# PX4FMUv2_4.net
KiCad netlist of a schematic drawn in EAGLE
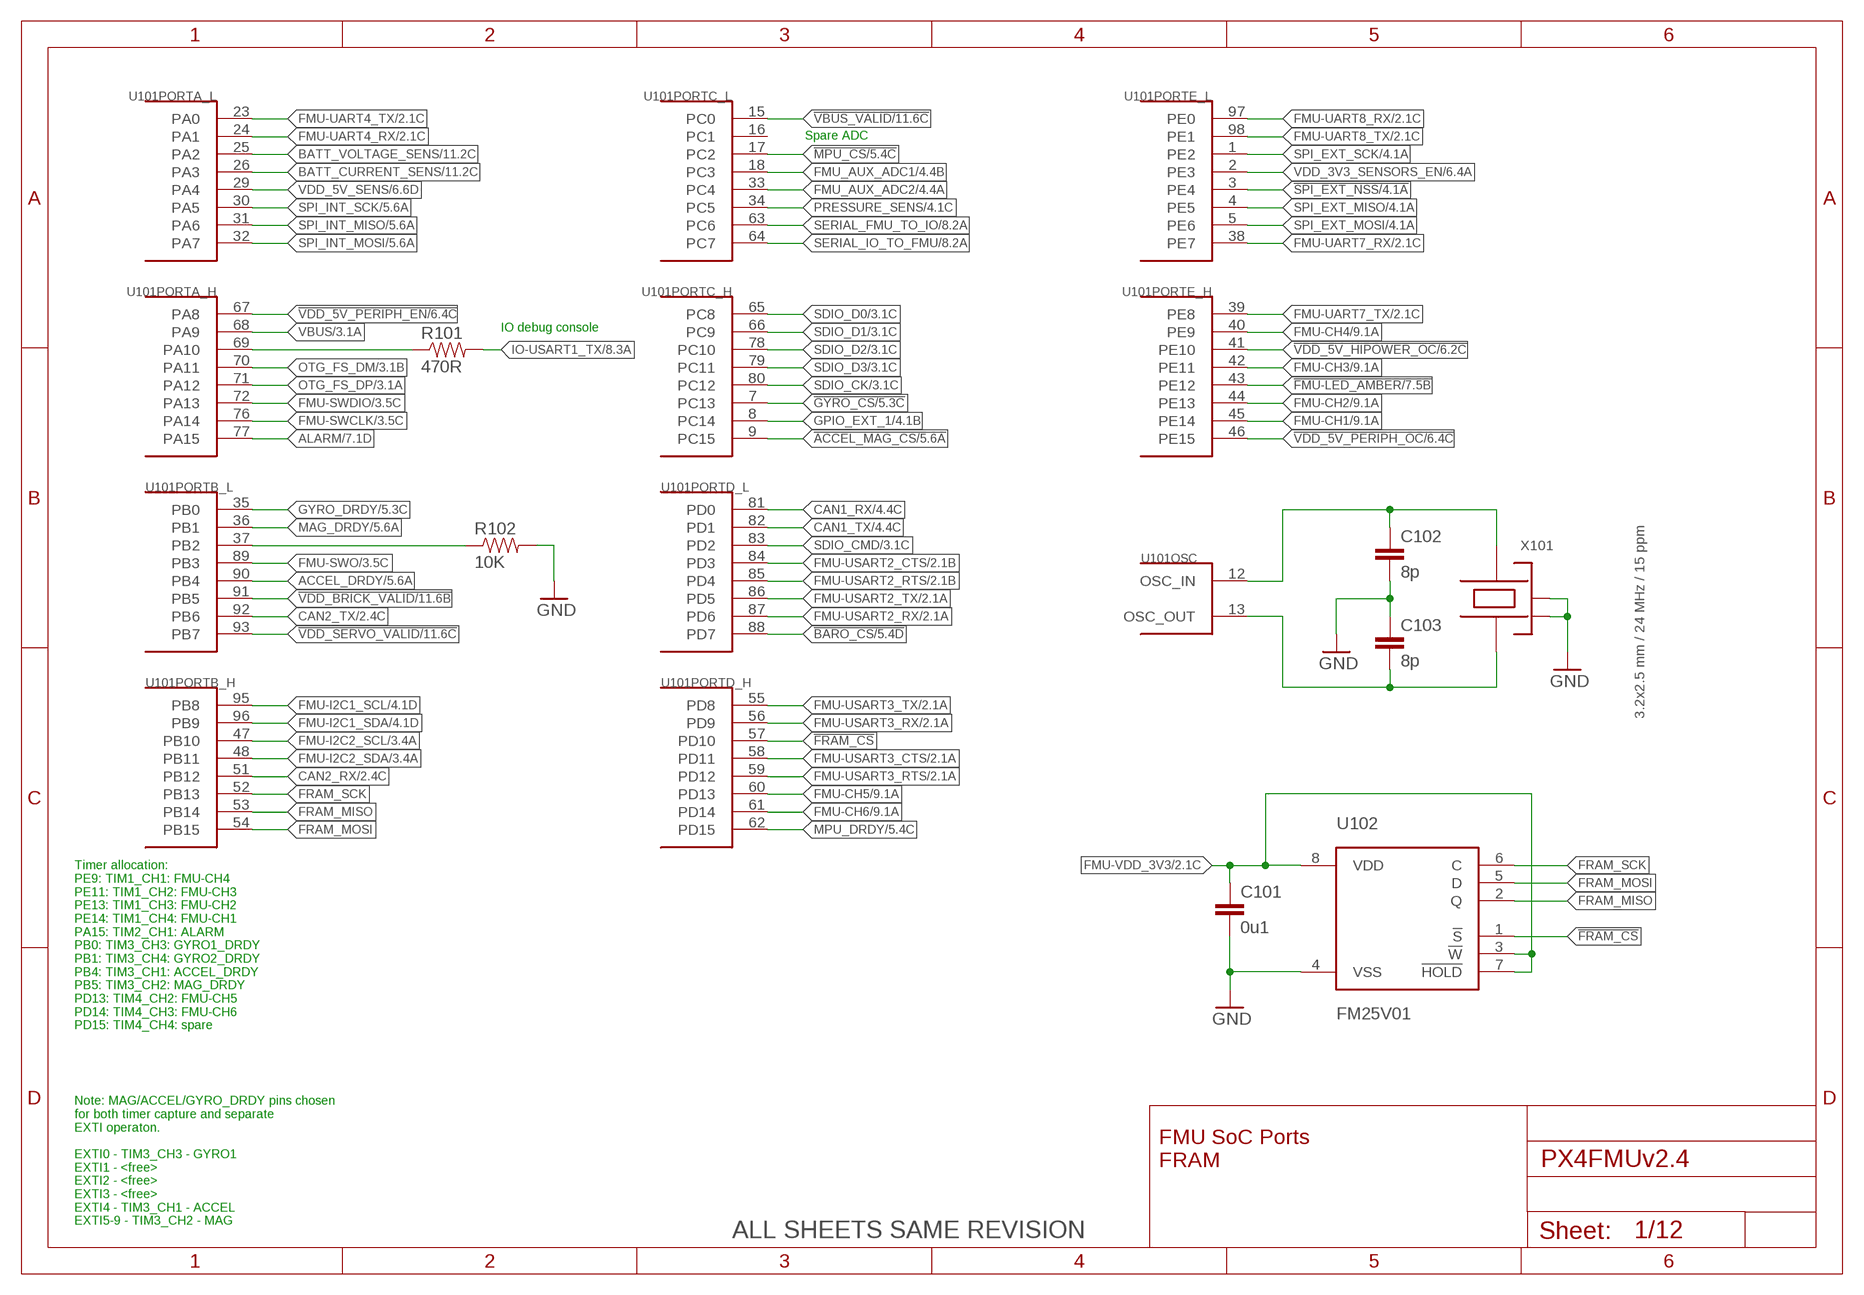
[diagram p0: schematic, sheet 1]
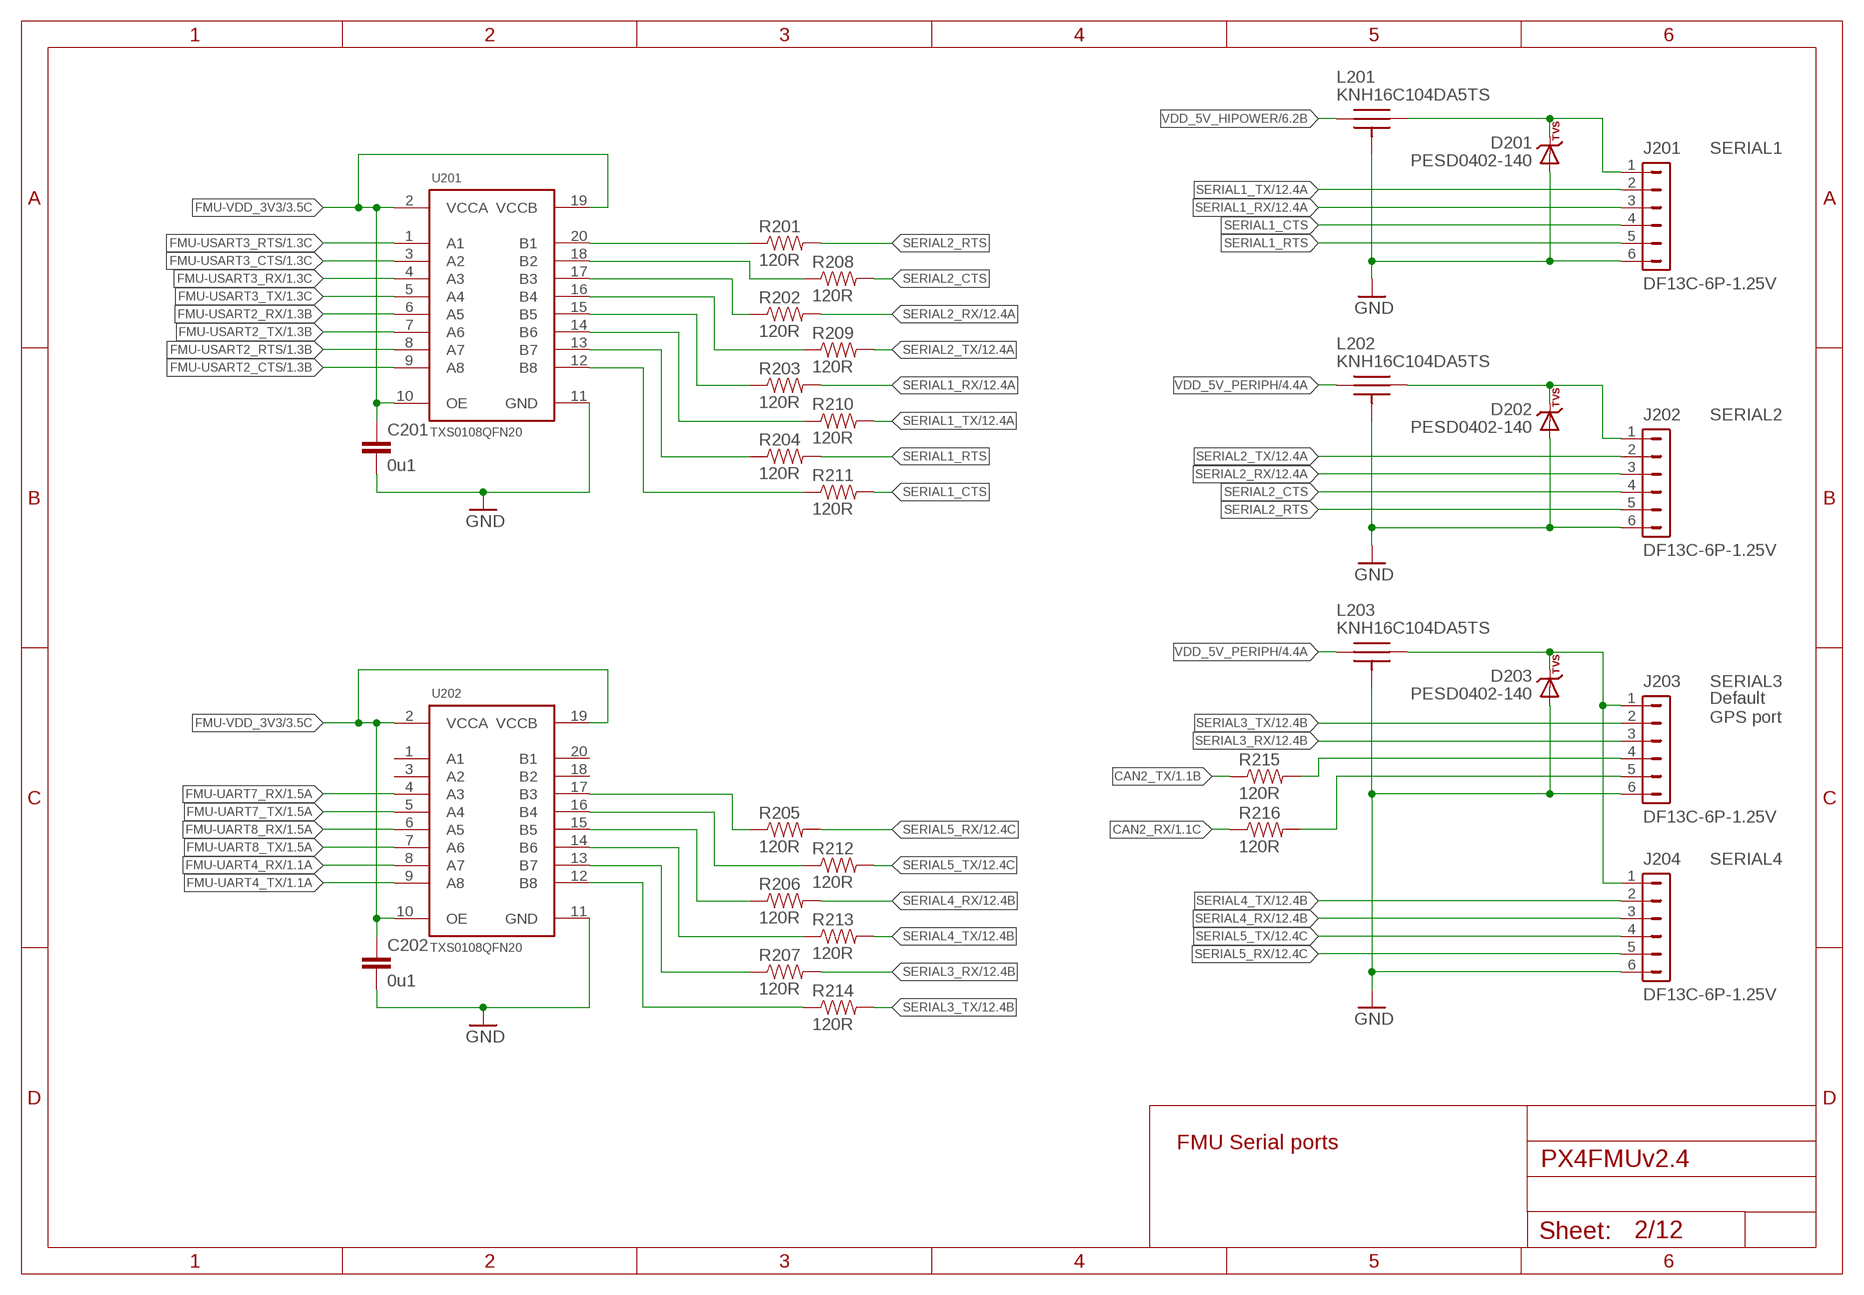
[diagram p1: schematic, sheet 2]
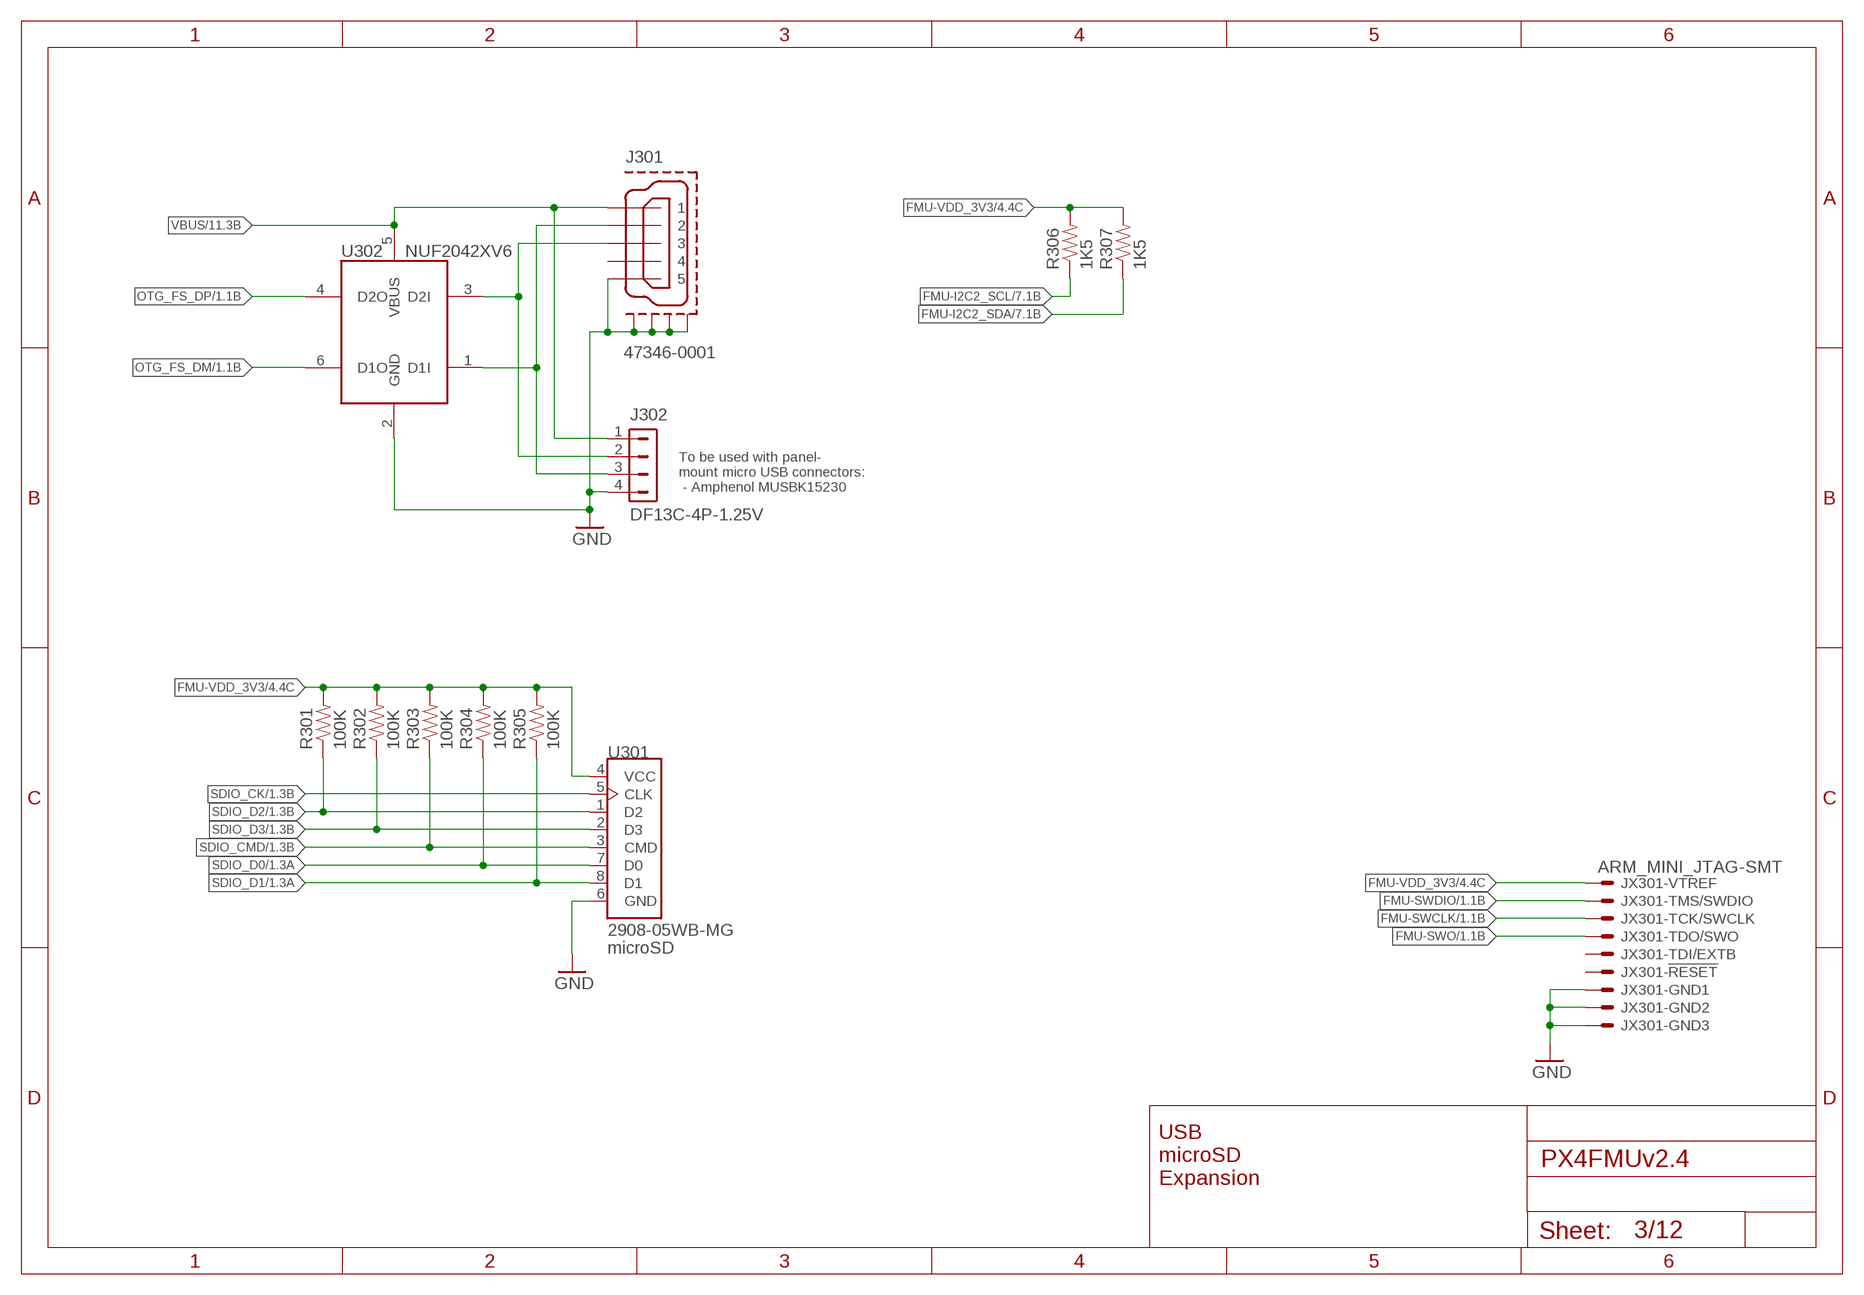
[diagram p2: schematic, sheet 3]
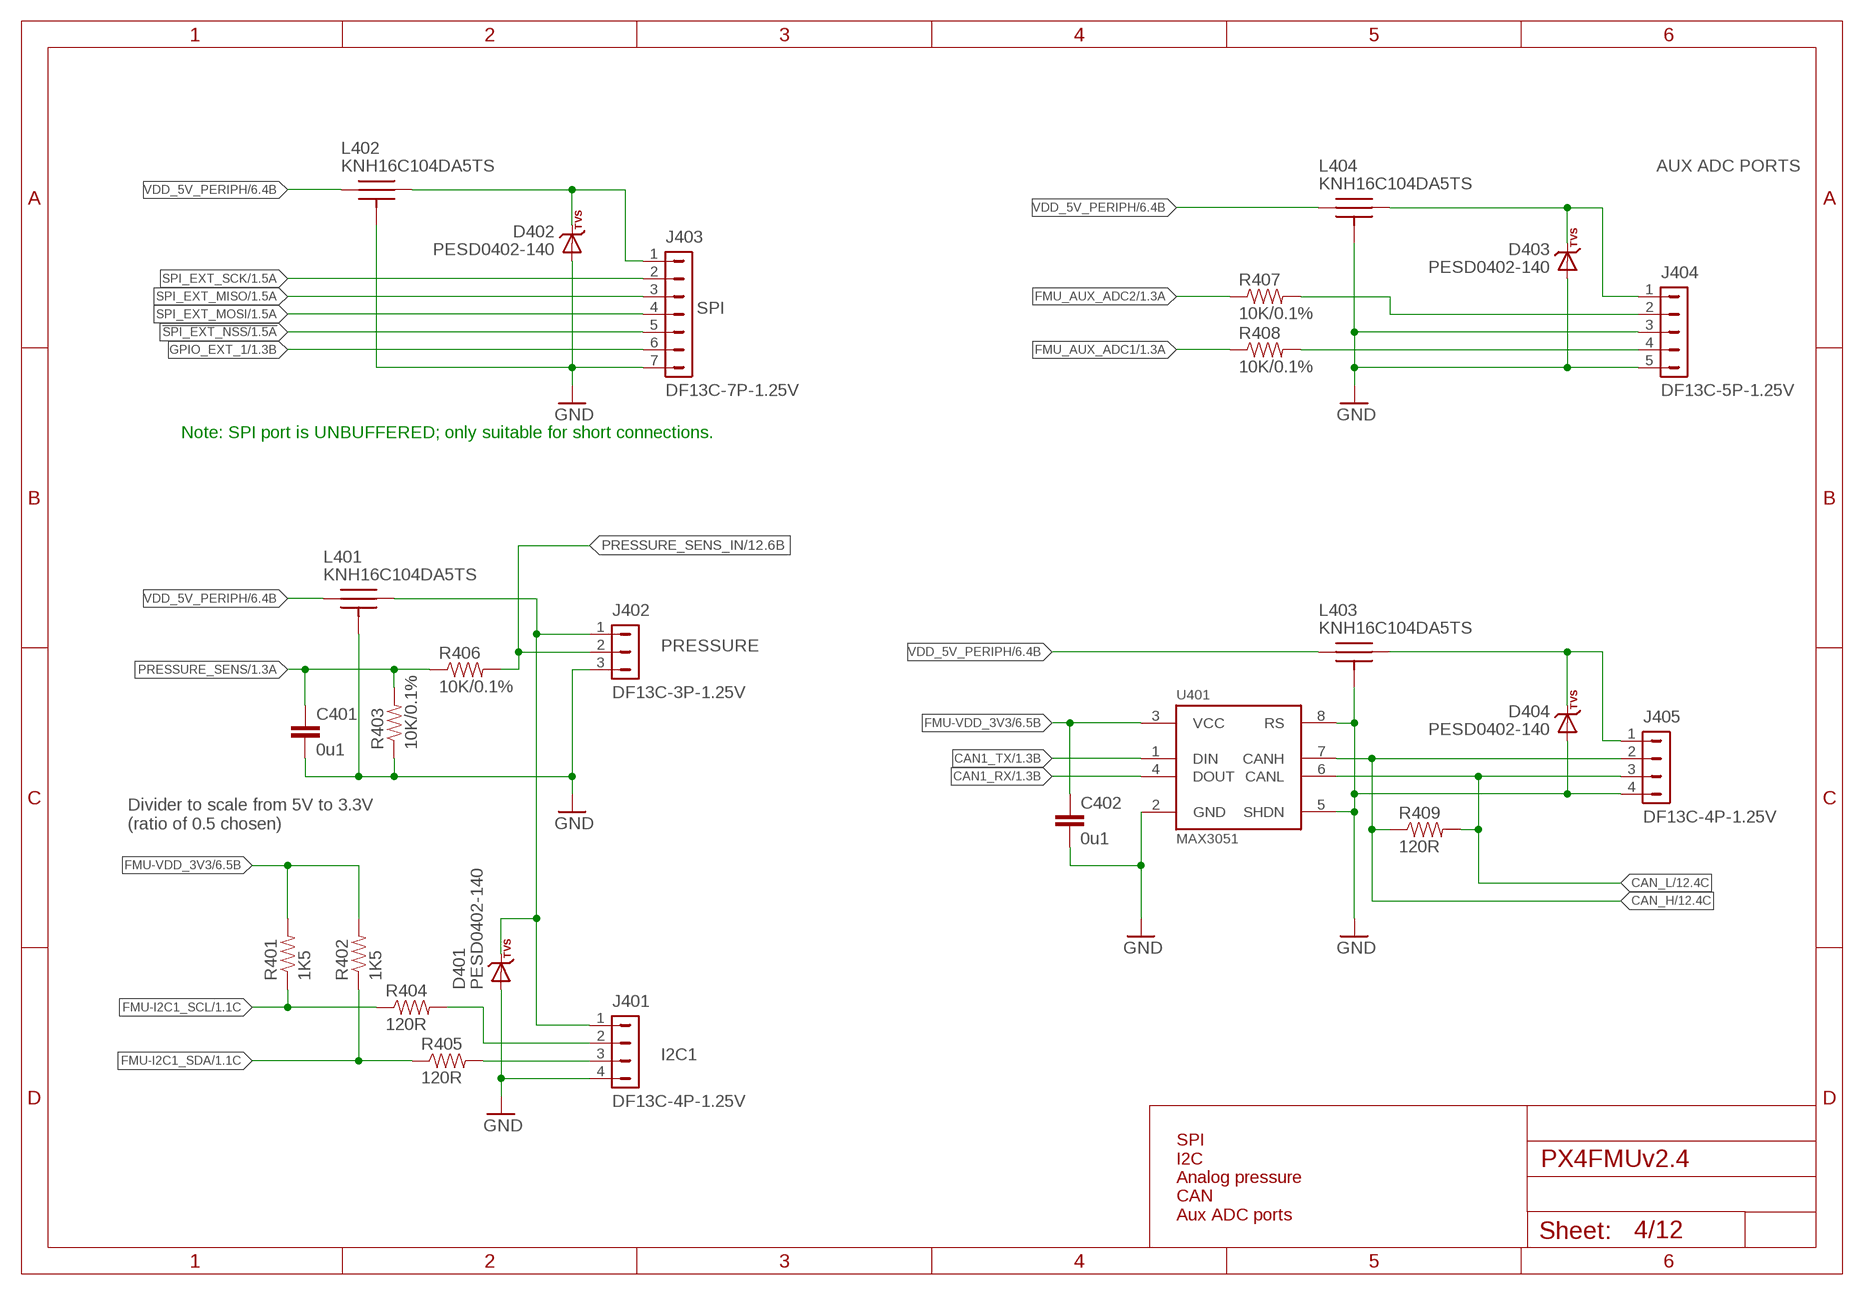
[diagram p3: schematic, sheet 4]
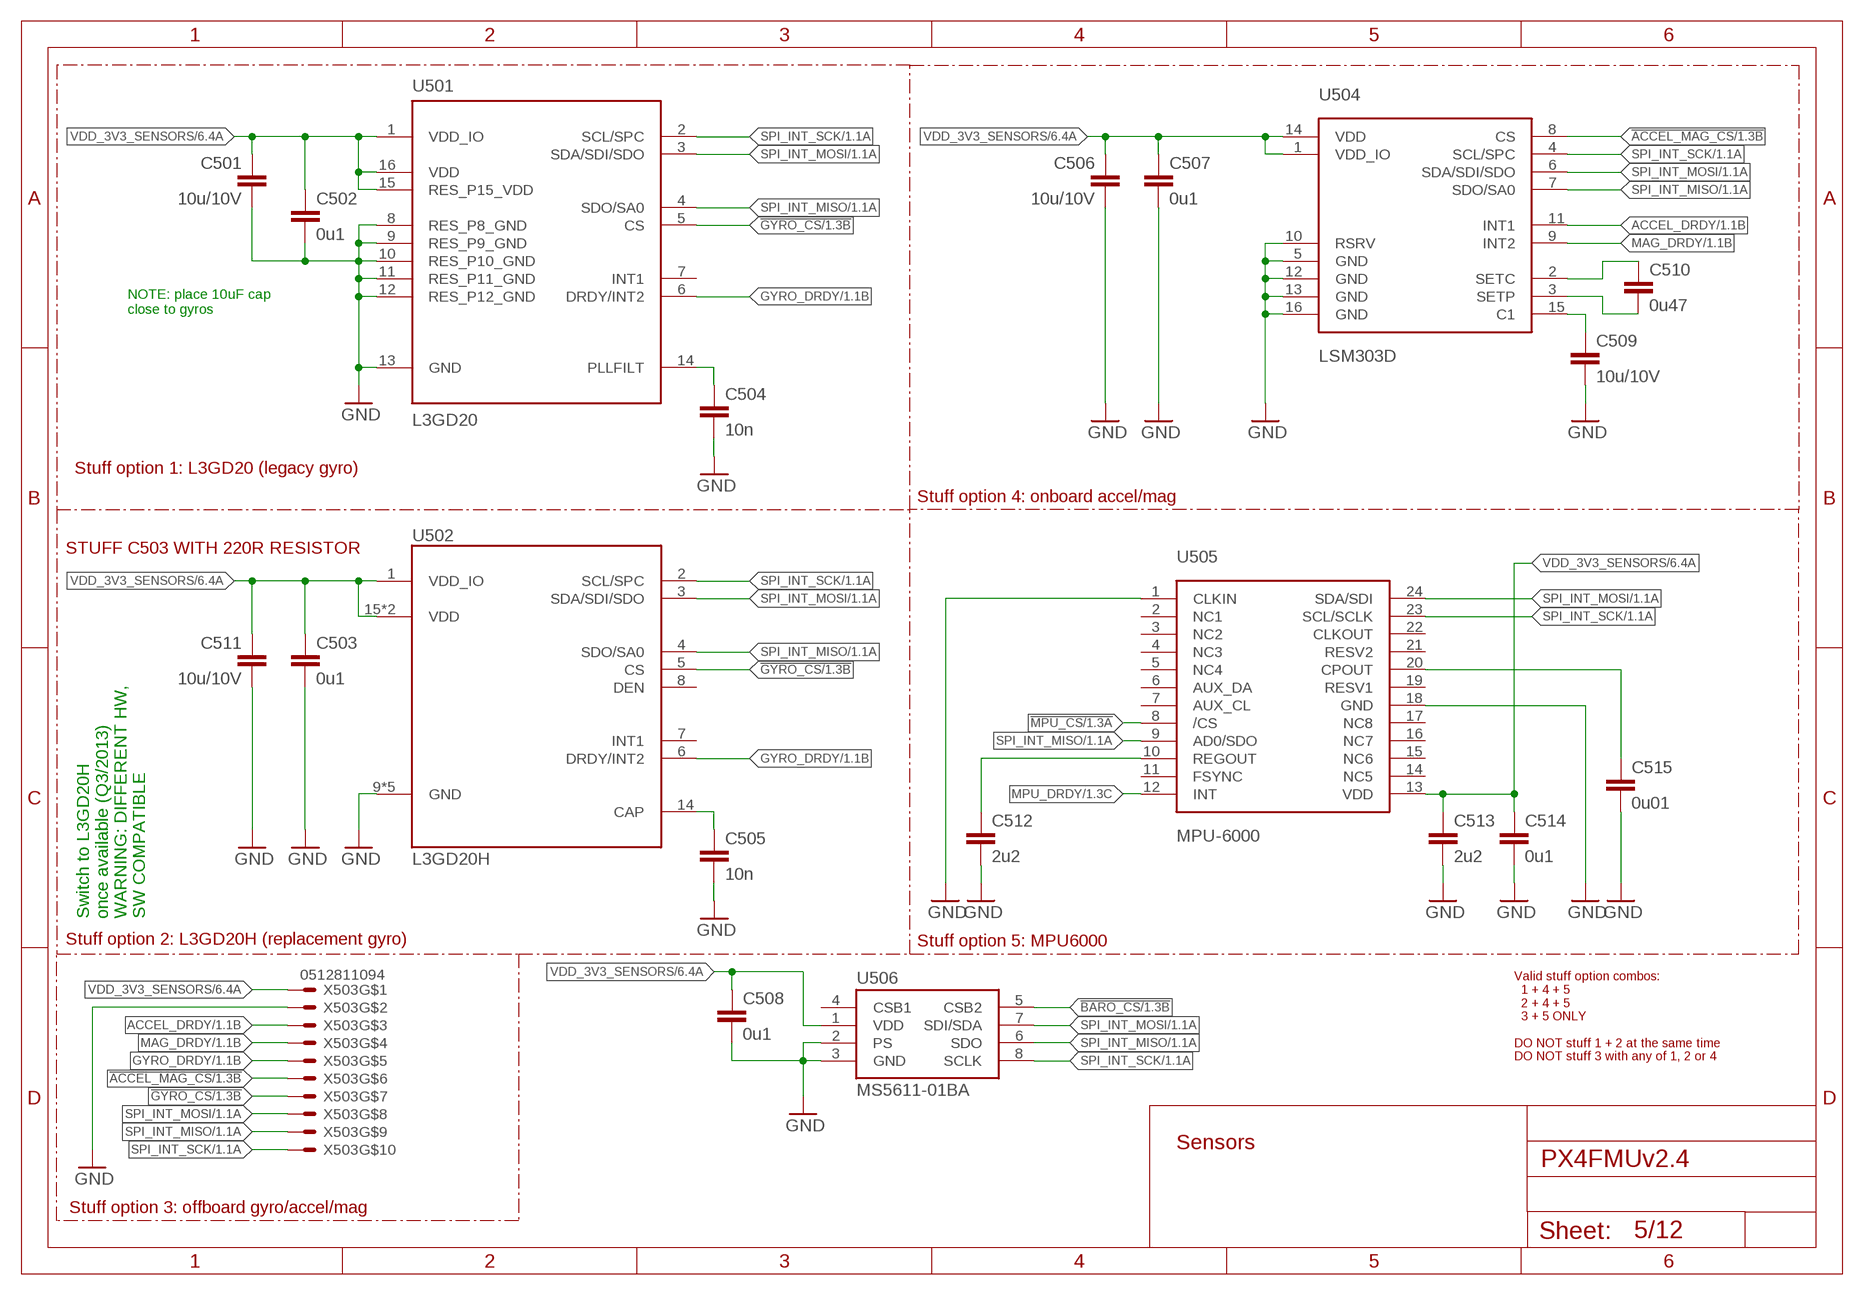
[diagram p4: schematic, sheet 5]
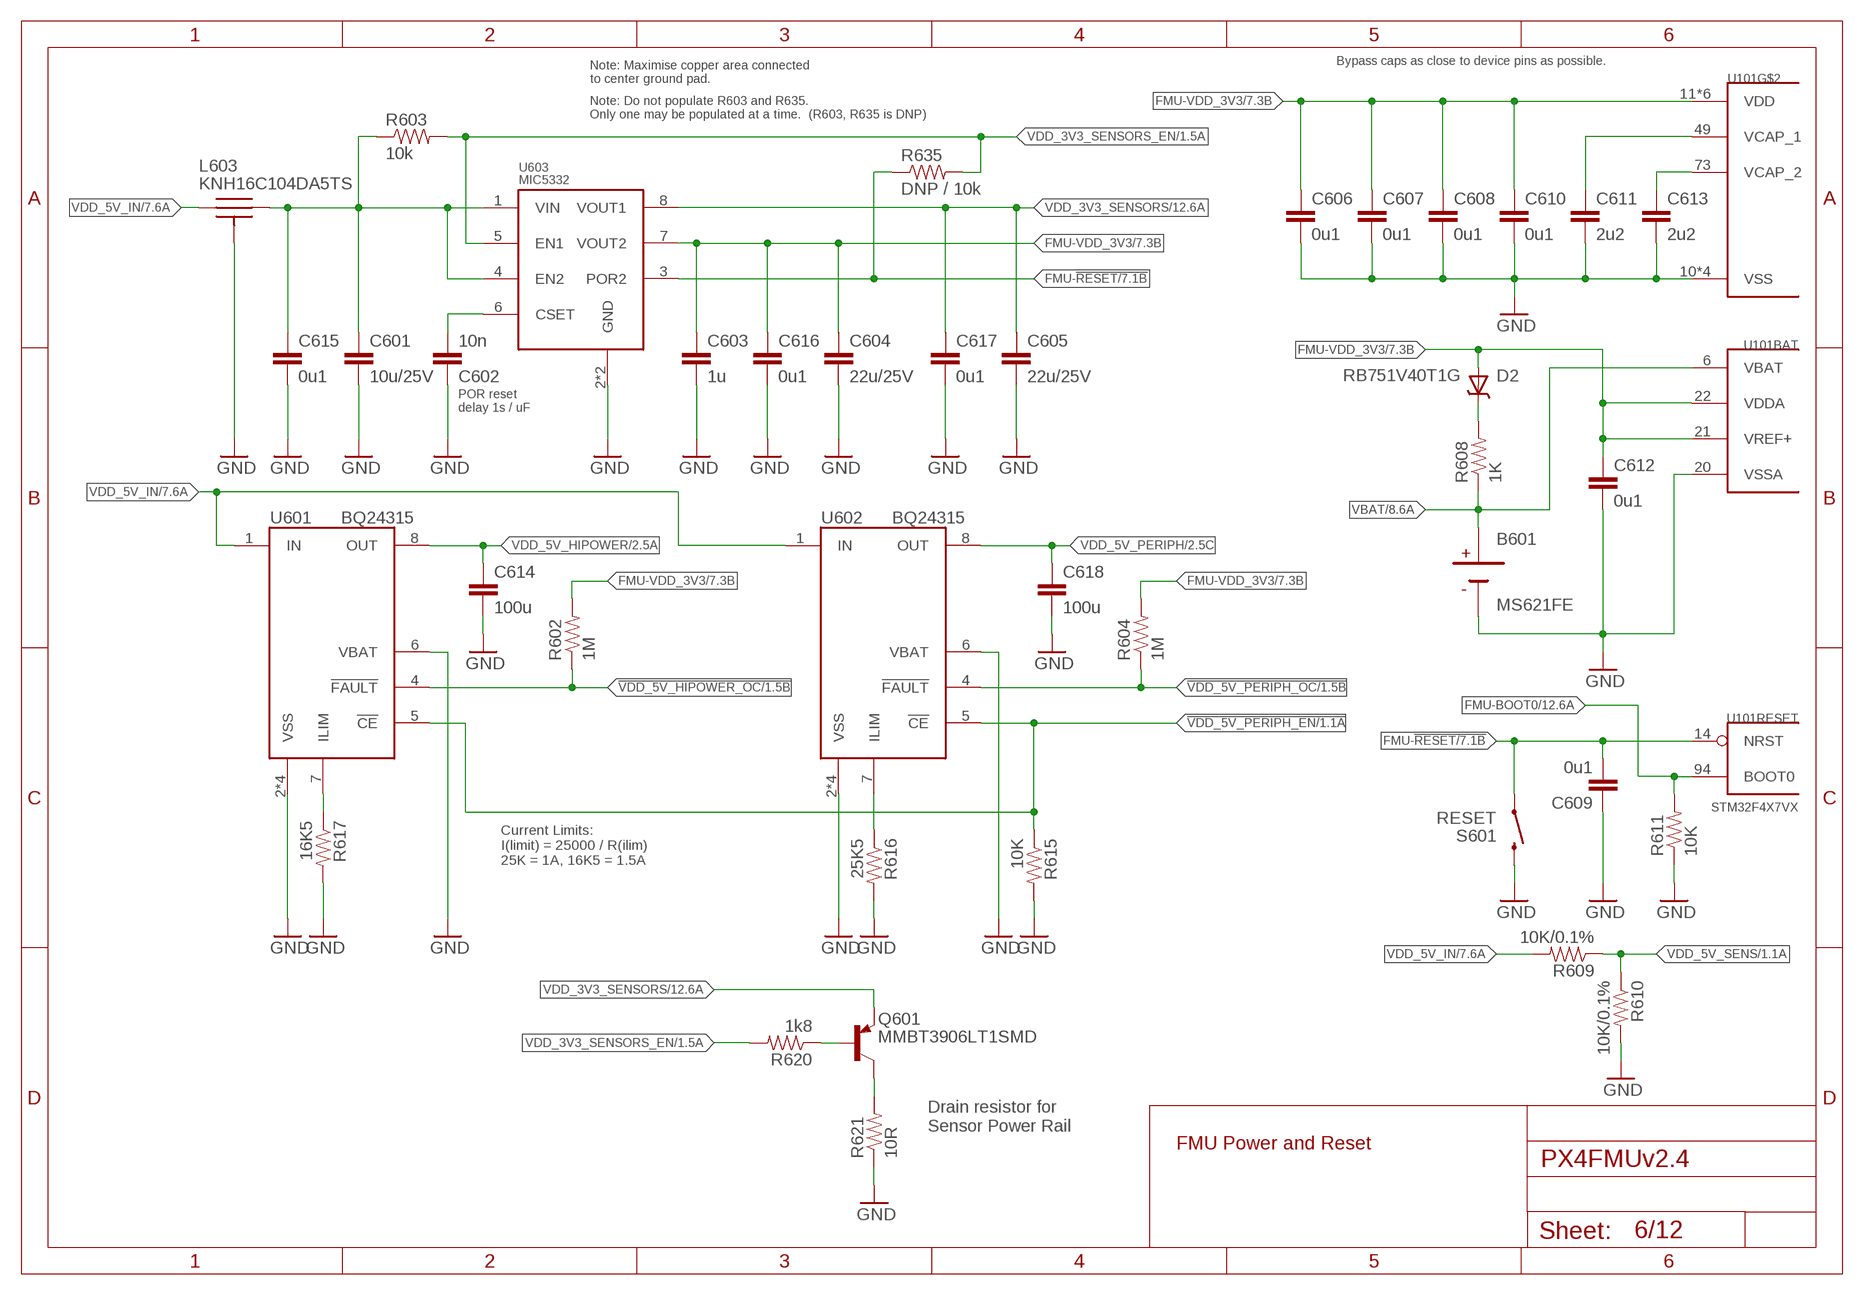
[diagram p5: schematic, sheet 6]
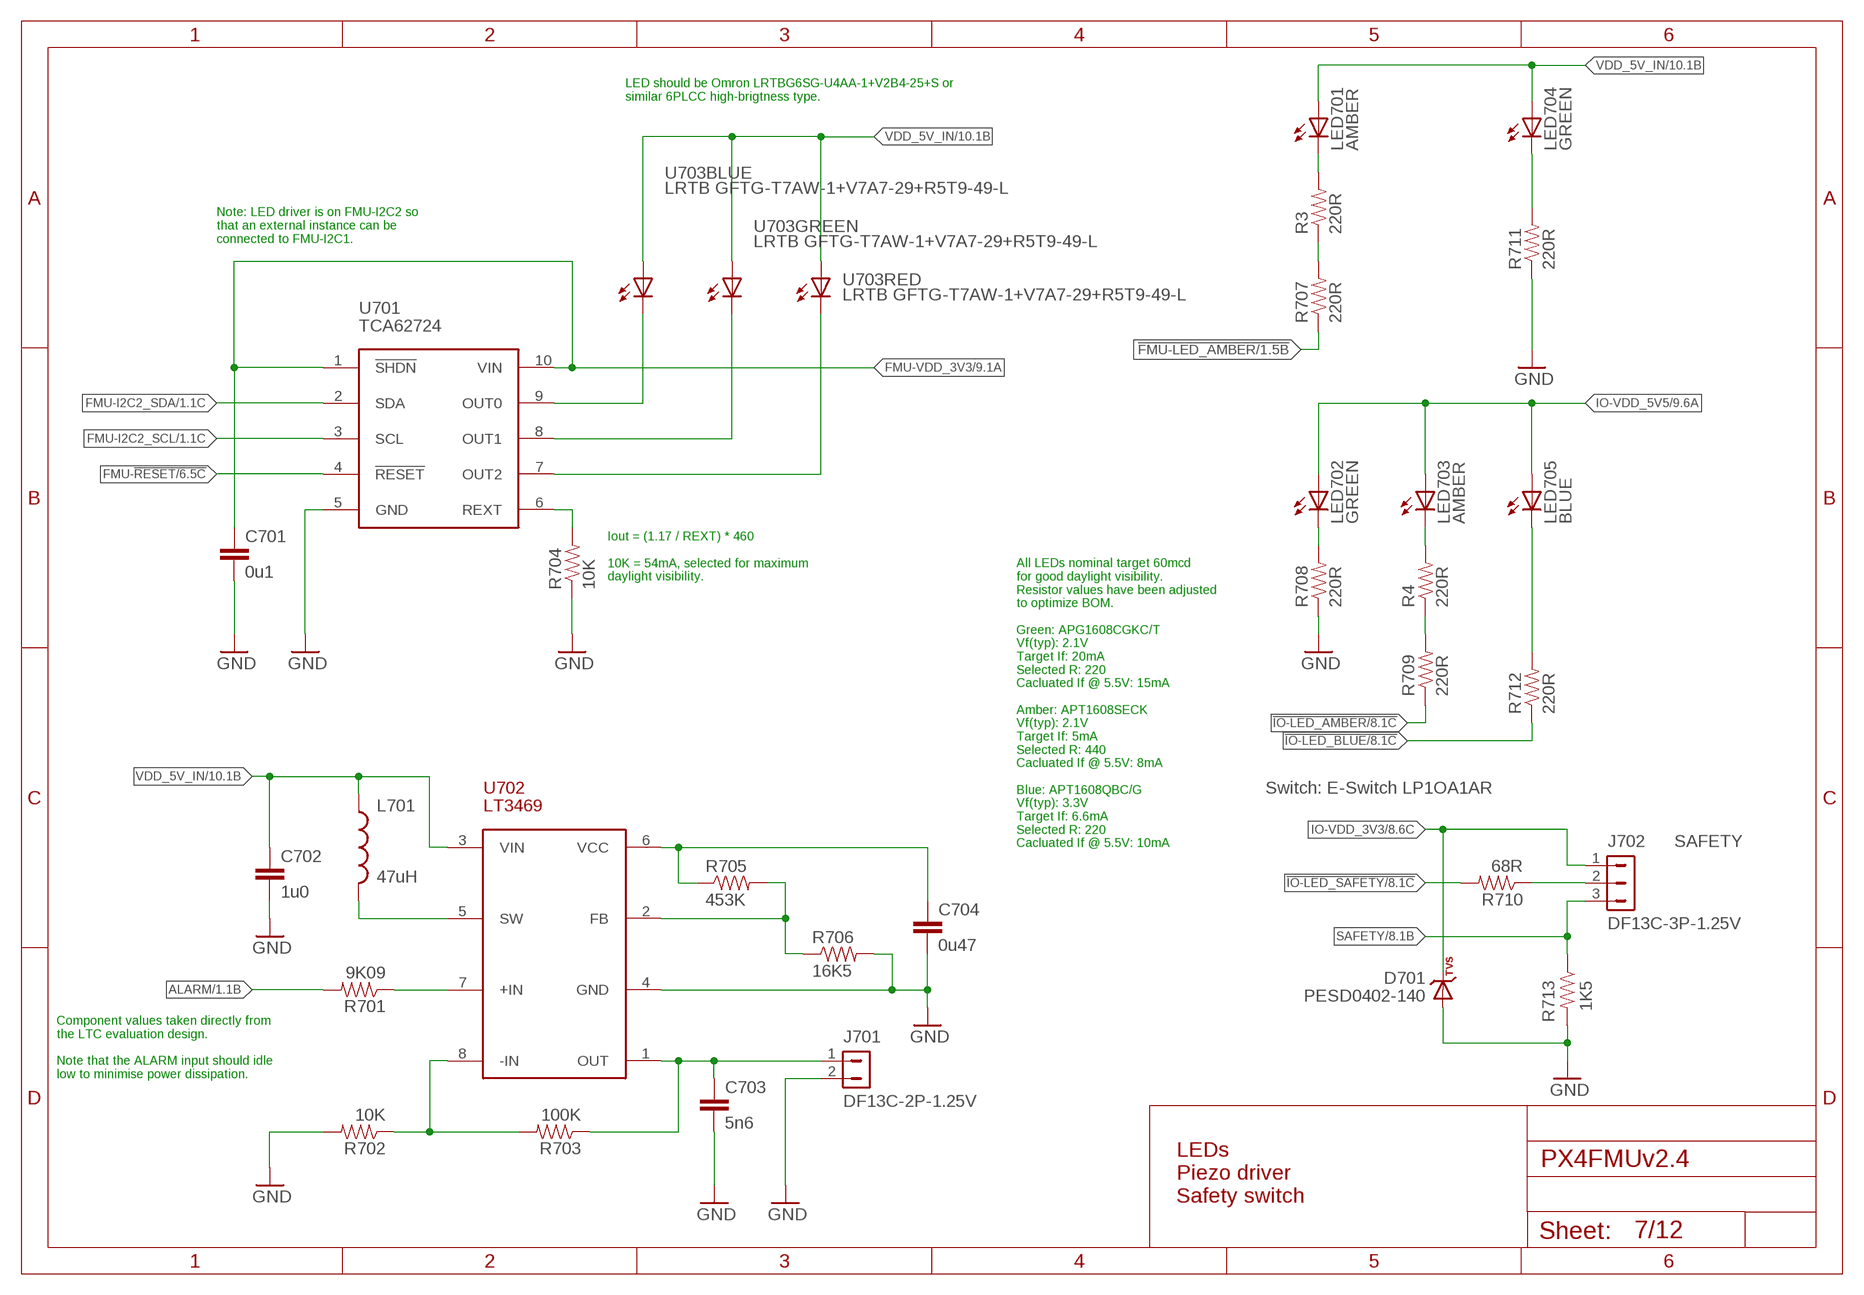
[diagram p6: schematic, sheet 7]
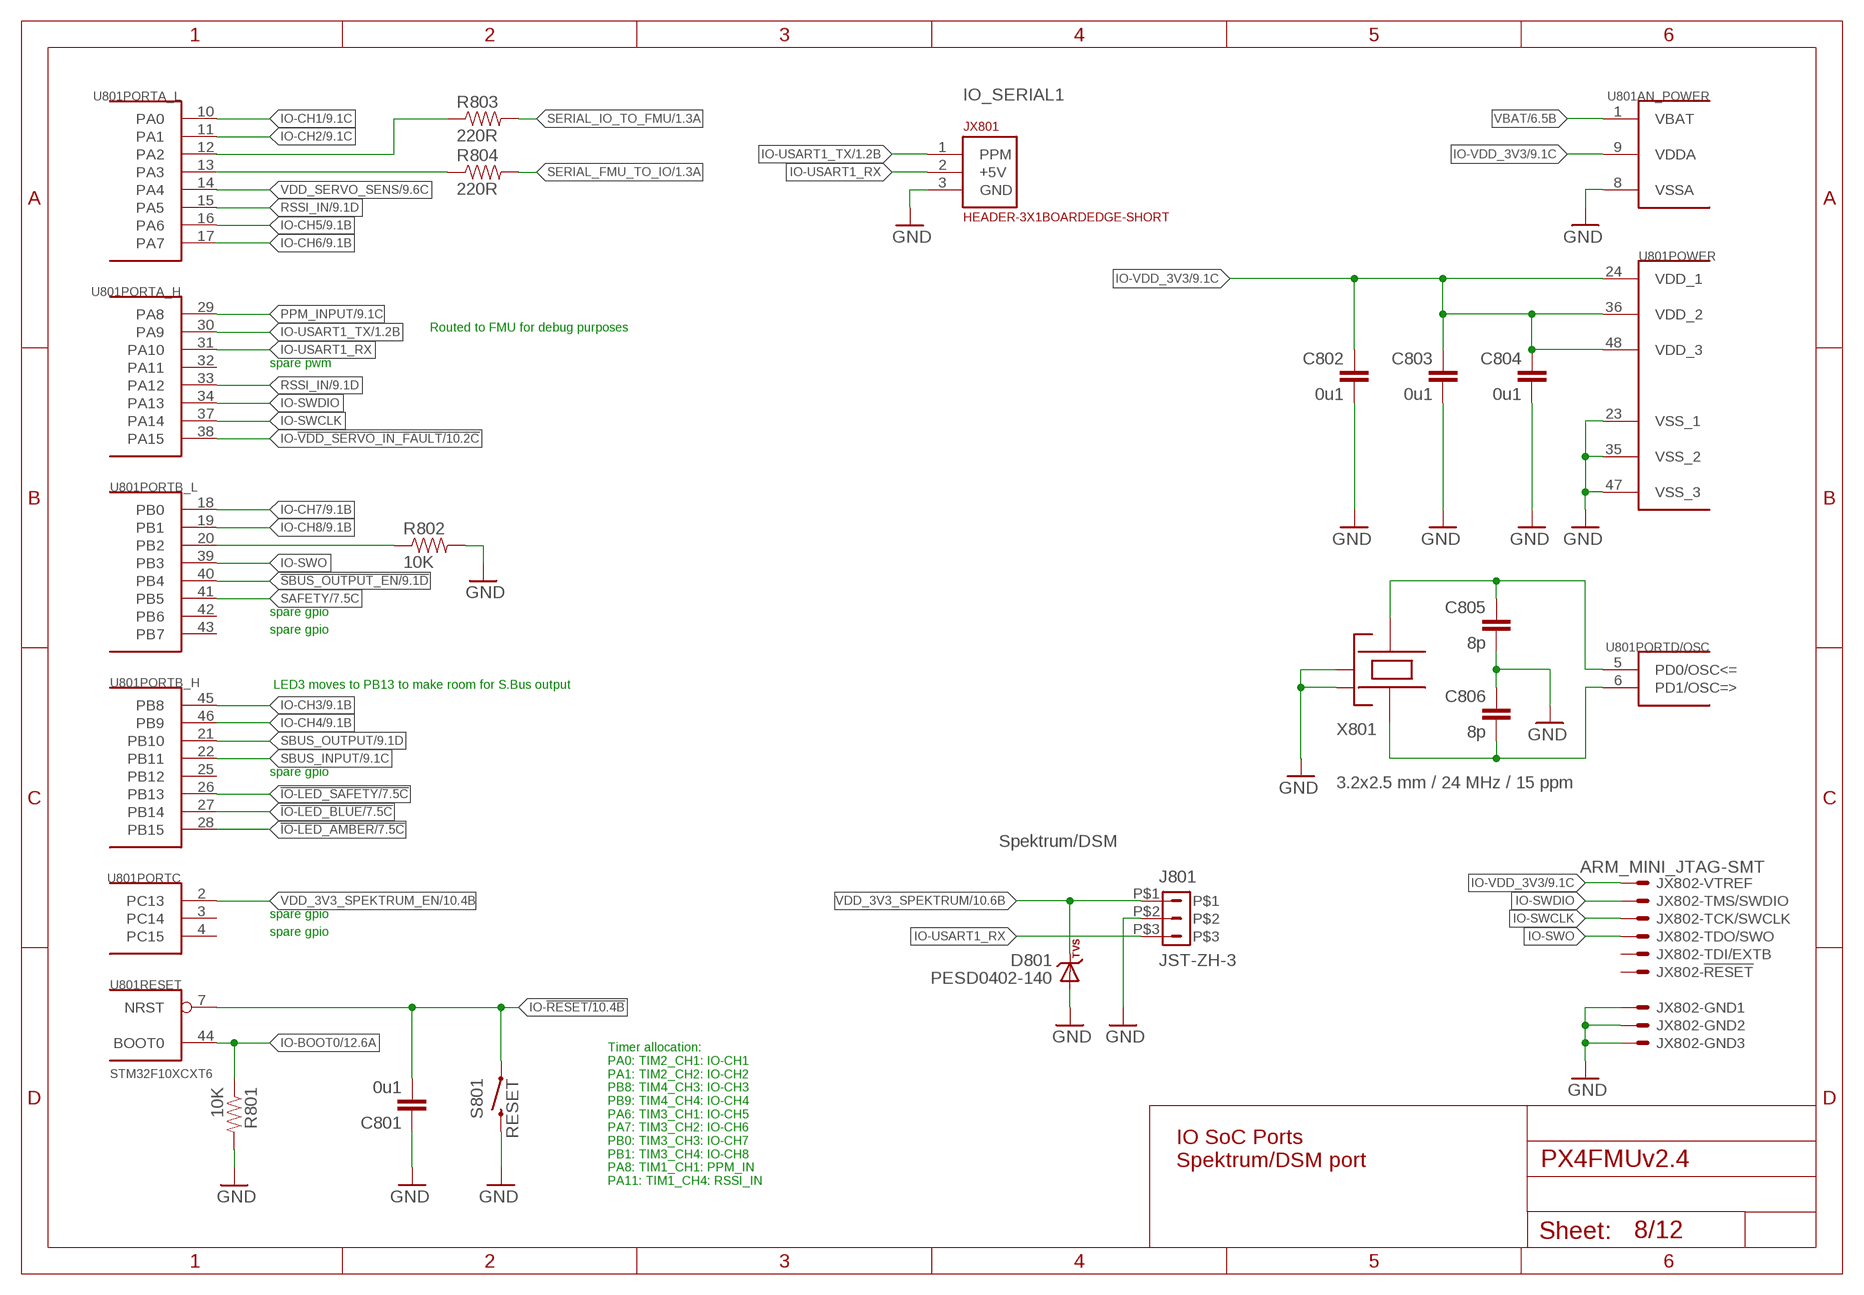
[diagram p7: schematic, sheet 8]
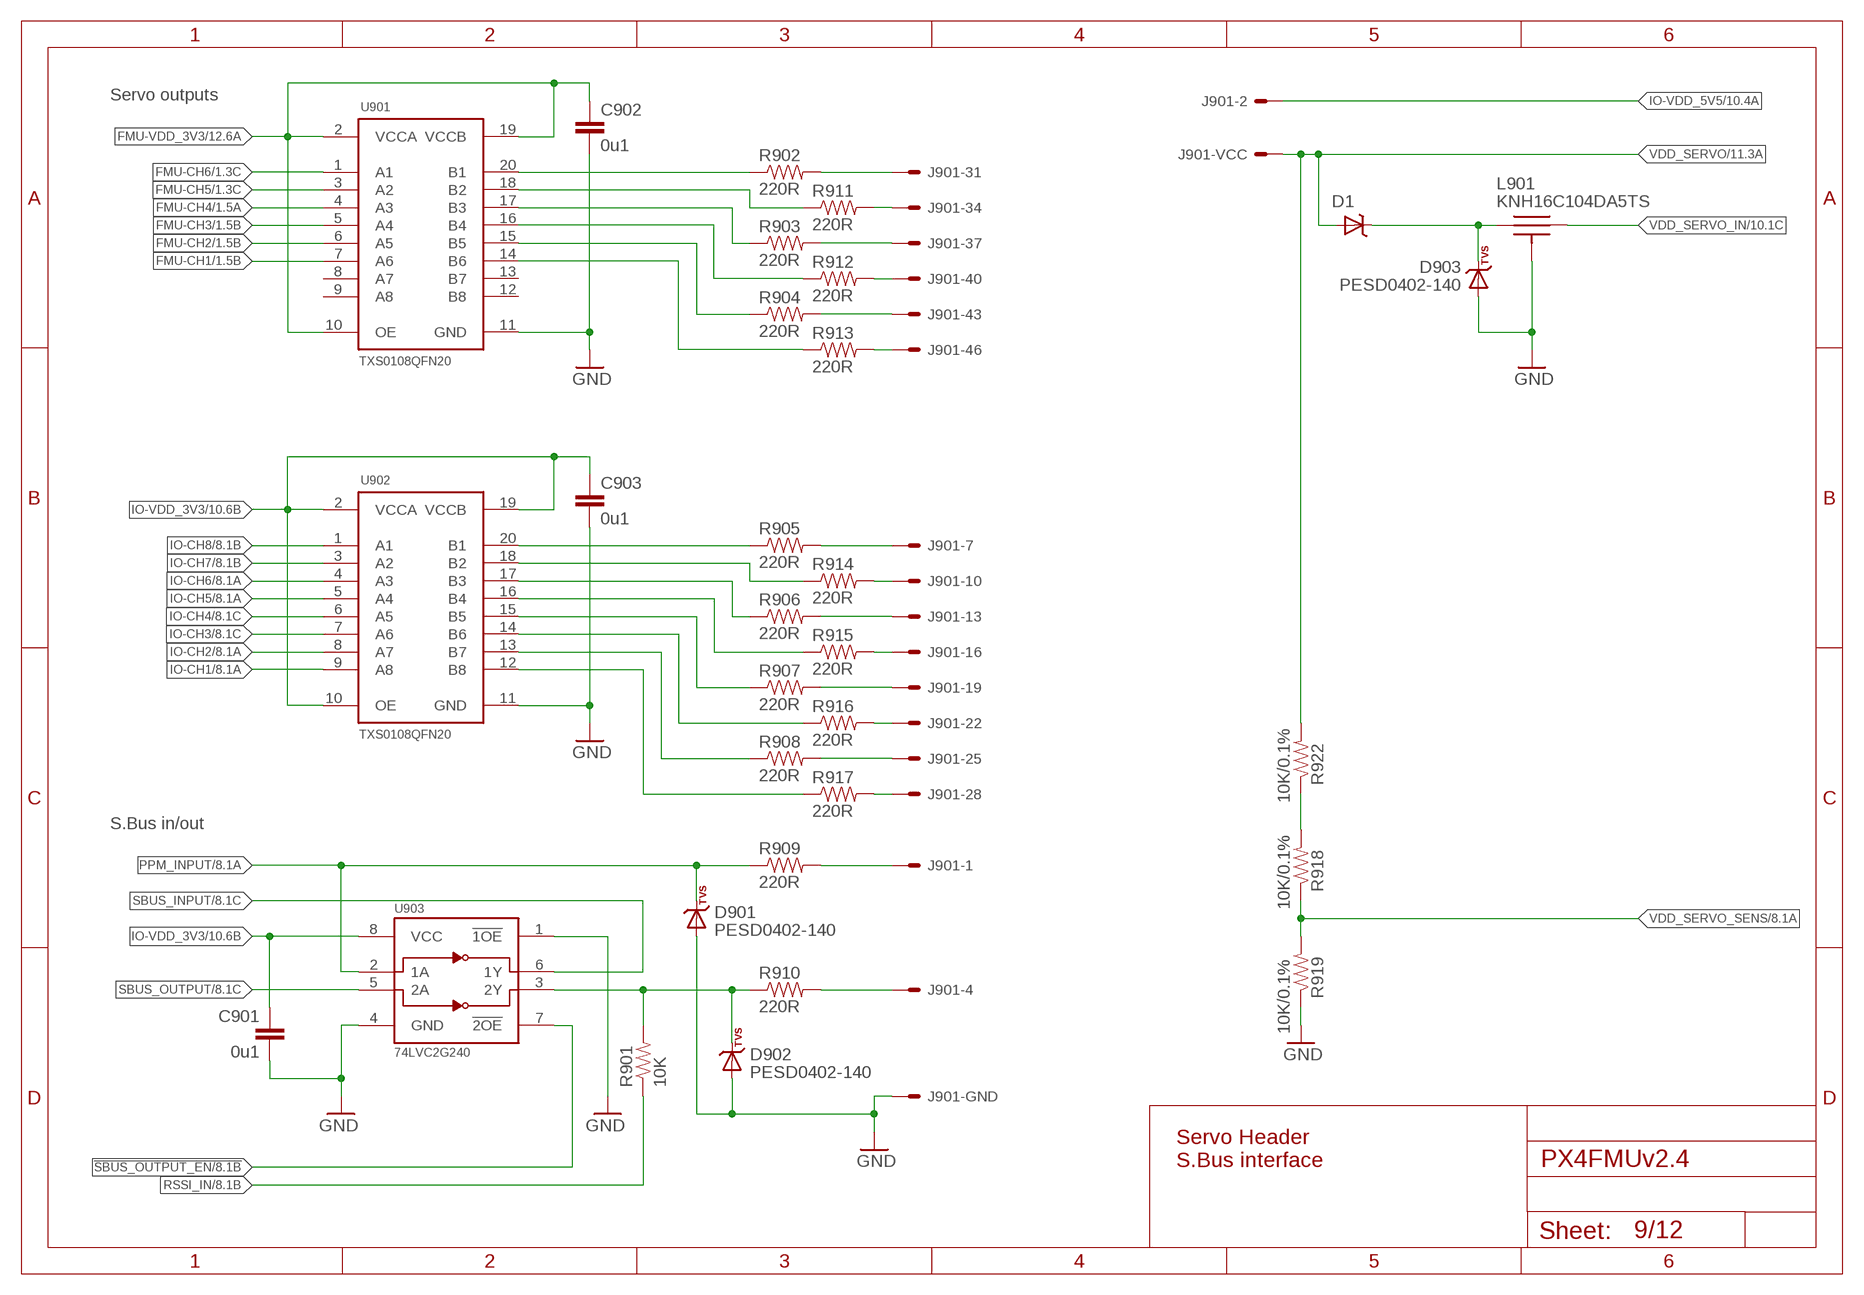
[diagram p8: schematic, sheet 9]
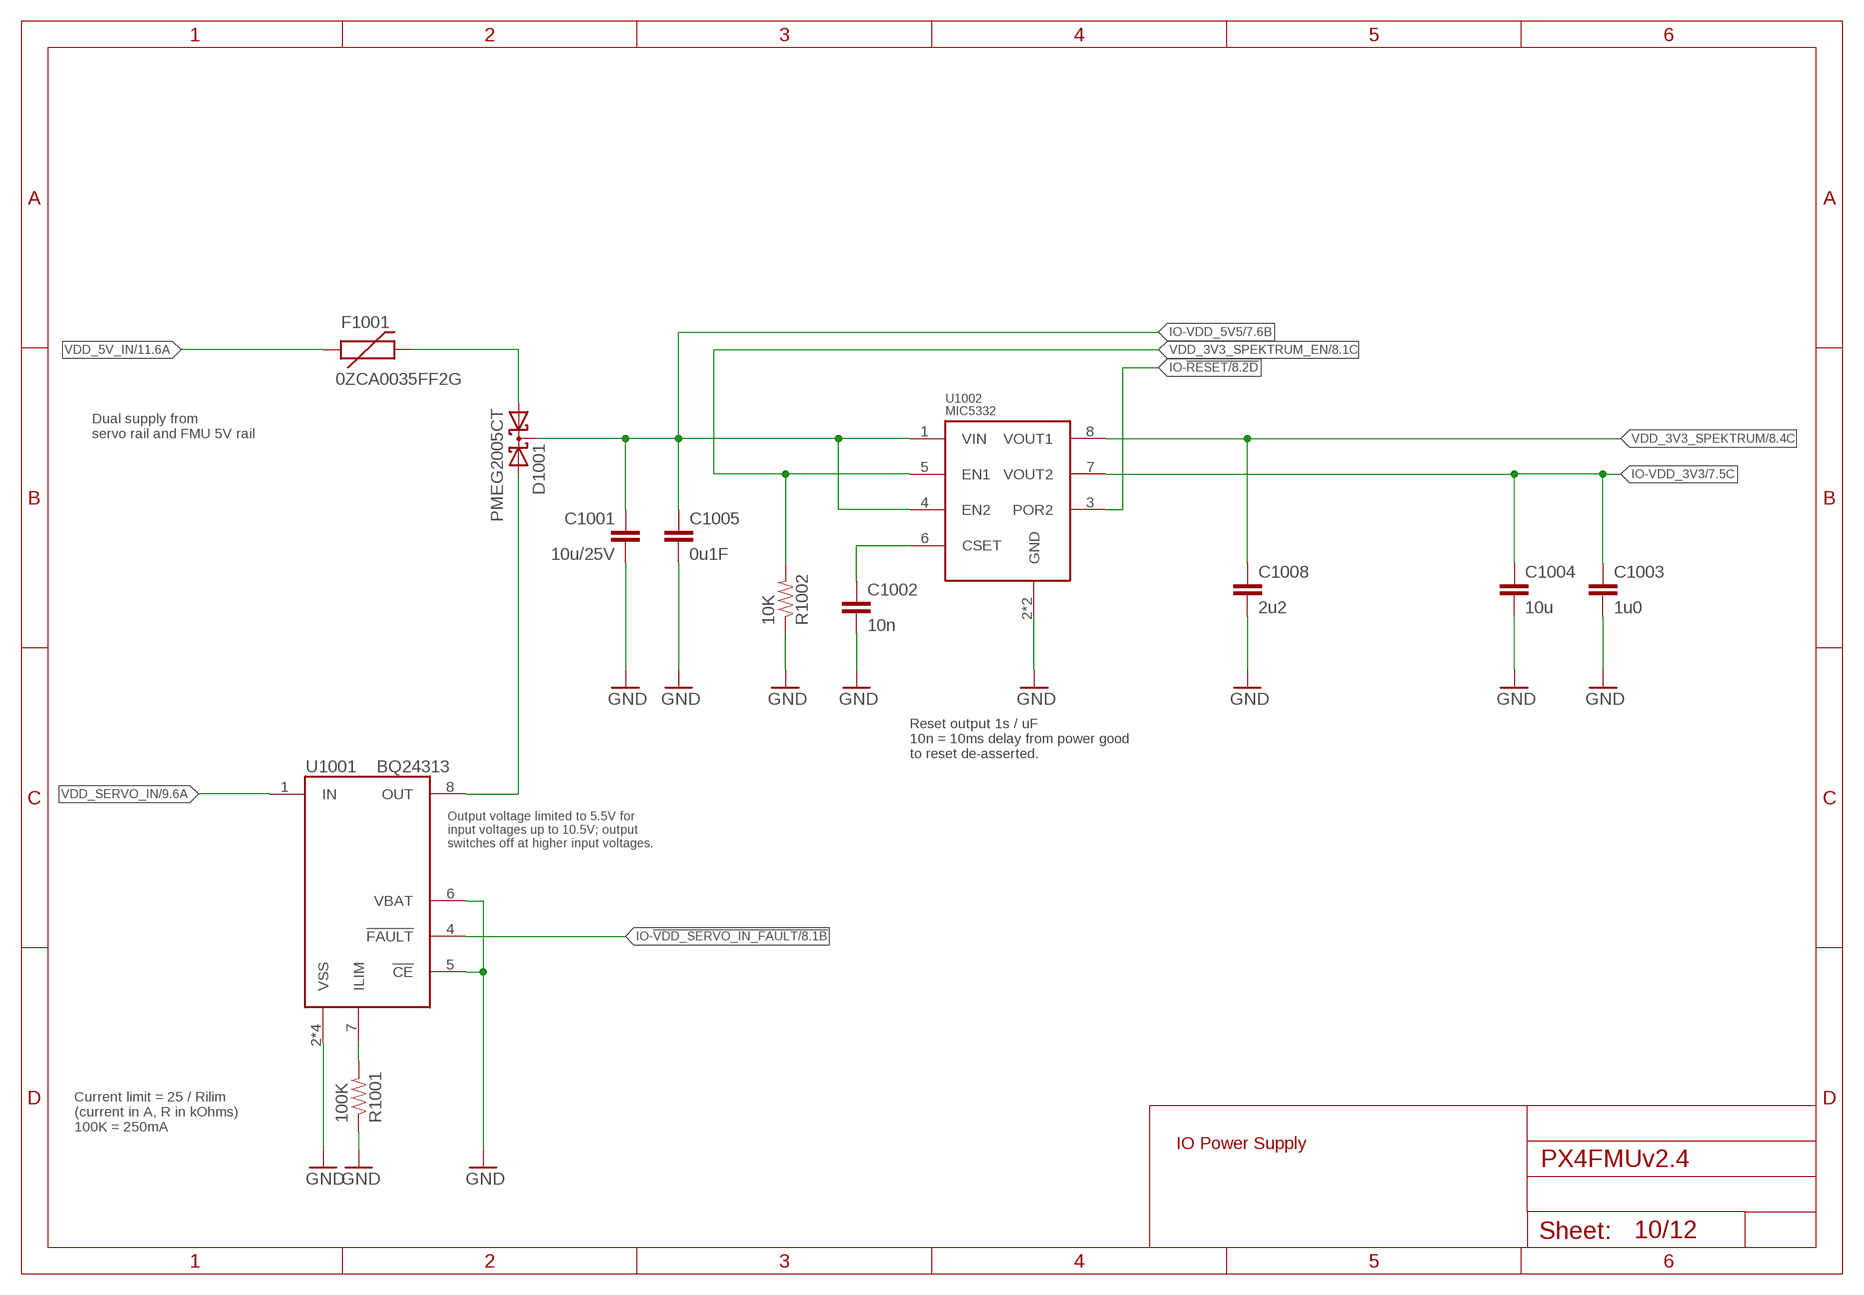
[diagram p9: schematic, sheet 10]
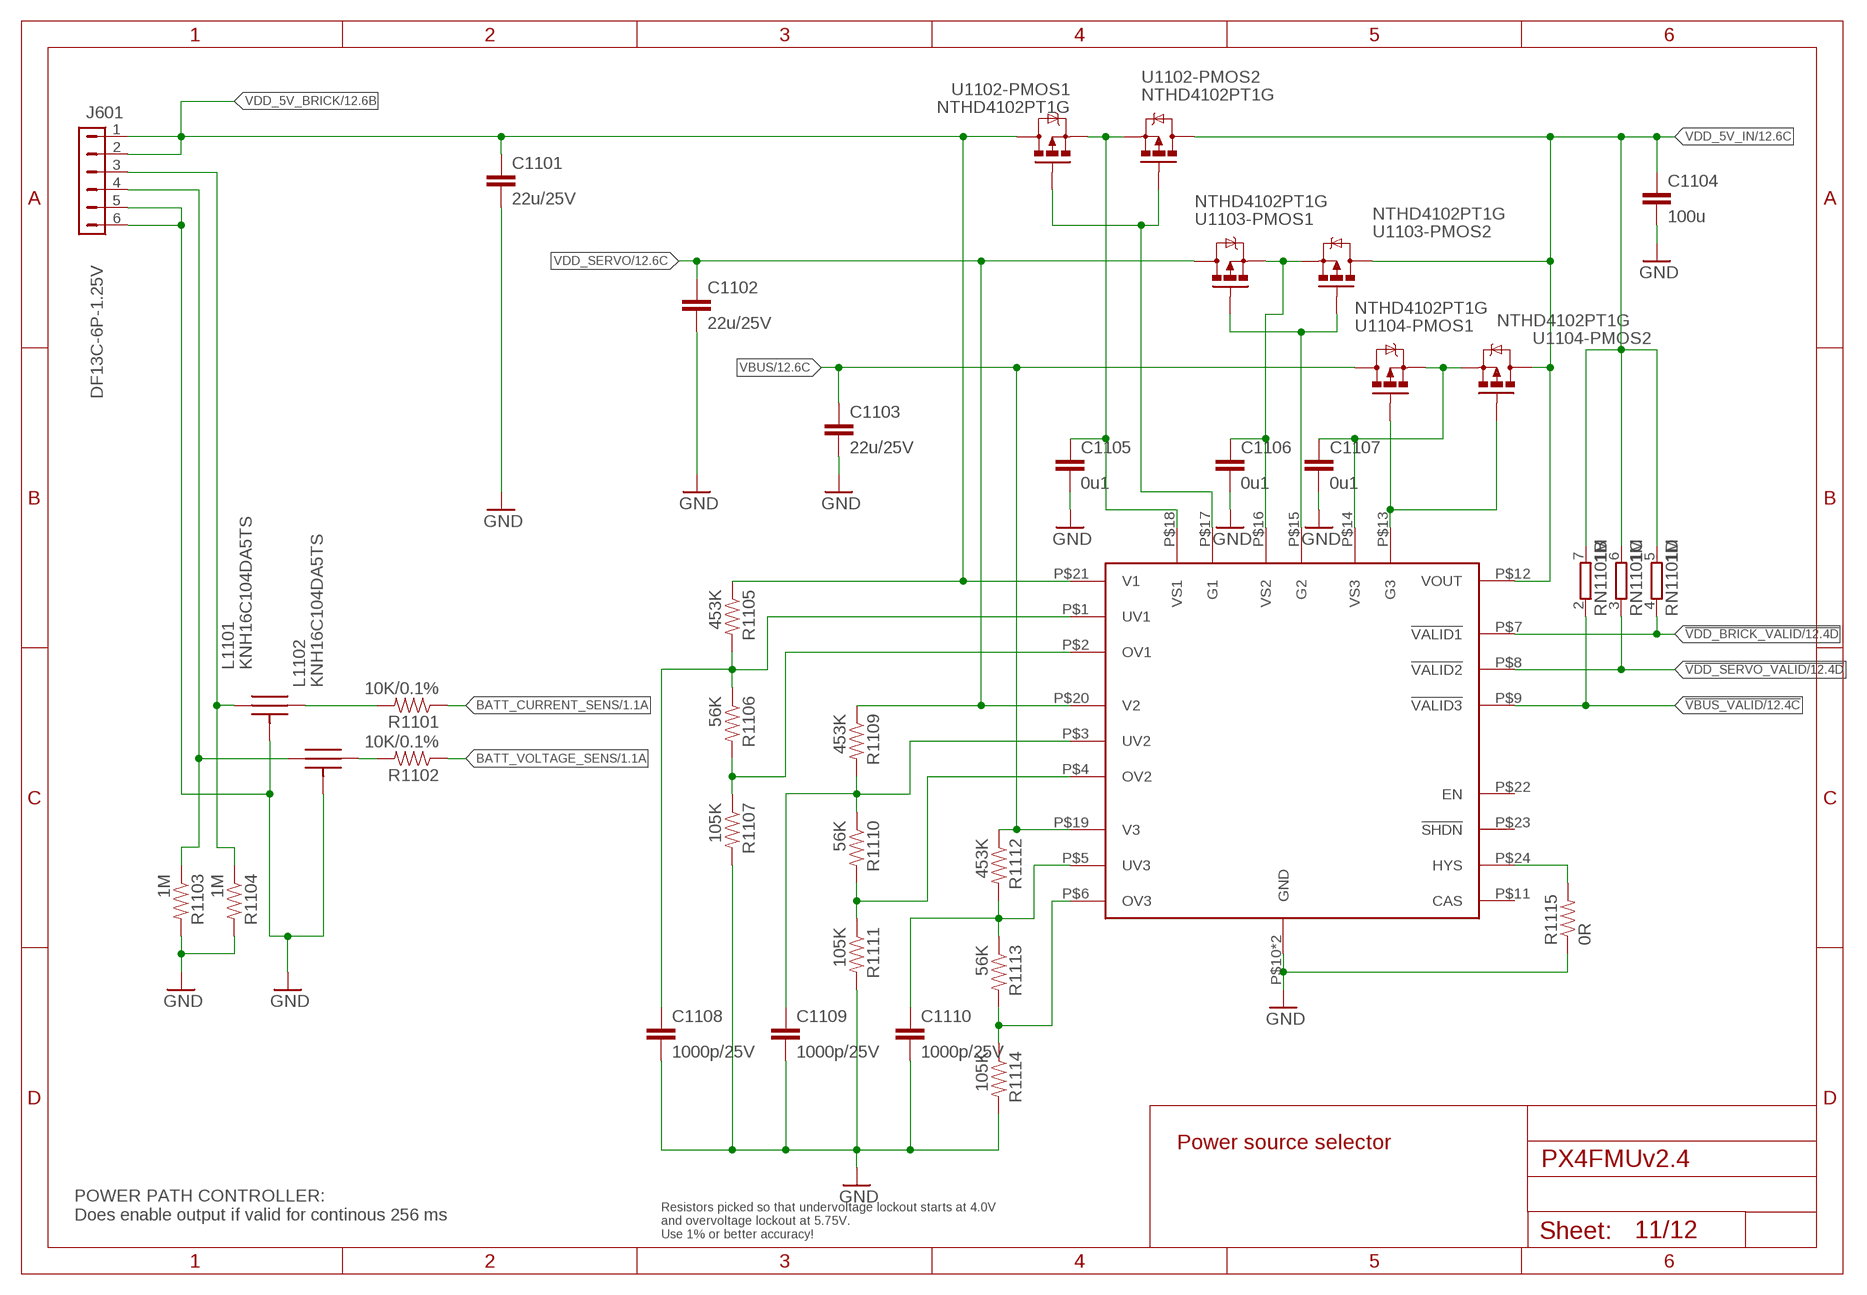
[diagram p10: schematic, sheet 11]
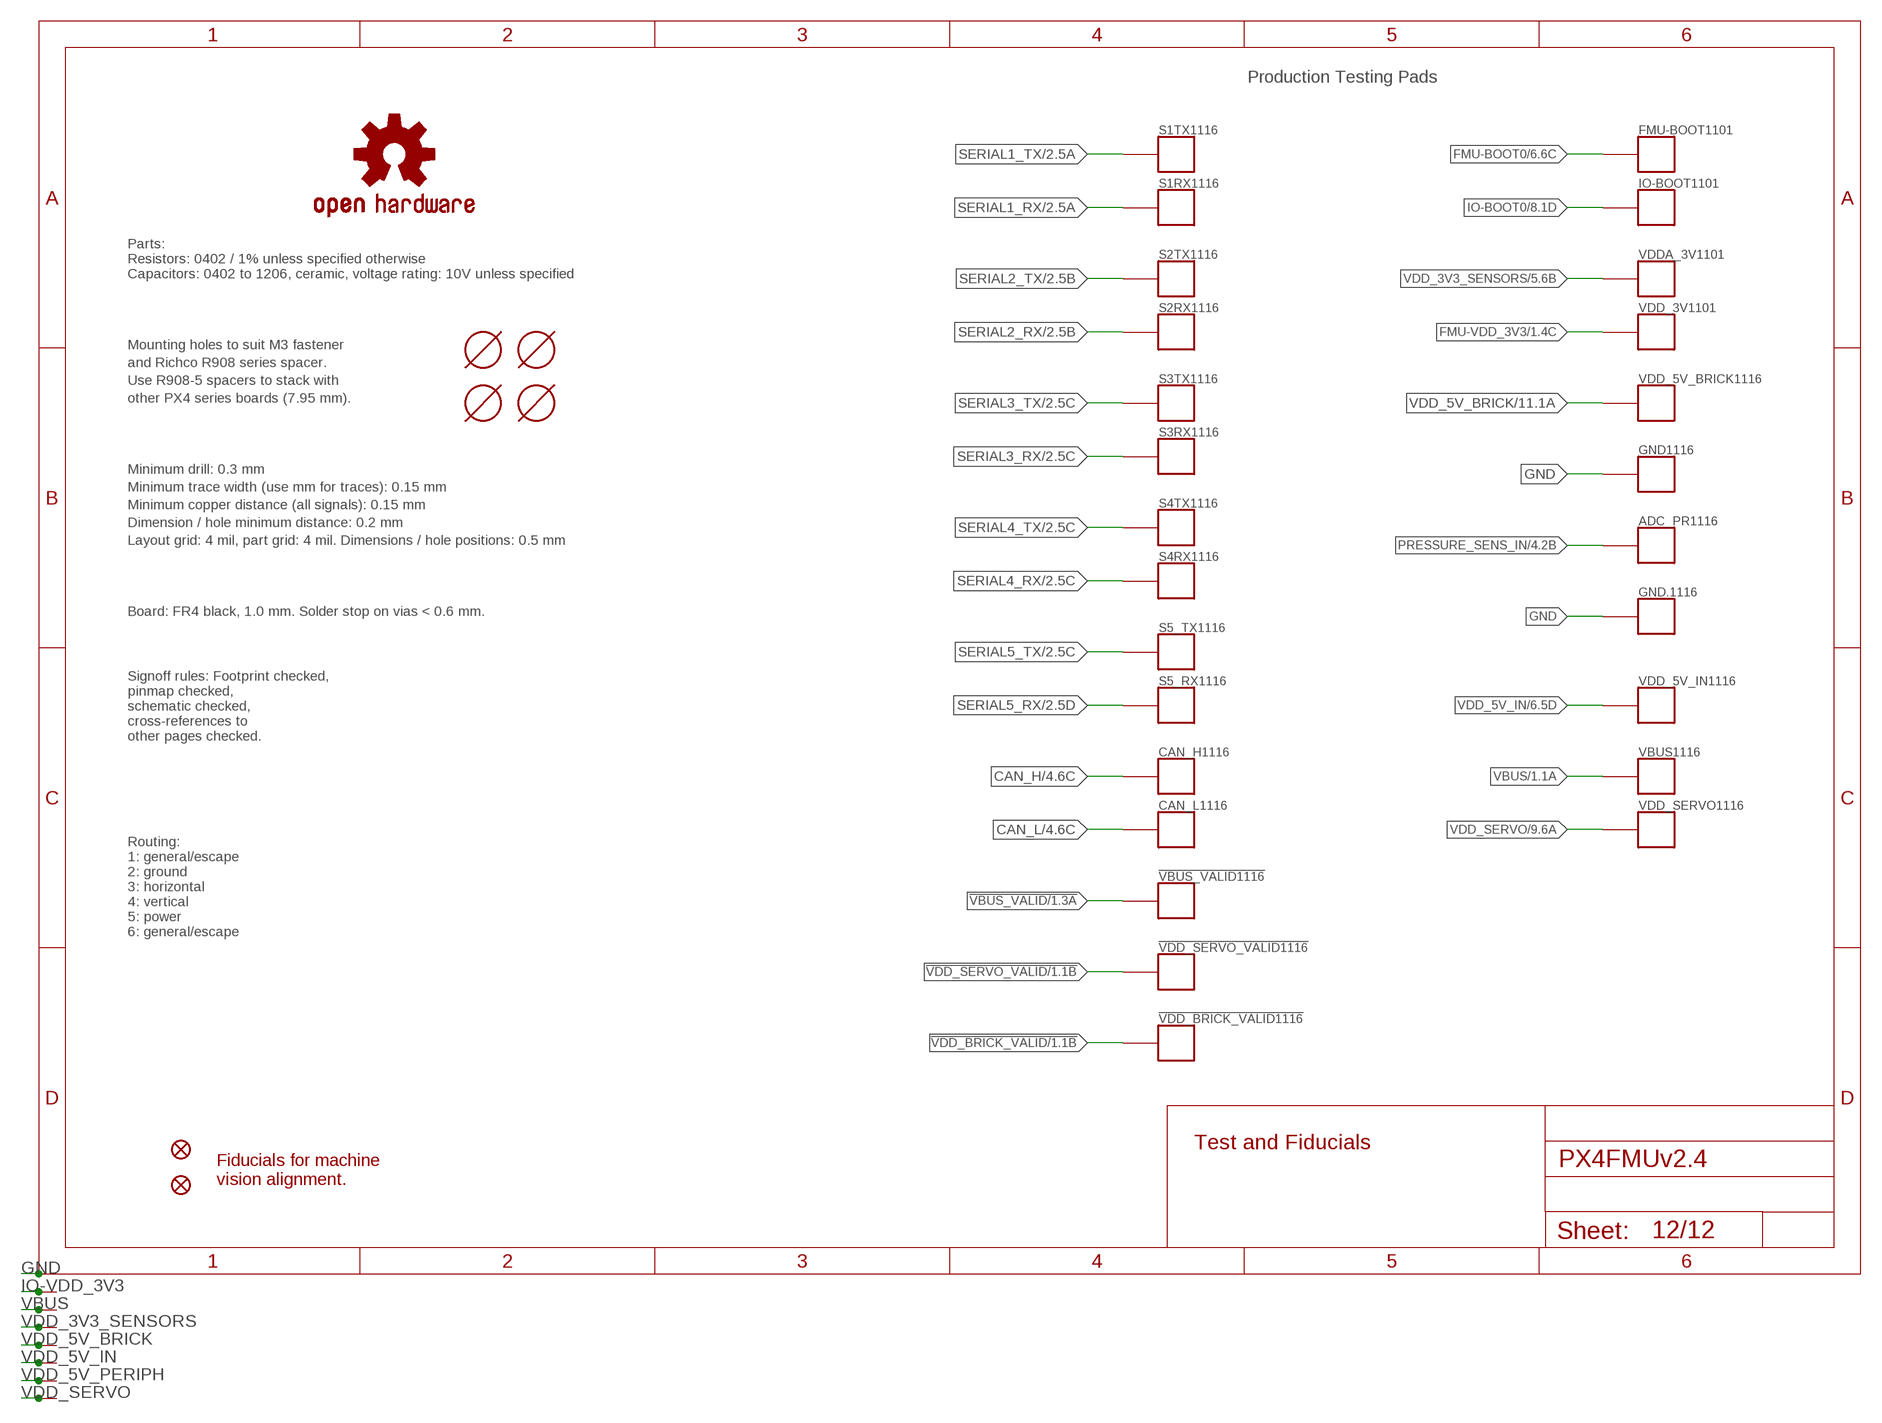
[diagram p11: schematic, sheet 12]

(export (version "E")
  (design (tool "Eeschema 10.0.6"))
  (components
    (comp (ref "C401")
      (value "0u1")
      (footprint "eagle-import:0402-CAP")
      (fields (field (name "PARTNO") "CC0402ZRY5V7BB104"))
      (libsource (lib "eagle-import") (part "CAP0402"))
    )
    (comp (ref "C402")
      (value "0u1")
      (footprint "eagle-import:0402-CAP")
      (fields (field (name "PARTNO") "CC0402ZRY5V7BB104"))
      (libsource (lib "eagle-import") (part "CAP0402"))
    )
    (comp (ref "D401")
      (value "PESD0402-140")
      (footprint "eagle-import:0402-TVS")
      (libsource (lib "eagle-import") (part "DIODE-TVS"))
    )
    (comp (ref "D402")
      (value "PESD0402-140")
      (footprint "eagle-import:0402-TVS")
      (libsource (lib "eagle-import") (part "DIODE-TVS"))
    )
    (comp (ref "D403")
      (value "PESD0402-140")
      (footprint "eagle-import:0402-TVS")
      (libsource (lib "eagle-import") (part "DIODE-TVS"))
    )
    (comp (ref "D404")
      (value "PESD0402-140")
      (footprint "eagle-import:0402-TVS")
      (libsource (lib "eagle-import") (part "DIODE-TVS"))
    )
    (comp (ref "J401")
      (value "DF13C-4P-1.25V")
      (footprint "eagle-import:DF13C-4P-1.25V")
      (fields (field (name "PARTNO") "DF13C-4P-1.25V(20)"))
      (libsource (lib "eagle-import") (part "DF13-4P-1.25V"))
    )
    (comp (ref "J402")
      (value "DF13C-3P-1.25V")
      (footprint "eagle-import:DF13C-3P-1.25V")
      (fields (field (name "PARTNO") "DF13C-3P-1.25V(20)"))
      (libsource (lib "eagle-import") (part "DF13-3P-1.25V"))
    )
    (comp (ref "J403")
      (value "DF13C-7P-1.25V")
      (footprint "eagle-import:DF13C-7P-1.25V")
      (fields (field (name "PARTNO") "DF13C-7P-1.25V(20)"))
      (libsource (lib "eagle-import") (part "DF13-7P-1.25V"))
    )
    (comp (ref "J404")
      (value "DF13C-5P-1.25V")
      (footprint "eagle-import:DF13C-5P-1.25V")
      (fields (field (name "PARTNO") "DF13C-5P-1.25V(20)"))
      (libsource (lib "eagle-import") (part "DF13-5P-1.25V"))
    )
    (comp (ref "J405")
      (value "DF13C-4P-1.25V")
      (footprint "eagle-import:DF13C-4P-1.25V")
      (fields (field (name "PARTNO") "DF13C-4P-1.25V(20)"))
      (libsource (lib "eagle-import") (part "DF13-4P-1.25V"))
    )
    (comp (ref "L401")
      (value "KNH16C104DA5TS")
      (footprint "eagle-import:KYOCERA-KNH16-DA")
      (libsource (lib "eagle-import") (part "KNH16C104DA5TS"))
    )
    (comp (ref "L402")
      (value "KNH16C104DA5TS")
      (footprint "eagle-import:KYOCERA-KNH16-DA")
      (libsource (lib "eagle-import") (part "KNH16C104DA5TS"))
    )
    (comp (ref "L403")
      (value "KNH16C104DA5TS")
      (footprint "eagle-import:KYOCERA-KNH16-DA")
      (libsource (lib "eagle-import") (part "KNH16C104DA5TS"))
    )
    (comp (ref "L404")
      (value "KNH16C104DA5TS")
      (footprint "eagle-import:KYOCERA-KNH16-DA")
      (libsource (lib "eagle-import") (part "KNH16C104DA5TS"))
    )
    (comp (ref "R401")
      (value "1K5")
      (footprint "eagle-import:0402-RES")
      (fields (field (name "PARTNO") "RC0402FR-071K5L"))
      (libsource (lib "eagle-import") (part "RESISTOR0402-RES"))
    )
    (comp (ref "R402")
      (value "1K5")
      (footprint "eagle-import:0402-RES")
      (fields (field (name "PARTNO") "RC0402FR-071K5L"))
      (libsource (lib "eagle-import") (part "RESISTOR0402-RES"))
    )
    (comp (ref "R403")
      (value "10K/0.1%")
      (footprint "eagle-import:0402-RES")
      (fields (field (name "PARTNO") "ERA-2AEB103X"))
      (libsource (lib "eagle-import") (part "RESISTOR0402-RES"))
    )
    (comp (ref "R404")
      (value "120R")
      (footprint "eagle-import:0402-RES")
      (fields (field (name "PARTNO") "RC0402FR-07120RL"))
      (libsource (lib "eagle-import") (part "RESISTOR0402-RES"))
    )
    (comp (ref "R405")
      (value "120R")
      (footprint "eagle-import:0402-RES")
      (fields (field (name "PARTNO") "RC0402FR-07120RL"))
      (libsource (lib "eagle-import") (part "RESISTOR0402-RES"))
    )
    (comp (ref "R406")
      (value "10K/0.1%")
      (footprint "eagle-import:0402-RES")
      (fields (field (name "PARTNO") "ERA-2AEB103X"))
      (libsource (lib "eagle-import") (part "RESISTOR0402-RES"))
    )
    (comp (ref "R407")
      (value "10K/0.1%")
      (footprint "eagle-import:0402-RES")
      (fields (field (name "PARTNO") "ERA-2AEB103X"))
      (libsource (lib "eagle-import") (part "RESISTOR0402-RES"))
    )
    (comp (ref "R408")
      (value "10K/0.1%")
      (footprint "eagle-import:0402-RES")
      (fields (field (name "PARTNO") "ERA-2AEB103X"))
      (libsource (lib "eagle-import") (part "RESISTOR0402-RES"))
    )
    (comp (ref "R409")
      (value "120R")
      (footprint "eagle-import:0402-RES")
      (fields (field (name "PARTNO") "RC0402FR-07120RL"))
      (libsource (lib "eagle-import") (part "RESISTOR0402-RES"))
    )
    (comp (ref "U401")
      (value "MAX3051")
      (footprint "eagle-import:SOT23-8")
      (fields (field (name "PARTNO") "MAX3051EKA"))
      (libsource (lib "eagle-import") (part "MAX3051MAX3051EKA"))
    )
    (comp (ref "C201")
      (value "0u1")
      (footprint "eagle-import:0402-CAP")
      (fields (field (name "PARTNO") "CC0402ZRY5V7BB104"))
      (libsource (lib "eagle-import") (part "CAP0402"))
    )
    (comp (ref "C202")
      (value "0u1")
      (footprint "eagle-import:0402-CAP")
      (fields (field (name "PARTNO") "CC0402ZRY5V7BB104"))
      (libsource (lib "eagle-import") (part "CAP0402"))
    )
    (comp (ref "D201")
      (value "PESD0402-140")
      (footprint "eagle-import:0402-TVS")
      (libsource (lib "eagle-import") (part "DIODE-TVS"))
    )
    (comp (ref "D202")
      (value "PESD0402-140")
      (footprint "eagle-import:0402-TVS")
      (libsource (lib "eagle-import") (part "DIODE-TVS"))
    )
    (comp (ref "D203")
      (value "PESD0402-140")
      (footprint "eagle-import:0402-TVS")
      (libsource (lib "eagle-import") (part "DIODE-TVS"))
    )
    (comp (ref "J201")
      (value "DF13C-6P-1.25V")
      (footprint "eagle-import:DF13C-6P-1.25V")
      (fields (field (name "PARTNO") "DF13C-6P-1.25V(20)"))
      (libsource (lib "eagle-import") (part "DF13-6P-1.25V"))
    )
    (comp (ref "J202")
      (value "DF13C-6P-1.25V")
      (footprint "eagle-import:DF13C-6P-1.25V")
      (fields (field (name "PARTNO") "DF13C-6P-1.25V(20)"))
      (libsource (lib "eagle-import") (part "DF13-6P-1.25V"))
    )
    (comp (ref "J203")
      (value "DF13C-6P-1.25V")
      (footprint "eagle-import:DF13C-6P-1.25V")
      (fields (field (name "PARTNO") "DF13C-6P-1.25V(20)"))
      (libsource (lib "eagle-import") (part "DF13-6P-1.25V"))
    )
    (comp (ref "J204")
      (value "DF13C-6P-1.25V")
      (footprint "eagle-import:DF13C-6P-1.25V")
      (fields (field (name "PARTNO") "DF13C-6P-1.25V(20)"))
      (libsource (lib "eagle-import") (part "DF13-6P-1.25V"))
    )
    (comp (ref "L201")
      (value "KNH16C104DA5TS")
      (footprint "eagle-import:KYOCERA-KNH16-DA")
      (libsource (lib "eagle-import") (part "KNH16C104DA5TS"))
    )
    (comp (ref "L202")
      (value "KNH16C104DA5TS")
      (footprint "eagle-import:KYOCERA-KNH16-DA")
      (libsource (lib "eagle-import") (part "KNH16C104DA5TS"))
    )
    (comp (ref "L203")
      (value "KNH16C104DA5TS")
      (footprint "eagle-import:KYOCERA-KNH16-DA")
      (libsource (lib "eagle-import") (part "KNH16C104DA5TS"))
    )
    (comp (ref "R201")
      (value "120R")
      (footprint "eagle-import:0402-RES")
      (fields (field (name "PARTNO") "RC0402FR-07120RL"))
      (libsource (lib "eagle-import") (part "RESISTOR0402-RES"))
    )
    (comp (ref "R202")
      (value "120R")
      (footprint "eagle-import:0402-RES")
      (fields (field (name "PARTNO") "RC0402FR-07120RL"))
      (libsource (lib "eagle-import") (part "RESISTOR0402-RES"))
    )
    (comp (ref "R203")
      (value "120R")
      (footprint "eagle-import:0402-RES")
      (fields (field (name "PARTNO") "RC0402FR-07120RL"))
      (libsource (lib "eagle-import") (part "RESISTOR0402-RES"))
    )
    (comp (ref "R204")
      (value "120R")
      (footprint "eagle-import:0402-RES")
      (fields (field (name "PARTNO") "RC0402FR-07120RL"))
      (libsource (lib "eagle-import") (part "RESISTOR0402-RES"))
    )
    (comp (ref "R205")
      (value "120R")
      (footprint "eagle-import:0402-RES")
      (fields (field (name "PARTNO") "RC0402FR-07120RL"))
      (libsource (lib "eagle-import") (part "RESISTOR0402-RES"))
    )
    (comp (ref "R206")
      (value "120R")
      (footprint "eagle-import:0402-RES")
      (fields (field (name "PARTNO") "RC0402FR-07120RL"))
      (libsource (lib "eagle-import") (part "RESISTOR0402-RES"))
    )
    (comp (ref "R207")
      (value "120R")
      (footprint "eagle-import:0402-RES")
      (fields (field (name "PARTNO") "RC0402FR-07120RL"))
      (libsource (lib "eagle-import") (part "RESISTOR0402-RES"))
    )
    (comp (ref "R208")
      (value "120R")
      (footprint "eagle-import:0402-RES")
      (fields (field (name "PARTNO") "RC0402FR-07120RL"))
      (libsource (lib "eagle-import") (part "RESISTOR0402-RES"))
    )
    (comp (ref "R209")
      (value "120R")
      (footprint "eagle-import:0402-RES")
      (fields (field (name "PARTNO") "RC0402FR-07120RL"))
      (libsource (lib "eagle-import") (part "RESISTOR0402-RES"))
    )
    (comp (ref "R210")
      (value "120R")
      (footprint "eagle-import:0402-RES")
      (fields (field (name "PARTNO") "RC0402FR-07120RL"))
      (libsource (lib "eagle-import") (part "RESISTOR0402-RES"))
    )
    (comp (ref "R211")
      (value "120R")
      (footprint "eagle-import:0402-RES")
      (fields (field (name "PARTNO") "RC0402FR-07120RL"))
      (libsource (lib "eagle-import") (part "RESISTOR0402-RES"))
    )
    (comp (ref "R212")
      (value "120R")
      (footprint "eagle-import:0402-RES")
      (fields (field (name "PARTNO") "RC0402FR-07120RL"))
      (libsource (lib "eagle-import") (part "RESISTOR0402-RES"))
    )
    (comp (ref "R213")
      (value "120R")
      (footprint "eagle-import:0402-RES")
      (fields (field (name "PARTNO") "RC0402FR-07120RL"))
      (libsource (lib "eagle-import") (part "RESISTOR0402-RES"))
    )
    (comp (ref "R214")
      (value "120R")
      (footprint "eagle-import:0402-RES")
      (fields (field (name "PARTNO") "RC0402FR-07120RL"))
      (libsource (lib "eagle-import") (part "RESISTOR0402-RES"))
    )
    (comp (ref "R215")
      (value "120R")
      (footprint "eagle-import:0402-RES")
      (fields (field (name "PARTNO") "RC0402FR-07120RL"))
      (libsource (lib "eagle-import") (part "RESISTOR0402-RES"))
    )
    (comp (ref "R216")
      (value "120R")
      (footprint "eagle-import:0402-RES")
      (fields (field (name "PARTNO") "RC0402FR-07120RL"))
      (libsource (lib "eagle-import") (part "RESISTOR0402-RES"))
    )
    (comp (ref "U201")
      (value "TXS0108QFN20")
      (footprint "eagle-import:QFN20-RGY")
      (fields (field (name "PARTNO") "TXS0108ERGYR"))
      (libsource (lib "eagle-import") (part "TXS0108QFN20"))
    )
    (comp (ref "U202")
      (value "TXS0108QFN20")
      (footprint "eagle-import:QFN20-RGY")
      (fields (field (name "PARTNO") "TXS0108ERGYR"))
      (libsource (lib "eagle-import") (part "TXS0108QFN20"))
    )
    (comp (ref "C501")
      (value "10u/10V")
      (footprint "eagle-import:0805-CAP")
      (fields (field (name "PARTNO") "CC0805ZKY5V6BB106"))
      (libsource (lib "eagle-import") (part "CAP0805"))
    )
    (comp (ref "C502")
      (value "0u1")
      (footprint "eagle-import:0402-CAP")
      (fields (field (name "PARTNO") "CC0402ZRY5V7BB104"))
      (libsource (lib "eagle-import") (part "CAP0402"))
    )
    (comp (ref "C503")
      (value "0u1")
      (footprint "eagle-import:0402-CAP")
      (fields (field (name "PARTNO") "CC0402ZRY5V7BB104"))
      (libsource (lib "eagle-import") (part "CAP0402"))
    )
    (comp (ref "C504")
      (value "10n")
      (footprint "eagle-import:0402-CAP")
      (fields (field (name "PARTNO") "CC0402KRX7R7BB103"))
      (libsource (lib "eagle-import") (part "CAP0402"))
    )
    (comp (ref "C505")
      (value "10n")
      (footprint "eagle-import:0402-CAP")
      (fields (field (name "PARTNO") "CC0402KRX7R7BB103"))
      (libsource (lib "eagle-import") (part "CAP0402"))
    )
    (comp (ref "C506")
      (value "10u/10V")
      (footprint "eagle-import:0805-CAP")
      (fields (field (name "PARTNO") "CC0805ZKY5V6BB106"))
      (libsource (lib "eagle-import") (part "CAP0805"))
    )
    (comp (ref "C507")
      (value "0u1")
      (footprint "eagle-import:0402-CAP")
      (fields (field (name "PARTNO") "CC0402ZRY5V7BB104"))
      (libsource (lib "eagle-import") (part "CAP0402"))
    )
    (comp (ref "C508")
      (value "0u1")
      (footprint "eagle-import:0402-CAP")
      (fields (field (name "PARTNO") "CC0402ZRY5V7BB104"))
      (libsource (lib "eagle-import") (part "CAP0402"))
    )
    (comp (ref "C509")
      (value "10u/10V")
      (footprint "eagle-import:0805-CAP")
      (fields (field (name "PARTNO") "CC0805ZKY5V6BB106"))
      (libsource (lib "eagle-import") (part "CAP0805"))
    )
    (comp (ref "C510")
      (value "0u47")
      (footprint "eagle-import:0402-CAP")
      (fields (field (name "PARTNO") "C1005X5R1C474K050BC"))
      (libsource (lib "eagle-import") (part "CAP0402"))
    )
    (comp (ref "C511")
      (value "10u/10V")
      (footprint "eagle-import:0805-CAP")
      (fields (field (name "PARTNO") "CC0805ZKY5V6BB106"))
      (libsource (lib "eagle-import") (part "CAP0805"))
    )
    (comp (ref "C512")
      (value "2u2")
      (footprint "eagle-import:0603-CAP")
      (fields (field (name "PARTNO") "CC0402ZRY5V7BB104"))
      (libsource (lib "eagle-import") (part "CAP0603"))
    )
    (comp (ref "C513")
      (value "2u2")
      (footprint "eagle-import:0603-CAP")
      (fields (field (name "PARTNO") "CC0402ZRY5V7BB104"))
      (libsource (lib "eagle-import") (part "CAP0603"))
    )
    (comp (ref "C514")
      (value "0u1")
      (footprint "eagle-import:0402-CAP")
      (fields (field (name "PARTNO") "CC0402ZRY5V7BB104"))
      (libsource (lib "eagle-import") (part "CAP0402"))
    )
    (comp (ref "C515")
      (value "0u01")
      (footprint "eagle-import:0603-CAP")
      (fields (field (name "PARTNO") "GRM155R71E103JA01J"))
      (libsource (lib "eagle-import") (part "CAP0603"))
    )
    (comp (ref "U501")
      (value "L3GD20")
      (footprint "eagle-import:L3G4200DH-MAN")
      (libsource (lib "eagle-import") (part "L3G4200DH-LL"))
    )
    (comp (ref "U502")
      (value "L3GD20H")
      (footprint "eagle-import:LGA-16L")
      (libsource (lib "eagle-import") (part "L3GD20H"))
    )
    (comp (ref "U504")
      (value "LSM303D")
      (footprint "eagle-import:LGA-16L")
      (libsource (lib "eagle-import") (part "LSM303D"))
    )
    (comp (ref "U505")
      (value "MPU-6000")
      (footprint "eagle-import:QFN-24")
      (libsource (lib "eagle-import") (part "MPU-6000"))
    )
    (comp (ref "U506")
      (value "MS5611-01BA")
      (footprint "eagle-import:MS5611-01BA")
      (libsource (lib "eagle-import") (part "MS5611-01BA"))
    )
    (comp (ref "X503")
      (value "0512811094")
      (footprint "eagle-import:51281-1094")
      (fields (field (name "PARTNO") "0781191109"))
      (libsource (lib "eagle-import") (part "CONN_FPC_10RA"))
    )
    (comp (ref "C1101")
      (value "22u/25V")
      (footprint "eagle-import:0805-CAP")
      (fields (field (name "PARTNO") "CL21A226MAQNNNE"))
      (libsource (lib "eagle-import") (part "CAP0805"))
    )
    (comp (ref "C1102")
      (value "22u/25V")
      (footprint "eagle-import:0805-CAP")
      (fields (field (name "PARTNO") "CL21A226MAQNNNE"))
      (libsource (lib "eagle-import") (part "CAP0805"))
    )
    (comp (ref "C1103")
      (value "22u/25V")
      (footprint "eagle-import:0805-CAP")
      (fields (field (name "PARTNO") "CL21A226MAQNNNE"))
      (libsource (lib "eagle-import") (part "CAP0805"))
    )
    (comp (ref "C1104")
      (value "100u")
      (footprint "eagle-import:1206-CAP")
      (fields (field (name "PARTNO") "C3216X5R1A107M160AC"))
      (libsource (lib "eagle-import") (part "CAP1206"))
    )
    (comp (ref "C1105")
      (value "0u1")
      (footprint "eagle-import:0402-CAP")
      (fields (field (name "PARTNO") "CC0402ZRY5V7BB104"))
      (libsource (lib "eagle-import") (part "CAP0402"))
    )
    (comp (ref "C1106")
      (value "0u1")
      (footprint "eagle-import:0402-CAP")
      (fields (field (name "PARTNO") "CC0402ZRY5V7BB104"))
      (libsource (lib "eagle-import") (part "CAP0402"))
    )
    (comp (ref "C1107")
      (value "0u1")
      (footprint "eagle-import:0402-CAP")
      (fields (field (name "PARTNO") "CC0402ZRY5V7BB104"))
      (libsource (lib "eagle-import") (part "CAP0402"))
    )
    (comp (ref "C1108")
      (value "1000p/25V")
      (footprint "eagle-import:0402-CAP")
      (fields (field (name "PARTNO") "GRM1555C1E102JA01D"))
      (libsource (lib "eagle-import") (part "CAP0402"))
    )
    (comp (ref "C1109")
      (value "1000p/25V")
      (footprint "eagle-import:0402-CAP")
      (fields (field (name "PARTNO") "GRM1555C1E102JA01D"))
      (libsource (lib "eagle-import") (part "CAP0402"))
    )
    (comp (ref "C1110")
      (value "1000p/25V")
      (footprint "eagle-import:0402-CAP")
      (fields (field (name "PARTNO") "GRM1555C1E102JA01D"))
      (libsource (lib "eagle-import") (part "CAP0402"))
    )
    (comp (ref "J601")
      (value "DF13C-6P-1.25V")
      (footprint "eagle-import:DF13C-6P-1.25V")
      (fields (field (name "PARTNO") "DF13C-6P-1.25V(20)"))
      (libsource (lib "eagle-import") (part "DF13-6P-1.25V"))
    )
    (comp (ref "L1101")
      (value "KNH16C104DA5TS")
      (footprint "eagle-import:KYOCERA-KNH16-DA")
      (libsource (lib "eagle-import") (part "KNH16C104DA5TS"))
    )
    (comp (ref "L1102")
      (value "KNH16C104DA5TS")
      (footprint "eagle-import:KYOCERA-KNH16-DA")
      (libsource (lib "eagle-import") (part "KNH16C104DA5TS"))
    )
    (comp (ref "R1101")
      (value "10K/0.1%")
      (footprint "eagle-import:0402-RES")
      (fields (field (name "PARTNO") "ERA-2AEB103X"))
      (libsource (lib "eagle-import") (part "RESISTOR0402-RES"))
    )
    (comp (ref "R1102")
      (value "10K/0.1%")
      (footprint "eagle-import:0402-RES")
      (fields (field (name "PARTNO") "ERA-2AEB103X"))
      (libsource (lib "eagle-import") (part "RESISTOR0402-RES"))
    )
    (comp (ref "R1103")
      (value "1M")
      (footprint "eagle-import:0402-RES")
      (fields (field (name "PARTNO") "RC0402FR-071ML"))
      (libsource (lib "eagle-import") (part "RESISTOR0402-RES"))
    )
    (comp (ref "R1104")
      (value "1M")
      (footprint "eagle-import:0402-RES")
      (fields (field (name "PARTNO") "RC0402FR-071ML"))
      (libsource (lib "eagle-import") (part "RESISTOR0402-RES"))
    )
    (comp (ref "R1105")
      (value "453K")
      (footprint "eagle-import:0402-RES")
      (fields (field (name "PARTNO") "RMCF0402FT453K"))
      (libsource (lib "eagle-import") (part "RESISTOR0402-RES"))
    )
    (comp (ref "R1106")
      (value "56K")
      (footprint "eagle-import:0402-RES")
      (fields (field (name "PARTNO") "ERA-2AEB563X"))
      (libsource (lib "eagle-import") (part "RESISTOR0402-RES"))
    )
    (comp (ref "R1107")
      (value "105K")
      (footprint "eagle-import:0402-RES")
      (fields (field (name "PARTNO") "ERJ-2RKF1053X"))
      (libsource (lib "eagle-import") (part "RESISTOR0402-RES"))
    )
    (comp (ref "R1109")
      (value "453K")
      (footprint "eagle-import:0402-RES")
      (fields (field (name "PARTNO") "RMCF0402FT453K"))
      (libsource (lib "eagle-import") (part "RESISTOR0402-RES"))
    )
    (comp (ref "R1110")
      (value "56K")
      (footprint "eagle-import:0402-RES")
      (fields (field (name "PARTNO") "ERA-2AEB563X"))
      (libsource (lib "eagle-import") (part "RESISTOR0402-RES"))
    )
    (comp (ref "R1111")
      (value "105K")
      (footprint "eagle-import:0402-RES")
      (fields (field (name "PARTNO") "ERJ-2RKF1053X"))
      (libsource (lib "eagle-import") (part "RESISTOR0402-RES"))
    )
    (comp (ref "R1112")
      (value "453K")
      (footprint "eagle-import:0402-RES")
      (fields (field (name "PARTNO") "RMCF0402FT453K"))
      (libsource (lib "eagle-import") (part "RESISTOR0402-RES"))
    )
    (comp (ref "R1113")
      (value "56K")
      (footprint "eagle-import:0402-RES")
      (fields (field (name "PARTNO") "ERA-2AEB563X"))
      (libsource (lib "eagle-import") (part "RESISTOR0402-RES"))
    )
    (comp (ref "R1114")
      (value "105K")
      (footprint "eagle-import:0402-RES")
      (fields (field (name "PARTNO") "ERJ-2RKF1053X"))
      (libsource (lib "eagle-import") (part "RESISTOR0402-RES"))
    )
    (comp (ref "R1115")
      (value "0R")
      (footprint "eagle-import:0402-RES")
      (fields (field (name "PARTNO") "ERJ-2GE0R00X"))
      (libsource (lib "eagle-import") (part "RESISTOR0402-RES"))
    )
    (comp (ref "RN1101")
      (value "1M")
      (footprint "eagle-import:EXB28V")
      (fields (field (name "PARTNO") "EXB-28V105JX"))
      (libsource (lib "eagle-import") (part "4R-NEXB28V"))
    )
    (comp (ref "U1101")
      (value "LTC4417")
      (footprint "eagle-import:MO-220")
      (fields (field (name "PARTNO") "LTC4417IUF#PBF"))
      (libsource (lib "eagle-import") (part "LTC4117"))
    )
    (comp (ref "U1102")
      (value "NTHD4102PT1G")
      (footprint "eagle-import:1206-8")
      (fields (field (name "PARTNO") "NTHD4102PT1G"))
      (libsource (lib "eagle-import") (part "MOSFET-DUAL-PCHANNEL-CHIPFET"))
    )
    (comp (ref "U1103")
      (value "NTHD4102PT1G")
      (footprint "eagle-import:1206-8")
      (fields (field (name "PARTNO") "NTHD4102PT1G"))
      (libsource (lib "eagle-import") (part "MOSFET-DUAL-PCHANNEL-CHIPFET"))
    )
    (comp (ref "U1104")
      (value "NTHD4102PT1G")
      (footprint "eagle-import:1206-8")
      (fields (field (name "PARTNO") "NTHD4102PT1G"))
      (libsource (lib "eagle-import") (part "MOSFET-DUAL-PCHANNEL-CHIPFET"))
    )
    (comp (ref "!VBUS_VALID1116")
      (value "PAD.04")
      (footprint "eagle-import:PAD.04X.04")
      (libsource (lib "eagle-import") (part "PAD.04"))
    )
    (comp (ref "!VDD_BRICK_VALID1116")
      (value "PAD.04")
      (footprint "eagle-import:PAD.04X.04")
      (libsource (lib "eagle-import") (part "PAD.04"))
    )
    (comp (ref "!VDD_SERVO_VALID1116")
      (value "PAD.04")
      (footprint "eagle-import:PAD.04X.04")
      (libsource (lib "eagle-import") (part "PAD.04"))
    )
    (comp (ref "ADC_PR1116")
      (value "PAD.04")
      (footprint "eagle-import:PAD.04X.04")
      (libsource (lib "eagle-import") (part "PAD.04"))
    )
    (comp (ref "CAN_H1116")
      (value "PAD.04")
      (footprint "eagle-import:PAD.04X.04")
      (libsource (lib "eagle-import") (part "PAD.04"))
    )
    (comp (ref "CAN_L1116")
      (value "PAD.04")
      (footprint "eagle-import:PAD.04X.04")
      (libsource (lib "eagle-import") (part "PAD.04"))
    )
    (comp (ref "FMU-BOOT1101")
      (value "PAD.04")
      (footprint "eagle-import:PAD.04X.04")
      (libsource (lib "eagle-import") (part "PAD.04"))
    )
    (comp (ref "GND.1116")
      (value "PAD.04")
      (footprint "eagle-import:PAD.04X.04")
      (libsource (lib "eagle-import") (part "PAD.04"))
    )
    (comp (ref "GND1116")
      (value "PAD.04")
      (footprint "eagle-import:PAD.04X.04")
      (libsource (lib "eagle-import") (part "PAD.04"))
    )
    (comp (ref "IO-BOOT1101")
      (value "PAD.04")
      (footprint "eagle-import:PAD.04X.04")
      (libsource (lib "eagle-import") (part "PAD.04"))
    )
    (comp (ref "JP1")
      (value "FIDUCIAL1.5X3")
      (footprint "eagle-import:FIDUCIAL-1.5X3")
      (libsource (lib "eagle-import") (part "FIDUCIAL1.5X3"))
    )
    (comp (ref "JP2")
      (value "FIDUCIAL1.5X3")
      (footprint "eagle-import:FIDUCIAL-1.5X3")
      (libsource (lib "eagle-import") (part "FIDUCIAL1.5X3"))
    )
    (comp (ref "M3_MOUNT1101")
      (value "MOUNT-HOLE3.1MM")
      (footprint "eagle-import:MOUNT-HOLE3.1")
      (libsource (lib "eagle-import") (part "MOUNT-HOLE3.1MM"))
    )
    (comp (ref "M3_MOUNT1102")
      (value "MOUNT-HOLE3.1MM")
      (footprint "eagle-import:MOUNT-HOLE3.1")
      (libsource (lib "eagle-import") (part "MOUNT-HOLE3.1MM"))
    )
    (comp (ref "M3_MOUNT1103")
      (value "MOUNT-HOLE3.1MM")
      (footprint "eagle-import:MOUNT-HOLE3.1")
      (libsource (lib "eagle-import") (part "MOUNT-HOLE3.1MM"))
    )
    (comp (ref "M3_MOUNT1104")
      (value "MOUNT-HOLE3.1MM")
      (footprint "eagle-import:MOUNT-HOLE3.1")
      (libsource (lib "eagle-import") (part "MOUNT-HOLE3.1MM"))
    )
    (comp (ref "OSHW_LOGO1116")
      (value "OSHW-LOGOS")
      (footprint "eagle-import:OSHW-LOGO-S")
      (libsource (lib "eagle-import") (part "OSHW-LOGOS"))
    )
    (comp (ref "S1RX1116")
      (value "PAD.04")
      (footprint "eagle-import:PAD.04X.04")
      (libsource (lib "eagle-import") (part "PAD.04"))
    )
    (comp (ref "S1TX1116")
      (value "PAD.04")
      (footprint "eagle-import:PAD.04X.04")
      (libsource (lib "eagle-import") (part "PAD.04"))
    )
    (comp (ref "S2RX1116")
      (value "PAD.04")
      (footprint "eagle-import:PAD.04X.04")
      (libsource (lib "eagle-import") (part "PAD.04"))
    )
    (comp (ref "S2TX1116")
      (value "PAD.04")
      (footprint "eagle-import:PAD.04X.04")
      (libsource (lib "eagle-import") (part "PAD.04"))
    )
    (comp (ref "S3RX1116")
      (value "PAD.04")
      (footprint "eagle-import:PAD.04X.04")
      (libsource (lib "eagle-import") (part "PAD.04"))
    )
    (comp (ref "S3TX1116")
      (value "PAD.04")
      (footprint "eagle-import:PAD.04X.04")
      (libsource (lib "eagle-import") (part "PAD.04"))
    )
    (comp (ref "S4RX1116")
      (value "PAD.04")
      (footprint "eagle-import:PAD.04X.04")
      (libsource (lib "eagle-import") (part "PAD.04"))
    )
    (comp (ref "S4TX1116")
      (value "PAD.04")
      (footprint "eagle-import:PAD.04X.04")
      (libsource (lib "eagle-import") (part "PAD.04"))
    )
    (comp (ref "S5_RX1116")
      (value "PAD.04")
      (footprint "eagle-import:PAD.04X.04")
      (libsource (lib "eagle-import") (part "PAD.04"))
    )
    (comp (ref "S5_TX1116")
      (value "PAD.04")
      (footprint "eagle-import:PAD.04X.04")
      (libsource (lib "eagle-import") (part "PAD.04"))
    )
    (comp (ref "VBUS1116")
      (value "PAD.04")
      (footprint "eagle-import:PAD.04X.04")
      (libsource (lib "eagle-import") (part "PAD.04"))
    )
    (comp (ref "VDDA_3V1101")
      (value "PAD.04")
      (footprint "eagle-import:PAD.04X.04")
      (libsource (lib "eagle-import") (part "PAD.04"))
    )
    (comp (ref "VDD_3V1101")
      (value "PAD.04")
      (footprint "eagle-import:PAD.04X.04")
      (libsource (lib "eagle-import") (part "PAD.04"))
    )
    (comp (ref "VDD_5V_BRICK1116")
      (value "PAD.04")
      (footprint "eagle-import:PAD.04X.04")
      (libsource (lib "eagle-import") (part "PAD.04"))
    )
    (comp (ref "VDD_5V_IN1116")
      (value "PAD.04")
      (footprint "eagle-import:PAD.04X.04")
      (libsource (lib "eagle-import") (part "PAD.04"))
    )
    (comp (ref "VDD_SERVO1116")
      (value "PAD.04")
      (footprint "eagle-import:PAD.04X.04")
      (libsource (lib "eagle-import") (part "PAD.04"))
    )
    (comp (ref "VP_0")
      (value "VPDEV0")
      (footprint "eagle-import:VPAC0")
      (libsource (lib "eagle-import") (part "VPDEV0"))
    )
    (comp (ref "VP_1")
      (value "VPDEV0")
      (footprint "eagle-import:VPAC0")
      (libsource (lib "eagle-import") (part "VPDEV0"))
    )
    (comp (ref "VP_2")
      (value "VPDEV0")
      (footprint "eagle-import:VPAC0")
      (libsource (lib "eagle-import") (part "VPDEV0"))
    )
    (comp (ref "VP_3")
      (value "VPDEV0")
      (footprint "eagle-import:VPAC0")
      (libsource (lib "eagle-import") (part "VPDEV0"))
    )
    (comp (ref "VP_4")
      (value "VPDEV1")
      (footprint "eagle-import:VPAC1")
      (libsource (lib "eagle-import") (part "VPDEV1"))
    )
    (comp (ref "VP_5")
      (value "VPDEV1")
      (footprint "eagle-import:VPAC1")
      (libsource (lib "eagle-import") (part "VPDEV1"))
    )
    (comp (ref "VP_6")
      (value "VPDEV1")
      (footprint "eagle-import:VPAC1")
      (libsource (lib "eagle-import") (part "VPDEV1"))
    )
    (comp (ref "VP_7")
      (value "VPDEV1")
      (footprint "eagle-import:VPAC1")
      (libsource (lib "eagle-import") (part "VPDEV1"))
    )
    (comp (ref "VP_8")
      (value "VPDEV1")
      (footprint "eagle-import:VPAC1")
      (libsource (lib "eagle-import") (part "VPDEV1"))
    )
    (comp (ref "VP_9")
      (value "VPDEV1")
      (footprint "eagle-import:VPAC1")
      (libsource (lib "eagle-import") (part "VPDEV1"))
    )
    (comp (ref "VP_10")
      (value "VPDEV1")
      (footprint "eagle-import:VPAC1")
      (libsource (lib "eagle-import") (part "VPDEV1"))
    )
    (comp (ref "VP_11")
      (value "VPDEV1")
      (footprint "eagle-import:VPAC1")
      (libsource (lib "eagle-import") (part "VPDEV1"))
    )
    (comp (ref "VP_12")
      (value "VPDEV1")
      (footprint "eagle-import:VPAC1")
      (libsource (lib "eagle-import") (part "VPDEV1"))
    )
    (comp (ref "VP_13")
      (value "VPDEV1")
      (footprint "eagle-import:VPAC1")
      (libsource (lib "eagle-import") (part "VPDEV1"))
    )
    (comp (ref "VP_14")
      (value "VPDEV1")
      (footprint "eagle-import:VPAC1")
      (libsource (lib "eagle-import") (part "VPDEV1"))
    )
    (comp (ref "VP_15")
      (value "VPDEV1")
      (footprint "eagle-import:VPAC1")
      (libsource (lib "eagle-import") (part "VPDEV1"))
    )
    (comp (ref "VP_16")
      (value "VPDEV1")
      (footprint "eagle-import:VPAC1")
      (libsource (lib "eagle-import") (part "VPDEV1"))
    )
    (comp (ref "VP_17")
      (value "VPDEV1")
      (footprint "eagle-import:VPAC1")
      (libsource (lib "eagle-import") (part "VPDEV1"))
    )
    (comp (ref "VP_18")
      (value "VPDEV1")
      (footprint "eagle-import:VPAC1")
      (libsource (lib "eagle-import") (part "VPDEV1"))
    )
    (comp (ref "VP_19")
      (value "VPDEV1")
      (footprint "eagle-import:VPAC1")
      (libsource (lib "eagle-import") (part "VPDEV1"))
    )
    (comp (ref "VP_20")
      (value "VPDEV1")
      (footprint "eagle-import:VPAC1")
      (libsource (lib "eagle-import") (part "VPDEV1"))
    )
    (comp (ref "VP_21")
      (value "VPDEV1")
      (footprint "eagle-import:VPAC1")
      (libsource (lib "eagle-import") (part "VPDEV1"))
    )
    (comp (ref "VP_22")
      (value "VPDEV1")
      (footprint "eagle-import:VPAC1")
      (libsource (lib "eagle-import") (part "VPDEV1"))
    )
    (comp (ref "VP_23")
      (value "VPDEV1")
      (footprint "eagle-import:VPAC1")
      (libsource (lib "eagle-import") (part "VPDEV1"))
    )
    (comp (ref "VP_24")
      (value "VPDEV1")
      (footprint "eagle-import:VPAC1")
      (libsource (lib "eagle-import") (part "VPDEV1"))
    )
    (comp (ref "VP_25")
      (value "VPDEV1")
      (footprint "eagle-import:VPAC1")
      (libsource (lib "eagle-import") (part "VPDEV1"))
    )
    (comp (ref "VP_26")
      (value "VPDEV1")
      (footprint "eagle-import:VPAC1")
      (libsource (lib "eagle-import") (part "VPDEV1"))
    )
    (comp (ref "VP_27")
      (value "VPDEV1")
      (footprint "eagle-import:VPAC1")
      (libsource (lib "eagle-import") (part "VPDEV1"))
    )
    (comp (ref "VP_28")
      (value "VPDEV1")
      (footprint "eagle-import:VPAC1")
      (libsource (lib "eagle-import") (part "VPDEV1"))
    )
    (comp (ref "VP_29")
      (value "VPDEV1")
      (footprint "eagle-import:VPAC1")
      (libsource (lib "eagle-import") (part "VPDEV1"))
    )
    (comp (ref "VP_30")
      (value "VPDEV1")
      (footprint "eagle-import:VPAC1")
      (libsource (lib "eagle-import") (part "VPDEV1"))
    )
    (comp (ref "VP_31")
      (value "VPDEV1")
      (footprint "eagle-import:VPAC1")
      (libsource (lib "eagle-import") (part "VPDEV1"))
    )
    (comp (ref "VP_32")
      (value "VPDEV1")
      (footprint "eagle-import:VPAC1")
      (libsource (lib "eagle-import") (part "VPDEV1"))
    )
    (comp (ref "VP_33")
      (value "VPDEV0")
      (footprint "eagle-import:VPAC0")
      (libsource (lib "eagle-import") (part "VPDEV0"))
    )
    (comp (ref "VP_34")
      (value "VPDEV0")
      (footprint "eagle-import:VPAC0")
      (libsource (lib "eagle-import") (part "VPDEV0"))
    )
    (comp (ref "VP_35")
      (value "VPDEV0")
      (footprint "eagle-import:VPAC0")
      (libsource (lib "eagle-import") (part "VPDEV0"))
    )
    (comp (ref "VP_36")
      (value "VPDEV1")
      (footprint "eagle-import:VPAC1")
      (libsource (lib "eagle-import") (part "VPDEV1"))
    )
    (comp (ref "VP_37")
      (value "VPDEV1")
      (footprint "eagle-import:VPAC1")
      (libsource (lib "eagle-import") (part "VPDEV1"))
    )
    (comp (ref "VP_38")
      (value "VPDEV2")
      (footprint "eagle-import:VPAC2")
      (libsource (lib "eagle-import") (part "VPDEV2"))
    )
    (comp (ref "VP_39")
      (value "VPDEV1")
      (footprint "eagle-import:VPAC1")
      (libsource (lib "eagle-import") (part "VPDEV1"))
    )
    (comp (ref "VP_40")
      (value "VPDEV1")
      (footprint "eagle-import:VPAC1")
      (libsource (lib "eagle-import") (part "VPDEV1"))
    )
    (comp (ref "VP_41")
      (value "VPDEV0")
      (footprint "eagle-import:VPAC0")
      (libsource (lib "eagle-import") (part "VPDEV0"))
    )
    (comp (ref "VP_42")
      (value "VPDEV0")
      (footprint "eagle-import:VPAC0")
      (libsource (lib "eagle-import") (part "VPDEV0"))
    )
    (comp (ref "VP_43")
      (value "VPDEV0")
      (footprint "eagle-import:VPAC0")
      (libsource (lib "eagle-import") (part "VPDEV0"))
    )
    (comp (ref "VP_44")
      (value "VPDEV1")
      (footprint "eagle-import:VPAC1")
      (libsource (lib "eagle-import") (part "VPDEV1"))
    )
    (comp (ref "VP_45")
      (value "VPDEV1")
      (footprint "eagle-import:VPAC1")
      (libsource (lib "eagle-import") (part "VPDEV1"))
    )
    (comp (ref "VP_46")
      (value "VPDEV1")
      (footprint "eagle-import:VPAC1")
      (libsource (lib "eagle-import") (part "VPDEV1"))
    )
    (comp (ref "VP_47")
      (value "VPDEV1")
      (footprint "eagle-import:VPAC1")
      (libsource (lib "eagle-import") (part "VPDEV1"))
    )
    (comp (ref "VP_48")
      (value "VPDEV1")
      (footprint "eagle-import:VPAC1")
      (libsource (lib "eagle-import") (part "VPDEV1"))
    )
    (comp (ref "VP_49")
      (value "VPDEV1")
      (footprint "eagle-import:VPAC1")
      (libsource (lib "eagle-import") (part "VPDEV1"))
    )
    (comp (ref "VP_50")
      (value "VPDEV1")
      (footprint "eagle-import:VPAC1")
      (libsource (lib "eagle-import") (part "VPDEV1"))
    )
    (comp (ref "VP_51")
      (value "VPDEV0")
      (footprint "eagle-import:VPAC0")
      (libsource (lib "eagle-import") (part "VPDEV0"))
    )
    (comp (ref "VP_52")
      (value "VPDEV0")
      (footprint "eagle-import:VPAC0")
      (libsource (lib "eagle-import") (part "VPDEV0"))
    )
    (comp (ref "VP_53")
      (value "VPDEV0")
      (footprint "eagle-import:VPAC0")
      (libsource (lib "eagle-import") (part "VPDEV0"))
    )
    (comp (ref "VP_54")
      (value "VPDEV0")
      (footprint "eagle-import:VPAC0")
      (libsource (lib "eagle-import") (part "VPDEV0"))
    )
    (comp (ref "VP_55")
      (value "VPDEV0")
      (footprint "eagle-import:VPAC0")
      (libsource (lib "eagle-import") (part "VPDEV0"))
    )
    (comp (ref "VP_56")
      (value "VPDEV0")
      (footprint "eagle-import:VPAC0")
      (libsource (lib "eagle-import") (part "VPDEV0"))
    )
    (comp (ref "VP_57")
      (value "VPDEV0")
      (footprint "eagle-import:VPAC0")
      (libsource (lib "eagle-import") (part "VPDEV0"))
    )
    (comp (ref "VP_58")
      (value "VPDEV0")
      (footprint "eagle-import:VPAC0")
      (libsource (lib "eagle-import") (part "VPDEV0"))
    )
    (comp (ref "VP_59")
      (value "VPDEV0")
      (footprint "eagle-import:VPAC0")
      (libsource (lib "eagle-import") (part "VPDEV0"))
    )
    (comp (ref "VP_60")
      (value "VPDEV0")
      (footprint "eagle-import:VPAC0")
      (libsource (lib "eagle-import") (part "VPDEV0"))
    )
    (comp (ref "VP_61")
      (value "VPDEV0")
      (footprint "eagle-import:VPAC0")
      (libsource (lib "eagle-import") (part "VPDEV0"))
    )
    (comp (ref "C101")
      (value "0u1")
      (footprint "eagle-import:0402-CAP")
      (fields (field (name "PARTNO") "CC0402ZRY5V7BB104"))
      (libsource (lib "eagle-import") (part "CAP0402"))
    )
    (comp (ref "C102")
      (value "8p")
      (footprint "eagle-import:0402-CAP")
      (fields (field (name "PARTNO") "C1005C0G1H080C"))
      (libsource (lib "eagle-import") (part "CAP0402"))
    )
    (comp (ref "C103")
      (value "8p")
      (footprint "eagle-import:0402-CAP")
      (fields (field (name "PARTNO") "C1005C0G1H080C"))
      (libsource (lib "eagle-import") (part "CAP0402"))
    )
    (comp (ref "R101")
      (value "470R")
      (footprint "eagle-import:0402-RES")
      (fields (field (name "PARTNO") "RC0402FR-07470RL"))
      (libsource (lib "eagle-import") (part "RESISTOR0402-RES"))
    )
    (comp (ref "R102")
      (value "10K")
      (footprint "eagle-import:0402-RES")
      (fields (field (name "PARTNO") "RC0402FR-0710KL"))
      (libsource (lib "eagle-import") (part "RESISTOR0402-RES"))
    )
    (comp (ref "U101")
      (value "STM32F4X7VX")
      (footprint "eagle-import:TQFP100")
      (fields (field (name "PARTNO") "STM32F427VI"))
      (libsource (lib "eagle-import") (part "STM32F4X7VX"))
    )
    (comp (ref "U102")
      (value "FM25V01")
      (footprint "eagle-import:SO08")
      (fields (field (name "PARTNO") "FM25V01-G"))
      (libsource (lib "eagle-import") (part "FM25V01"))
    )
    (comp (ref "X101")
      (value "3.2x2.5 mm / 24 MHz / 15 ppm")
      (footprint "eagle-import:OSCILLATOR-3.2X2.5")
      (fields (field (name "PARTNO") "NX3225SA-24.000000MHZ"))
      (libsource (lib "eagle-import") (part "OSCILLATOR-3.2X2.5"))
    )
    (comp (ref "B601")
      (value "MS621FE")
      (footprint "eagle-import:MS621FE")
      (fields (field (name "PARTNO") "MS621FE-FL11E"))
      (libsource (lib "eagle-import") (part "MS621FE"))
    )
    (comp (ref "C601")
      (value "10u/25V")
      (footprint "eagle-import:0805-CAP")
      (fields (field (name "PARTNO") "CL21A106KAYNNNE"))
      (libsource (lib "eagle-import") (part "CAP0805"))
    )
    (comp (ref "C602")
      (value "10n")
      (footprint "eagle-import:0402-CAP")
      (fields (field (name "PARTNO") "CC0402KRX7R7BB103"))
      (libsource (lib "eagle-import") (part "CAP0402"))
    )
    (comp (ref "C603")
      (value "1u")
      (footprint "eagle-import:0603-CAP")
      (fields (field (name "PARTNO") "CC0603ZRY5V7BB105"))
      (libsource (lib "eagle-import") (part "CAP0603"))
    )
    (comp (ref "C604")
      (value "22u/25V")
      (footprint "eagle-import:0805-CAP")
      (fields (field (name "PARTNO") "CL21A226MAQNNNE"))
      (libsource (lib "eagle-import") (part "CAP0805"))
    )
    (comp (ref "C605")
      (value "22u/25V")
      (footprint "eagle-import:0805-CAP")
      (fields (field (name "PARTNO") "CL21A226MAQNNNE"))
      (libsource (lib "eagle-import") (part "CAP0805"))
    )
    (comp (ref "C606")
      (value "0u1")
      (footprint "eagle-import:0402-CAP")
      (fields (field (name "PARTNO") "CC0402ZRY5V7BB104"))
      (libsource (lib "eagle-import") (part "CAP0402"))
    )
    (comp (ref "C607")
      (value "0u1")
      (footprint "eagle-import:0402-CAP")
      (fields (field (name "PARTNO") "CC0402ZRY5V7BB104"))
      (libsource (lib "eagle-import") (part "CAP0402"))
    )
    (comp (ref "C608")
      (value "0u1")
      (footprint "eagle-import:0402-CAP")
      (fields (field (name "PARTNO") "CC0402ZRY5V7BB104"))
      (libsource (lib "eagle-import") (part "CAP0402"))
    )
    (comp (ref "C609")
      (value "0u1")
      (footprint "eagle-import:0402-CAP")
      (fields (field (name "PARTNO") "CC0402ZRY5V7BB104"))
      (libsource (lib "eagle-import") (part "CAP0402"))
    )
    (comp (ref "C610")
      (value "0u1")
      (footprint "eagle-import:0402-CAP")
      (fields (field (name "PARTNO") "CC0402ZRY5V7BB104"))
      (libsource (lib "eagle-import") (part "CAP0402"))
    )
    (comp (ref "C611")
      (value "2u2")
      (footprint "eagle-import:0603-CAP")
      (fields (field (name "PARTNO") "C1608Y5V1C225Z"))
      (libsource (lib "eagle-import") (part "CAP0603"))
    )
    (comp (ref "C612")
      (value "0u1")
      (footprint "eagle-import:0402-CAP")
      (fields (field (name "PARTNO") "CC0402ZRY5V7BB104"))
      (libsource (lib "eagle-import") (part "CAP0402"))
    )
    (comp (ref "C613")
      (value "2u2")
      (footprint "eagle-import:0603-CAP")
      (fields (field (name "PARTNO") "C1608Y5V1C225Z"))
      (libsource (lib "eagle-import") (part "CAP0603"))
    )
    (comp (ref "C614")
      (value "100u")
      (footprint "eagle-import:1206-CAP")
      (fields (field (name "PARTNO") "C3216X5R1A107M160AC"))
      (libsource (lib "eagle-import") (part "CAP1206"))
    )
    (comp (ref "C615")
      (value "0u1")
      (footprint "eagle-import:0402-CAP")
      (fields (field (name "PARTNO") "CC0402ZRY5V7BB104"))
      (libsource (lib "eagle-import") (part "CAP0402"))
    )
    (comp (ref "C616")
      (value "0u1")
      (footprint "eagle-import:0402-CAP")
      (fields (field (name "PARTNO") "CC0402ZRY5V7BB104"))
      (libsource (lib "eagle-import") (part "CAP0402"))
    )
    (comp (ref "C617")
      (value "0u1")
      (footprint "eagle-import:0402-CAP")
      (fields (field (name "PARTNO") "CC0402ZRY5V7BB104"))
      (libsource (lib "eagle-import") (part "CAP0402"))
    )
    (comp (ref "C618")
      (value "100u")
      (footprint "eagle-import:1206-CAP")
      (fields (field (name "PARTNO") "C3216X5R1A107M160AC"))
      (libsource (lib "eagle-import") (part "CAP1206"))
    )
    (comp (ref "D2")
      (value "RB751V40T1G")
      (footprint "eagle-import:SOD323")
      (libsource (lib "eagle-import") (part "DIODE-SCHOTTKY_SOD323"))
    )
    (comp (ref "L603")
      (value "KNH16C104DA5TS")
      (footprint "eagle-import:KYOCERA-KNH16-DA")
      (libsource (lib "eagle-import") (part "KNH16C104DA5TS"))
    )
    (comp (ref "Q601")
      (value "MMBT3906LT1SMD")
      (footprint "eagle-import:SOT23-BEC")
      (fields (field (name "PARTNO") "MMBT 3906 LT1"))
      (libsource (lib "eagle-import") (part "MMBT3906SMDLT1"))
    )
    (comp (ref "R602")
      (value "1M")
      (footprint "eagle-import:0402-RES")
      (fields (field (name "PARTNO") "RC0402FR-071ML"))
      (libsource (lib "eagle-import") (part "RESISTOR0402-RES"))
    )
    (comp (ref "R603")
      (value "10k")
      (footprint "eagle-import:0402-RES")
      (fields (field (name "PARTNO") "RC0402FR-0710KL"))
      (libsource (lib "eagle-import") (part "RESISTOR0402-RES"))
    )
    (comp (ref "R604")
      (value "1M")
      (footprint "eagle-import:0402-RES")
      (fields (field (name "PARTNO") "RC0402FR-071ML"))
      (libsource (lib "eagle-import") (part "RESISTOR0402-RES"))
    )
    (comp (ref "R608")
      (value "1K")
      (footprint "eagle-import:0402-RES")
      (fields (field (name "PARTNO") "RC0402FR-071KL"))
      (libsource (lib "eagle-import") (part "RESISTOR0402-RES"))
    )
    (comp (ref "R609")
      (value "10K/0.1%")
      (footprint "eagle-import:0402-RES")
      (fields (field (name "PARTNO") "ERA-2AEB103X"))
      (libsource (lib "eagle-import") (part "RESISTOR0402-RES"))
    )
    (comp (ref "R610")
      (value "10K/0.1%")
      (footprint "eagle-import:0402-RES")
      (fields (field (name "PARTNO") "ERA-2AEB103X"))
      (libsource (lib "eagle-import") (part "RESISTOR0402-RES"))
    )
    (comp (ref "R611")
      (value "10K")
      (footprint "eagle-import:0402-RES")
      (fields (field (name "PARTNO") "RC0402FR-0710KL"))
      (libsource (lib "eagle-import") (part "RESISTOR0402-RES"))
    )
    (comp (ref "R615")
      (value "10K")
      (footprint "eagle-import:0402-RES")
      (fields (field (name "PARTNO") "RC0402FR-0710KL"))
      (libsource (lib "eagle-import") (part "RESISTOR0402-RES"))
    )
    (comp (ref "R616")
      (value "25K5")
      (footprint "eagle-import:0402-RES")
      (fields (field (name "PARTNO") "RMCF0402FT25K5"))
      (libsource (lib "eagle-import") (part "RESISTOR0402-RES"))
    )
    (comp (ref "R617")
      (value "16K5")
      (footprint "eagle-import:0402-RES")
      (fields (field (name "PARTNO") "RMCF0402FT16K5"))
      (libsource (lib "eagle-import") (part "RESISTOR0402-RES"))
    )
    (comp (ref "R620")
      (value "1k8")
      (footprint "eagle-import:0402-RES")
      (fields (field (name "PARTNO") "RC1005F182CS"))
      (libsource (lib "eagle-import") (part "RESISTOR0402-RES"))
    )
    (comp (ref "R621")
      (value "10R")
      (footprint "eagle-import:0603-RES")
      (fields (field (name "PARTNO") "RC1608J100CS"))
      (libsource (lib "eagle-import") (part "RESISTOR0603-RES"))
    )
    (comp (ref "R635")
      (value "DNP / 10k")
      (footprint "eagle-import:0402-RES")
      (fields (field (name "PARTNO") "RC0402FR-0710KL"))
      (libsource (lib "eagle-import") (part "RESISTOR0402-RES"))
    )
    (comp (ref "S601")
      (value "RESET")
      (footprint "eagle-import:EVQP7J01K")
      (fields (field (name "PARTNO") "EVQP7J01K"))
      (libsource (lib "eagle-import") (part "SWITCH-MOMENTARY-2"))
    )
    (comp (ref "U601")
      (value "BQ24315")
      (footprint "eagle-import:QFN8-DSG")
      (fields (field (name "PARTNO") "BQ24315DSGR"))
      (libsource (lib "eagle-import") (part "BQ24315"))
    )
    (comp (ref "U602")
      (value "BQ24315")
      (footprint "eagle-import:QFN8-DSG")
      (fields (field (name "PARTNO") "BQ24315DSGR"))
      (libsource (lib "eagle-import") (part "BQ24315"))
    )
    (comp (ref "U603")
      (value "MIC5332")
      (footprint "eagle-import:MLF-8-EPAD")
      (fields (field (name "PARTNO") "MIC5332-SSYMT"))
      (libsource (lib "eagle-import") (part "MIC5332"))
    )
    (comp (ref "C801")
      (value "0u1")
      (footprint "eagle-import:0402-CAP")
      (fields (field (name "PARTNO") "CC0402ZRY5V7BB104"))
      (libsource (lib "eagle-import") (part "CAP0402"))
    )
    (comp (ref "C802")
      (value "0u1")
      (footprint "eagle-import:0402-CAP")
      (fields (field (name "PARTNO") "CC0402ZRY5V7BB104"))
      (libsource (lib "eagle-import") (part "CAP0402"))
    )
    (comp (ref "C803")
      (value "0u1")
      (footprint "eagle-import:0402-CAP")
      (fields (field (name "PARTNO") "CC0402ZRY5V7BB104"))
      (libsource (lib "eagle-import") (part "CAP0402"))
    )
    (comp (ref "C804")
      (value "0u1")
      (footprint "eagle-import:0402-CAP")
      (fields (field (name "PARTNO") "CC0402ZRY5V7BB104"))
      (libsource (lib "eagle-import") (part "CAP0402"))
    )
    (comp (ref "C805")
      (value "8p")
      (footprint "eagle-import:0402-CAP")
      (fields (field (name "PARTNO") "C1005C0G1H080C"))
      (libsource (lib "eagle-import") (part "CAP0402"))
    )
    (comp (ref "C806")
      (value "8p")
      (footprint "eagle-import:0402-CAP")
      (fields (field (name "PARTNO") "C1005C0G1H080C"))
      (libsource (lib "eagle-import") (part "CAP0402"))
    )
    (comp (ref "D801")
      (value "PESD0402-140")
      (footprint "eagle-import:0402-TVS")
      (libsource (lib "eagle-import") (part "DIODE-TVS"))
    )
    (comp (ref "J801")
      (value "JST-ZH-3")
      (footprint "eagle-import:JST-ZH-SMT-VERTICAL")
      (fields (field (name "PARTNO") "B3B-ZR-SM4-TF (LF)(SN)(P)"))
      (libsource (lib "eagle-import") (part "JST-ZH-3"))
    )
    (comp (ref "JX801")
      (value "HEADER-3X1BOARDEDGE-SHORT")
      (footprint "eagle-import:HEADER_3X01_SMD_H_BOARD_EDGE_SHORT")
      (libsource (lib "eagle-import") (part "HEADER-3X1BOARDEDGE-SHORT"))
    )
    (comp (ref "JX802")
      (value "ARM_MINI_JTAG-SMT")
      (footprint "eagle-import:FTSH-105-01-XXX-DV-K")
      (fields (field (name "BOM") "EXCLUDE") (field (name "PARTNO") "M50-3900542"))
      (libsource (lib "eagle-import") (part "ARM_MINI_JTAG-SMT"))
    )
    (comp (ref "R801")
      (value "10K")
      (footprint "eagle-import:0402-RES")
      (fields (field (name "PARTNO") "RC0402FR-0710KL"))
      (libsource (lib "eagle-import") (part "RESISTOR0402-RES"))
    )
    (comp (ref "R802")
      (value "10K")
      (footprint "eagle-import:0402-RES")
      (fields (field (name "PARTNO") "RC0402FR-0710KL"))
      (libsource (lib "eagle-import") (part "RESISTOR0402-RES"))
    )
    (comp (ref "R803")
      (value "220R")
      (footprint "eagle-import:0402-RES")
      (fields (field (name "PARTNO") "RC0402FR-07220RL"))
      (libsource (lib "eagle-import") (part "RESISTOR0402-RES"))
    )
    (comp (ref "R804")
      (value "220R")
      (footprint "eagle-import:0402-RES")
      (fields (field (name "PARTNO") "RC0402FR-07220RL"))
      (libsource (lib "eagle-import") (part "RESISTOR0402-RES"))
    )
    (comp (ref "S801")
      (value "RESET")
      (footprint "eagle-import:EVQP7J01K")
      (fields (field (name "PARTNO") "EVQP7J01K"))
      (libsource (lib "eagle-import") (part "SWITCH-MOMENTARY-2"))
    )
    (comp (ref "U801")
      (value "STM32F10XCXT6")
      (footprint "eagle-import:TQFP48")
      (fields (field (name "PARTNO") "STM32F100C8T6B"))
      (libsource (lib "eagle-import") (part "STM32F10XCXT6"))
    )
    (comp (ref "X801")
      (value "3.2x2.5 mm / 24 MHz / 15 ppm")
      (footprint "eagle-import:OSCILLATOR-3.2X2.5")
      (fields (field (name "PARTNO") "NX3225SA-24.000000MHZ"))
      (libsource (lib "eagle-import") (part "OSCILLATOR-3.2X2.5"))
    )
    (comp (ref "C701")
      (value "0u1")
      (footprint "eagle-import:0402-CAP")
      (fields (field (name "PARTNO") "CC0402ZRY5V7BB104"))
      (libsource (lib "eagle-import") (part "CAP0402"))
    )
    (comp (ref "C702")
      (value "1u0")
      (footprint "eagle-import:0603-CAP")
      (fields (field (name "PARTNO") "CC0603ZRY5V7BB105"))
      (libsource (lib "eagle-import") (part "CAP0603"))
    )
    (comp (ref "C703")
      (value "5n6")
      (footprint "eagle-import:0402-CAP")
      (fields (field (name "PARTNO") "CC0402KRX7R7BB562"))
      (libsource (lib "eagle-import") (part "CAP0402"))
    )
    (comp (ref "C704")
      (value "0u47")
      (footprint "eagle-import:0402-CAP")
      (fields (field (name "PARTNO") "C1005X5R1C474K050BC"))
      (libsource (lib "eagle-import") (part "CAP0402"))
    )
    (comp (ref "D701")
      (value "PESD0402-140")
      (footprint "eagle-import:0402-TVS")
      (libsource (lib "eagle-import") (part "DIODE-TVS"))
    )
    (comp (ref "J701")
      (value "DF13C-2P-1.25V")
      (footprint "eagle-import:DF13C-2P-1.25V")
      (fields (field (name "PARTNO") "DF13C-2P-1.25V(20)"))
      (libsource (lib "eagle-import") (part "DF13-2P-1.25V"))
    )
    (comp (ref "J702")
      (value "DF13C-3P-1.25V")
      (footprint "eagle-import:DF13C-3P-1.25V")
      (fields (field (name "PARTNO") "DF13C-3P-1.25V(20)"))
      (libsource (lib "eagle-import") (part "DF13-3P-1.25V"))
    )
    (comp (ref "L701")
      (value "47uH")
      (footprint "eagle-import:0805-IND")
      (fields (field (name "PARTNO") "MLZ2012M470W"))
      (libsource (lib "eagle-import") (part "INDUCTOR0805"))
    )
    (comp (ref "LED701")
      (value "AMBER")
      (footprint "eagle-import:0603-LED")
      (fields (field (name "PARTNO") "APTD1608SECK"))
      (libsource (lib "eagle-import") (part "LED0603"))
    )
    (comp (ref "LED702")
      (value "GREEN")
      (footprint "eagle-import:0603-LED")
      (fields (field (name "PARTNO") "APTD1608CGCK"))
      (libsource (lib "eagle-import") (part "LED0603"))
    )
    (comp (ref "LED703")
      (value "AMBER")
      (footprint "eagle-import:0603-LED")
      (fields (field (name "PARTNO") "APTD1608SECK"))
      (libsource (lib "eagle-import") (part "LED0603"))
    )
    (comp (ref "LED704")
      (value "GREEN")
      (footprint "eagle-import:0603-LED")
      (fields (field (name "PARTNO") "APTD1608CGCK"))
      (libsource (lib "eagle-import") (part "LED0603"))
    )
    (comp (ref "LED705")
      (value "BLUE")
      (footprint "eagle-import:0603-LED")
      (fields (field (name "PARTNO") "APTD1608QBC/D"))
      (libsource (lib "eagle-import") (part "LED0603"))
    )
    (comp (ref "R3")
      (value "220R")
      (footprint "eagle-import:0402-RES")
      (fields (field (name "PARTNO") "RC0402FR-07220RL"))
      (libsource (lib "eagle-import") (part "RESISTOR0402-RES"))
    )
    (comp (ref "R4")
      (value "220R")
      (footprint "eagle-import:0402-RES")
      (fields (field (name "PARTNO") "RC0402FR-07220RL"))
      (libsource (lib "eagle-import") (part "RESISTOR0402-RES"))
    )
    (comp (ref "R701")
      (value "9K09")
      (footprint "eagle-import:0402-RES")
      (fields (field (name "PARTNO") "RMCF0402FT9K09"))
      (libsource (lib "eagle-import") (part "RESISTOR0402-RES"))
    )
    (comp (ref "R702")
      (value "10K")
      (footprint "eagle-import:0402-RES")
      (fields (field (name "PARTNO") "RC0402FR-0710KL"))
      (libsource (lib "eagle-import") (part "RESISTOR0402-RES"))
    )
    (comp (ref "R703")
      (value "100K")
      (footprint "eagle-import:0402-RES")
      (fields (field (name "PARTNO") "RC0402FR-07100KL"))
      (libsource (lib "eagle-import") (part "RESISTOR0402-RES"))
    )
    (comp (ref "R704")
      (value "10K")
      (footprint "eagle-import:0402-RES")
      (fields (field (name "PARTNO") "RC0402FR-0710KL"))
      (libsource (lib "eagle-import") (part "RESISTOR0402-RES"))
    )
    (comp (ref "R705")
      (value "453K")
      (footprint "eagle-import:0402-RES")
      (fields (field (name "PARTNO") "RMCF0402FT453K"))
      (libsource (lib "eagle-import") (part "RESISTOR0402-RES"))
    )
    (comp (ref "R706")
      (value "16K5")
      (footprint "eagle-import:0402-RES")
      (fields (field (name "PARTNO") "RMCF0402FT16K5"))
      (libsource (lib "eagle-import") (part "RESISTOR0402-RES"))
    )
    (comp (ref "R707")
      (value "220R")
      (footprint "eagle-import:0402-RES")
      (fields (field (name "PARTNO") "RC0402FR-07220RL"))
      (libsource (lib "eagle-import") (part "RESISTOR0402-RES"))
    )
    (comp (ref "R708")
      (value "220R")
      (footprint "eagle-import:0402-RES")
      (fields (field (name "PARTNO") "RC0402FR-07220RL"))
      (libsource (lib "eagle-import") (part "RESISTOR0402-RES"))
    )
    (comp (ref "R709")
      (value "220R")
      (footprint "eagle-import:0402-RES")
      (fields (field (name "PARTNO") "RC0402FR-07220RL"))
      (libsource (lib "eagle-import") (part "RESISTOR0402-RES"))
    )
    (comp (ref "R710")
      (value "68R")
      (footprint "eagle-import:0402-RES")
      (fields (field (name "PARTNO") "ERJ-2GEJ680X"))
      (libsource (lib "eagle-import") (part "RESISTOR0402-RES"))
    )
    (comp (ref "R711")
      (value "220R")
      (footprint "eagle-import:0402-RES")
      (fields (field (name "PARTNO") "RC0402FR-07220RL"))
      (libsource (lib "eagle-import") (part "RESISTOR0402-RES"))
    )
    (comp (ref "R712")
      (value "220R")
      (footprint "eagle-import:0402-RES")
      (fields (field (name "PARTNO") "RC0402FR-07220RL"))
      (libsource (lib "eagle-import") (part "RESISTOR0402-RES"))
    )
    (comp (ref "R713")
      (value "1K5")
      (footprint "eagle-import:0402-RES")
      (fields (field (name "PARTNO") "RC0402FR-071K5L"))
      (libsource (lib "eagle-import") (part "RESISTOR0402-RES"))
    )
    (comp (ref "U701")
      (value "TCA62724FMG")
      (footprint "eagle-import:SON10")
      (libsource (lib "eagle-import") (part "TCA62724FMG"))
    )
    (comp (ref "U702")
      (value "LT3469")
      (footprint "eagle-import:SOT23-8")
      (fields (field (name "PARTNO") "LT3469ETS8"))
      (libsource (lib "eagle-import") (part "LT3469"))
    )
    (comp (ref "U703")
      (value "LRTB GFTG-T7AW-1+V7A7-29+R5T9-49-L")
      (footprint "eagle-import:6-PLCC")
      (fields (field (name "PARTNO") "LRTB GFTG-T7AW-1+V7A7-29+R5T9-49-L"))
      (libsource (lib "eagle-import") (part "RGB-LED6-PLCC"))
    )
    (comp (ref "C901")
      (value "0u1")
      (footprint "eagle-import:0402-CAP")
      (fields (field (name "PARTNO") "CC0402ZRY5V7BB104"))
      (libsource (lib "eagle-import") (part "CAP0402"))
    )
    (comp (ref "C902")
      (value "0u1")
      (footprint "eagle-import:0402-CAP")
      (fields (field (name "PARTNO") "CC0402ZRY5V7BB104"))
      (libsource (lib "eagle-import") (part "CAP0402"))
    )
    (comp (ref "C903")
      (value "0u1")
      (footprint "eagle-import:0402-CAP")
      (fields (field (name "PARTNO") "CC0402ZRY5V7BB104"))
      (libsource (lib "eagle-import") (part "CAP0402"))
    )
    (comp (ref "D1")
      (value "MSS1P4-M3")
      (footprint "eagle-import:MICROSMP")
      (fields (field (name "PARTNO") "MSS1P4-M3/89A"))
      (libsource (lib "eagle-import") (part "DIODE-SCHOTTKY_MSMP"))
    )
    (comp (ref "D901")
      (value "PESD0402-140")
      (footprint "eagle-import:0402-TVS")
      (libsource (lib "eagle-import") (part "DIODE-TVS"))
    )
    (comp (ref "D902")
      (value "PESD0402-140")
      (footprint "eagle-import:0402-TVS")
      (libsource (lib "eagle-import") (part "DIODE-TVS"))
    )
    (comp (ref "D903")
      (value "PESD0402-140")
      (footprint "eagle-import:0402-TVS")
      (libsource (lib "eagle-import") (part "DIODE-TVS"))
    )
    (comp (ref "J901")
      (value "HEADER-3X163X16RA")
      (footprint "eagle-import:3X16RA")
      (fields (field (name "BOM") "EXCLUDE"))
      (libsource (lib "eagle-import") (part "HEADER-3X163X16RA"))
    )
    (comp (ref "L901")
      (value "KNH16C104DA5TS")
      (footprint "eagle-import:KYOCERA-KNH16-DA")
      (libsource (lib "eagle-import") (part "KNH16C104DA5TS"))
    )
    (comp (ref "R901")
      (value "10K")
      (footprint "eagle-import:0402-RES")
      (fields (field (name "PARTNO") "RC0402FR-0710KL"))
      (libsource (lib "eagle-import") (part "RESISTOR0402-RES"))
    )
    (comp (ref "R902")
      (value "220R")
      (footprint "eagle-import:0402-RES")
      (fields (field (name "PARTNO") "RC0402FR-07220RL"))
      (libsource (lib "eagle-import") (part "RESISTOR0402-RES"))
    )
    (comp (ref "R903")
      (value "220R")
      (footprint "eagle-import:0402-RES")
      (fields (field (name "PARTNO") "RC0402FR-07220RL"))
      (libsource (lib "eagle-import") (part "RESISTOR0402-RES"))
    )
    (comp (ref "R904")
      (value "220R")
      (footprint "eagle-import:0402-RES")
      (fields (field (name "PARTNO") "RC0402FR-07220RL"))
      (libsource (lib "eagle-import") (part "RESISTOR0402-RES"))
    )
    (comp (ref "R905")
      (value "220R")
      (footprint "eagle-import:0402-RES")
      (fields (field (name "PARTNO") "RC0402FR-07220RL"))
      (libsource (lib "eagle-import") (part "RESISTOR0402-RES"))
    )
    (comp (ref "R906")
      (value "220R")
      (footprint "eagle-import:0402-RES")
      (fields (field (name "PARTNO") "RC0402FR-07220RL"))
      (libsource (lib "eagle-import") (part "RESISTOR0402-RES"))
    )
    (comp (ref "R907")
      (value "220R")
      (footprint "eagle-import:0402-RES")
      (fields (field (name "PARTNO") "RC0402FR-07220RL"))
      (libsource (lib "eagle-import") (part "RESISTOR0402-RES"))
    )
    (comp (ref "R908")
      (value "220R")
      (footprint "eagle-import:0402-RES")
      (fields (field (name "PARTNO") "RC0402FR-07220RL"))
      (libsource (lib "eagle-import") (part "RESISTOR0402-RES"))
    )
    (comp (ref "R909")
      (value "220R")
      (footprint "eagle-import:0402-RES")
      (fields (field (name "PARTNO") "RC0402FR-07220RL"))
      (libsource (lib "eagle-import") (part "RESISTOR0402-RES"))
    )
    (comp (ref "R910")
      (value "220R")
      (footprint "eagle-import:0402-RES")
      (fields (field (name "PARTNO") "RC0402FR-07220RL"))
      (libsource (lib "eagle-import") (part "RESISTOR0402-RES"))
    )
    (comp (ref "R911")
      (value "220R")
      (footprint "eagle-import:0402-RES")
      (fields (field (name "PARTNO") "RC0402FR-07220RL"))
      (libsource (lib "eagle-import") (part "RESISTOR0402-RES"))
    )
    (comp (ref "R912")
      (value "220R")
      (footprint "eagle-import:0402-RES")
      (fields (field (name "PARTNO") "RC0402FR-07220RL"))
      (libsource (lib "eagle-import") (part "RESISTOR0402-RES"))
    )
    (comp (ref "R913")
      (value "220R")
      (footprint "eagle-import:0402-RES")
      (fields (field (name "PARTNO") "RC0402FR-07220RL"))
      (libsource (lib "eagle-import") (part "RESISTOR0402-RES"))
    )
    (comp (ref "R914")
      (value "220R")
      (footprint "eagle-import:0402-RES")
      (fields (field (name "PARTNO") "RC0402FR-07220RL"))
      (libsource (lib "eagle-import") (part "RESISTOR0402-RES"))
    )
    (comp (ref "R915")
      (value "220R")
      (footprint "eagle-import:0402-RES")
      (fields (field (name "PARTNO") "RC0402FR-07220RL"))
      (libsource (lib "eagle-import") (part "RESISTOR0402-RES"))
    )
    (comp (ref "R916")
      (value "220R")
      (footprint "eagle-import:0402-RES")
      (fields (field (name "PARTNO") "RC0402FR-07220RL"))
      (libsource (lib "eagle-import") (part "RESISTOR0402-RES"))
    )
    (comp (ref "R917")
      (value "220R")
      (footprint "eagle-import:0402-RES")
      (fields (field (name "PARTNO") "RC0402FR-07220RL"))
      (libsource (lib "eagle-import") (part "RESISTOR0402-RES"))
    )
    (comp (ref "R918")
      (value "10K/0.1%")
      (footprint "eagle-import:0402-RES")
      (fields (field (name "PARTNO") "ERA-2AEB103X"))
      (libsource (lib "eagle-import") (part "RESISTOR0402-RES"))
    )
    (comp (ref "R919")
      (value "10K/0.1%")
      (footprint "eagle-import:0402-RES")
      (fields (field (name "PARTNO") "ERA-2AEB103X"))
      (libsource (lib "eagle-import") (part "RESISTOR0402-RES"))
    )
    (comp (ref "R922")
      (value "10K/0.1%")
      (footprint "eagle-import:0402-RES")
      (fields (field (name "PARTNO") "ERA-2AEB103X"))
      (libsource (lib "eagle-import") (part "RESISTOR0402-RES"))
    )
    (comp (ref "U901")
      (value "TXS0108QFN20")
      (footprint "eagle-import:QFN20-RGY")
      (fields (field (name "PARTNO") "TXS0108ERGYR"))
      (libsource (lib "eagle-import") (part "TXS0108QFN20"))
    )
    (comp (ref "U902")
      (value "TXS0108QFN20")
      (footprint "eagle-import:QFN20-RGY")
      (fields (field (name "PARTNO") "TXS0108ERGYR"))
      (libsource (lib "eagle-import") (part "TXS0108QFN20"))
    )
    (comp (ref "U903")
      (value "74LVC2G240")
      (footprint "eagle-import:TSSOP8_SOT505-2")
      (fields (field (name "PARTNO") "74LVC2G240DP,125"))
      (libsource (lib "eagle-import") (part "74LVC2G240-TSSOP-8"))
    )
    (comp (ref "C1001")
      (value "10u/25V")
      (footprint "eagle-import:0805-CAP")
      (fields (field (name "PARTNO") "CL21A106KAYNNNE"))
      (libsource (lib "eagle-import") (part "CAP0805"))
    )
    (comp (ref "C1002")
      (value "10n")
      (footprint "eagle-import:0402-CAP")
      (fields (field (name "PARTNO") "CC0402KRX7R7BB103"))
      (libsource (lib "eagle-import") (part "CAP0402"))
    )
    (comp (ref "C1003")
      (value "1u0")
      (footprint "eagle-import:0603-CAP")
      (fields (field (name "PARTNO") "CC0603ZRY5V7BB105"))
      (libsource (lib "eagle-import") (part "CAP0603"))
    )
    (comp (ref "C1004")
      (value "10u")
      (footprint "eagle-import:0603-CAP")
      (fields (field (name "PARTNO") "CC0603ZRY5V7BB105"))
      (libsource (lib "eagle-import") (part "CAP0603"))
    )
    (comp (ref "C1005")
      (value "0u1F")
      (footprint "eagle-import:0402-CAP")
      (fields (field (name "PARTNO") "CC0402ZRY5V7BB104"))
      (libsource (lib "eagle-import") (part "CAP0402"))
    )
    (comp (ref "C1008")
      (value "2u2")
      (footprint "eagle-import:0402-CAP")
      (fields (field (name "PARTNO") "CC0603ZRY5V7BB105"))
      (libsource (lib "eagle-import") (part "CAP0402"))
    )
    (comp (ref "D1001")
      (value "PMEG2005CT")
      (footprint "eagle-import:SOT23-3")
      (libsource (lib "eagle-import") (part "PMEG2005CT"))
    )
    (comp (ref "F1001")
      (value "0ZCA0035FF2G")
      (footprint "eagle-import:PTC-1206")
      (libsource (lib "eagle-import") (part "PTCSMD"))
    )
    (comp (ref "R1001")
      (value "100K")
      (footprint "eagle-import:0402-RES")
      (fields (field (name "PARTNO") "RC0402FR-07100KL"))
      (libsource (lib "eagle-import") (part "RESISTOR0402-RES"))
    )
    (comp (ref "R1002")
      (value "10K")
      (footprint "eagle-import:0402-RES")
      (fields (field (name "PARTNO") "RC0402FR-0710KL"))
      (libsource (lib "eagle-import") (part "RESISTOR0402-RES"))
    )
    (comp (ref "U1001")
      (value "BQ24313")
      (footprint "eagle-import:QFN8-DSG")
      (fields (field (name "PARTNO") "BQ24313DSGT"))
      (libsource (lib "eagle-import") (part "BQ24313"))
    )
    (comp (ref "U1002")
      (value "MIC5332")
      (footprint "eagle-import:MLF-8-EPAD")
      (fields (field (name "PARTNO") "MIC5332-SSYMT"))
      (libsource (lib "eagle-import") (part "MIC5332"))
    )
    (comp (ref "J301")
      (value "47346-0001")
      (footprint "eagle-import:MOLEX-47346-0001")
      (libsource (lib "eagle-import") (part "MOLEX-47346-0001"))
    )
    (comp (ref "J302")
      (value "DF13C-4P-1.25V")
      (footprint "eagle-import:DF13C-4P-1.25V")
      (fields (field (name "PARTNO") "DF13C-4P-1.25V(20)"))
      (libsource (lib "eagle-import") (part "DF13-4P-1.25V"))
    )
    (comp (ref "JX301")
      (value "ARM_MINI_JTAG-SMT")
      (footprint "eagle-import:FTSH-105-01-XXX-DV-K")
      (fields (field (name "BOM") "EXCLUDE") (field (name "PARTNO") "M50-3900542"))
      (libsource (lib "eagle-import") (part "ARM_MINI_JTAG-SMT"))
    )
    (comp (ref "R301")
      (value "100K")
      (footprint "eagle-import:0402-RES")
      (fields (field (name "PARTNO") "RC0402FR-07100KL"))
      (libsource (lib "eagle-import") (part "RESISTOR0402-RES"))
    )
    (comp (ref "R302")
      (value "100K")
      (footprint "eagle-import:0402-RES")
      (fields (field (name "PARTNO") "RC0402FR-07100KL"))
      (libsource (lib "eagle-import") (part "RESISTOR0402-RES"))
    )
    (comp (ref "R303")
      (value "100K")
      (footprint "eagle-import:0402-RES")
      (fields (field (name "PARTNO") "RC0402FR-07100KL"))
      (libsource (lib "eagle-import") (part "RESISTOR0402-RES"))
    )
    (comp (ref "R304")
      (value "100K")
      (footprint "eagle-import:0402-RES")
      (fields (field (name "PARTNO") "RC0402FR-07100KL"))
      (libsource (lib "eagle-import") (part "RESISTOR0402-RES"))
    )
    (comp (ref "R305")
      (value "100K")
      (footprint "eagle-import:0402-RES")
      (fields (field (name "PARTNO") "RC0402FR-07100KL"))
      (libsource (lib "eagle-import") (part "RESISTOR0402-RES"))
    )
    (comp (ref "R306")
      (value "1K5")
      (footprint "eagle-import:0402-RES")
      (fields (field (name "PARTNO") "RC0402FR-071K5L"))
      (libsource (lib "eagle-import") (part "RESISTOR0402-RES"))
    )
    (comp (ref "R307")
      (value "1K5")
      (footprint "eagle-import:0402-RES")
      (fields (field (name "PARTNO") "RC0402FR-071K5L"))
      (libsource (lib "eagle-import") (part "RESISTOR0402-RES"))
    )
    (comp (ref "U301")
      (value "2908-05WB-MG")
      (footprint "eagle-import:MICROSD")
      (libsource (lib "eagle-import") (part "MICROSDSDI"))
    )
    (comp (ref "U302")
      (value "NUF2042XV6")
      (footprint "eagle-import:SOT563-6")
      (fields (field (name "PARTNO") "NUF2042XV6T1G"))
      (libsource (lib "eagle-import") (part "NUF2042XV6"))
    )
  )
  (nets
    (net (code "1") (name "ACCEL_DRDY") (class "Default")
      (node (ref "U101") (pin "90") (pinfunction "PB4_90") (pintype "bidirectional"))
      (node (ref "U504") (pin "11") (pinfunction "INT1_11") (pintype "bidirectional"))
      (node (ref "X503") (pin "3") (pinfunction "S_3") (pintype "passive"))
    )
    (net (code "2") (name "ALARM") (class "Default")
      (node (ref "R701") (pin "P$2") (pinfunction "2_P$2") (pintype "passive"))
      (node (ref "U101") (pin "77") (pinfunction "PA15_77") (pintype "bidirectional"))
    )
    (net (code "3") (name "BATT_CURRENT_SENS") (class "Default")
      (node (ref "R1101") (pin "P$1") (pinfunction "1_P$1") (pintype "passive"))
      (node (ref "U101") (pin "26") (pinfunction "PA3_26") (pintype "bidirectional"))
    )
    (net (code "4") (name "BATT_VOLTAGE_SENS") (class "Default")
      (node (ref "R1102") (pin "P$1") (pinfunction "1_P$1") (pintype "passive"))
      (node (ref "U101") (pin "25") (pinfunction "PA2_25") (pintype "bidirectional"))
    )
    (net (code "5") (name "CAN1_RX") (class "Default")
      (node (ref "U101") (pin "81") (pinfunction "PD0_81") (pintype "bidirectional"))
      (node (ref "U401") (pin "4") (pinfunction "DOUT_4") (pintype "output"))
    )
    (net (code "6") (name "CAN1_TX") (class "Default")
      (node (ref "U101") (pin "82") (pinfunction "PD1_82") (pintype "bidirectional"))
      (node (ref "U401") (pin "1") (pinfunction "DIN_1") (pintype "input"))
    )
    (net (code "7") (name "CAN2_RX") (class "Default")
      (node (ref "R216") (pin "P$1") (pinfunction "1_P$1") (pintype "passive"))
      (node (ref "U101") (pin "51") (pinfunction "PB12_51") (pintype "bidirectional"))
    )
    (net (code "8") (name "CAN2_TX") (class "Default")
      (node (ref "R215") (pin "P$1") (pinfunction "1_P$1") (pintype "passive"))
      (node (ref "U101") (pin "92") (pinfunction "PB6_92") (pintype "bidirectional"))
    )
    (net (code "9") (name "CAN_H") (class "Default")
      (node (ref "CAN_H1116") (pin "P$1") (pinfunction "P$1_P$1") (pintype "passive"))
      (node (ref "J405") (pin "2") (pinfunction "2_2") (pintype "passive"))
      (node (ref "R409") (pin "P$1") (pinfunction "1_P$1") (pintype "passive"))
      (node (ref "U401") (pin "7") (pinfunction "CANH_7") (pintype "bidirectional"))
    )
    (net (code "10") (name "CAN_L") (class "Default")
      (node (ref "CAN_L1116") (pin "P$1") (pinfunction "P$1_P$1") (pintype "passive"))
      (node (ref "J405") (pin "3") (pinfunction "3_3") (pintype "passive"))
      (node (ref "R409") (pin "P$2") (pinfunction "2_P$2") (pintype "passive"))
      (node (ref "U401") (pin "6") (pinfunction "CANL_6") (pintype "bidirectional"))
    )
    (net (code "11") (name "FMU-BOOT0") (class "Default")
      (node (ref "FMU-BOOT1101") (pin "P$1") (pinfunction "P$1_P$1") (pintype "passive"))
      (node (ref "R611") (pin "P$2") (pinfunction "2_P$2") (pintype "passive"))
      (node (ref "U101") (pin "94") (pinfunction "BOOT0_94") (pintype "input"))
    )
    (net (code "12") (name "FMU-CH1") (class "Default")
      (node (ref "U101") (pin "45") (pinfunction "PE14_45") (pintype "bidirectional"))
      (node (ref "U901") (pin "7") (pinfunction "A6_7") (pintype "bidirectional"))
    )
    (net (code "13") (name "FMU-CH2") (class "Default")
      (node (ref "U101") (pin "44") (pinfunction "PE13_44") (pintype "bidirectional"))
      (node (ref "U901") (pin "6") (pinfunction "A5_6") (pintype "bidirectional"))
    )
    (net (code "14") (name "FMU-CH3") (class "Default")
      (node (ref "U101") (pin "42") (pinfunction "PE11_42") (pintype "bidirectional"))
      (node (ref "U901") (pin "5") (pinfunction "A4_5") (pintype "bidirectional"))
    )
    (net (code "15") (name "FMU-CH4") (class "Default")
      (node (ref "U101") (pin "40") (pinfunction "PE9_40") (pintype "bidirectional"))
      (node (ref "U901") (pin "4") (pinfunction "A3_4") (pintype "bidirectional"))
    )
    (net (code "16") (name "FMU-CH5") (class "Default")
      (node (ref "U101") (pin "60") (pinfunction "PD13_60") (pintype "bidirectional"))
      (node (ref "U901") (pin "3") (pinfunction "A2_3") (pintype "bidirectional"))
    )
    (net (code "17") (name "FMU-CH6") (class "Default")
      (node (ref "U101") (pin "61") (pinfunction "PD14_61") (pintype "bidirectional"))
      (node (ref "U901") (pin "1") (pinfunction "A1_1") (pintype "bidirectional"))
    )
    (net (code "18") (name "FMU-I2C1_SCL") (class "Default")
      (node (ref "R401") (pin "P$1") (pinfunction "1_P$1") (pintype "passive"))
      (node (ref "R404") (pin "P$1") (pinfunction "1_P$1") (pintype "passive"))
      (node (ref "U101") (pin "95") (pinfunction "PB8_95") (pintype "bidirectional"))
    )
    (net (code "19") (name "FMU-I2C1_SDA") (class "Default")
      (node (ref "R402") (pin "P$1") (pinfunction "1_P$1") (pintype "passive"))
      (node (ref "R405") (pin "P$1") (pinfunction "1_P$1") (pintype "passive"))
      (node (ref "U101") (pin "96") (pinfunction "PB9_96") (pintype "bidirectional"))
    )
    (net (code "20") (name "FMU-I2C2_SCL") (class "Default")
      (node (ref "R306") (pin "P$1") (pinfunction "1_P$1") (pintype "passive"))
      (node (ref "U101") (pin "47") (pinfunction "PB10_47") (pintype "bidirectional"))
      (node (ref "U701") (pin "3") (pinfunction "SCL_3") (pintype "bidirectional"))
    )
    (net (code "21") (name "FMU-I2C2_SDA") (class "Default")
      (node (ref "R307") (pin "P$1") (pinfunction "1_P$1") (pintype "passive"))
      (node (ref "U101") (pin "48") (pinfunction "PB11_48") (pintype "bidirectional"))
      (node (ref "U701") (pin "2") (pinfunction "SDA_2") (pintype "bidirectional"))
    )
    (net (code "22") (name "FMU-SWCLK") (class "Default")
      (node (ref "JX301") (pin "4") (pinfunction "S_4") (pintype "passive"))
      (node (ref "U101") (pin "76") (pinfunction "PA14_76") (pintype "bidirectional"))
    )
    (net (code "23") (name "FMU-SWDIO") (class "Default")
      (node (ref "JX301") (pin "2") (pinfunction "S_2") (pintype "passive"))
      (node (ref "U101") (pin "72") (pinfunction "PA13_72") (pintype "bidirectional"))
    )
    (net (code "24") (name "FMU-SWO") (class "Default")
      (node (ref "JX301") (pin "6") (pinfunction "S_6") (pintype "passive"))
      (node (ref "U101") (pin "89") (pinfunction "PB3_89") (pintype "bidirectional"))
    )
    (net (code "25") (name "FMU-UART4_RX") (class "Default")
      (node (ref "U101") (pin "24") (pinfunction "PA1_24") (pintype "bidirectional"))
      (node (ref "U202") (pin "8") (pinfunction "A7_8") (pintype "bidirectional"))
    )
    (net (code "26") (name "FMU-UART4_TX") (class "Default")
      (node (ref "U101") (pin "23") (pinfunction "PA0_23") (pintype "bidirectional"))
      (node (ref "U202") (pin "9") (pinfunction "A8_9") (pintype "bidirectional"))
    )
    (net (code "27") (name "FMU-UART7_RX") (class "Default")
      (node (ref "U101") (pin "38") (pinfunction "PE7_38") (pintype "bidirectional"))
      (node (ref "U202") (pin "4") (pinfunction "A3_4") (pintype "bidirectional"))
    )
    (net (code "28") (name "FMU-UART7_TX") (class "Default")
      (node (ref "U101") (pin "39") (pinfunction "PE8_39") (pintype "bidirectional"))
      (node (ref "U202") (pin "5") (pinfunction "A4_5") (pintype "bidirectional"))
    )
    (net (code "29") (name "FMU-UART8_RX") (class "Default")
      (node (ref "U101") (pin "97") (pinfunction "PE0_97") (pintype "bidirectional"))
      (node (ref "U202") (pin "6") (pinfunction "A5_6") (pintype "bidirectional"))
    )
    (net (code "30") (name "FMU-UART8_TX") (class "Default")
      (node (ref "U101") (pin "98") (pinfunction "PE1_98") (pintype "bidirectional"))
      (node (ref "U202") (pin "7") (pinfunction "A6_7") (pintype "bidirectional"))
    )
    (net (code "31") (name "FMU-USART2_CTS") (class "Default")
      (node (ref "U101") (pin "84") (pinfunction "PD3_84") (pintype "bidirectional"))
      (node (ref "U201") (pin "9") (pinfunction "A8_9") (pintype "bidirectional"))
    )
    (net (code "32") (name "FMU-USART2_RTS") (class "Default")
      (node (ref "U101") (pin "85") (pinfunction "PD4_85") (pintype "bidirectional"))
      (node (ref "U201") (pin "8") (pinfunction "A7_8") (pintype "bidirectional"))
    )
    (net (code "33") (name "FMU-USART2_RX") (class "Default")
      (node (ref "U101") (pin "87") (pinfunction "PD6_87") (pintype "bidirectional"))
      (node (ref "U201") (pin "6") (pinfunction "A5_6") (pintype "bidirectional"))
    )
    (net (code "34") (name "FMU-USART2_TX") (class "Default")
      (node (ref "U101") (pin "86") (pinfunction "PD5_86") (pintype "bidirectional"))
      (node (ref "U201") (pin "7") (pinfunction "A6_7") (pintype "bidirectional"))
    )
    (net (code "35") (name "FMU-USART3_CTS") (class "Default")
      (node (ref "U101") (pin "58") (pinfunction "PD11_58") (pintype "bidirectional"))
      (node (ref "U201") (pin "3") (pinfunction "A2_3") (pintype "bidirectional"))
    )
    (net (code "36") (name "FMU-USART3_RTS") (class "Default")
      (node (ref "U101") (pin "59") (pinfunction "PD12_59") (pintype "bidirectional"))
      (node (ref "U201") (pin "1") (pinfunction "A1_1") (pintype "bidirectional"))
    )
    (net (code "37") (name "FMU-USART3_RX") (class "Default")
      (node (ref "U101") (pin "56") (pinfunction "PD9_56") (pintype "bidirectional"))
      (node (ref "U201") (pin "4") (pinfunction "A3_4") (pintype "bidirectional"))
    )
    (net (code "38") (name "FMU-USART3_TX") (class "Default")
      (node (ref "U101") (pin "55") (pinfunction "PD8_55") (pintype "bidirectional"))
      (node (ref "U201") (pin "5") (pinfunction "A4_5") (pintype "bidirectional"))
    )
    (net (code "39") (name "FMU-VDD_3V3") (class "Default")
      (node (ref "C101") (pin "P$1") (pinfunction "1_P$1") (pintype "passive"))
      (node (ref "C201") (pin "P$1") (pinfunction "1_P$1") (pintype "passive"))
      (node (ref "C202") (pin "P$1") (pinfunction "1_P$1") (pintype "passive"))
      (node (ref "C402") (pin "P$1") (pinfunction "1_P$1") (pintype "passive"))
      (node (ref "C603") (pin "P$1") (pinfunction "1_P$1") (pintype "passive"))
      (node (ref "C604") (pin "P$1") (pinfunction "1_P$1") (pintype "passive"))
      (node (ref "C606") (pin "P$1") (pinfunction "1_P$1") (pintype "passive"))
      (node (ref "C607") (pin "P$1") (pinfunction "1_P$1") (pintype "passive"))
      (node (ref "C608") (pin "P$1") (pinfunction "1_P$1") (pintype "passive"))
      (node (ref "C610") (pin "P$1") (pinfunction "1_P$1") (pintype "passive"))
      (node (ref "C612") (pin "P$1") (pinfunction "1_P$1") (pintype "passive"))
      (node (ref "C616") (pin "P$1") (pinfunction "1_P$1") (pintype "passive"))
      (node (ref "C701") (pin "P$1") (pinfunction "1_P$1") (pintype "passive"))
      (node (ref "C902") (pin "P$1") (pinfunction "1_P$1") (pintype "passive"))
      (node (ref "D2") (pin "A") (pinfunction "A_A") (pintype "passive"))
      (node (ref "JX301") (pin "1") (pinfunction "S_1") (pintype "passive"))
      (node (ref "R301") (pin "P$2") (pinfunction "2_P$2") (pintype "passive"))
      (node (ref "R302") (pin "P$2") (pinfunction "2_P$2") (pintype "passive"))
      (node (ref "R303") (pin "P$2") (pinfunction "2_P$2") (pintype "passive"))
      (node (ref "R304") (pin "P$2") (pinfunction "2_P$2") (pintype "passive"))
      (node (ref "R305") (pin "P$2") (pinfunction "2_P$2") (pintype "passive"))
      (node (ref "R306") (pin "P$2") (pinfunction "2_P$2") (pintype "passive"))
      (node (ref "R307") (pin "P$2") (pinfunction "2_P$2") (pintype "passive"))
      (node (ref "R401") (pin "P$2") (pinfunction "2_P$2") (pintype "passive"))
      (node (ref "R402") (pin "P$2") (pinfunction "2_P$2") (pintype "passive"))
      (node (ref "R602") (pin "P$2") (pinfunction "2_P$2") (pintype "passive"))
      (node (ref "R604") (pin "P$2") (pinfunction "2_P$2") (pintype "passive"))
      (node (ref "U101") (pin "100") (pinfunction "VDD_100") (pintype "power_in"))
      (node (ref "U101") (pin "11") (pinfunction "VDD_11") (pintype "power_in"))
      (node (ref "U101") (pin "19") (pinfunction "VDD_19") (pintype "power_in"))
      (node (ref "U101") (pin "21") (pinfunction "VREF+_21") (pintype "input"))
      (node (ref "U101") (pin "22") (pinfunction "VDDA_22") (pintype "power_in"))
      (node (ref "U101") (pin "28") (pinfunction "VDD_28") (pintype "power_in"))
      (node (ref "U101") (pin "50") (pinfunction "VDD_50") (pintype "power_in"))
      (node (ref "U101") (pin "75") (pinfunction "VDD_75") (pintype "power_in"))
      (node (ref "U102") (pin "3") (pinfunction "~{W}_3") (pintype "bidirectional"))
      (node (ref "U102") (pin "7") (pinfunction "~{HOLD}_7") (pintype "bidirectional"))
      (node (ref "U102") (pin "8") (pinfunction "VDD_8") (pintype "bidirectional"))
      (node (ref "U201") (pin "10") (pinfunction "OE_10") (pintype "input"))
      (node (ref "U201") (pin "19") (pinfunction "VCCB_19") (pintype "input"))
      (node (ref "U201") (pin "2") (pinfunction "VCCA_2") (pintype "input"))
      (node (ref "U202") (pin "10") (pinfunction "OE_10") (pintype "input"))
      (node (ref "U202") (pin "19") (pinfunction "VCCB_19") (pintype "input"))
      (node (ref "U202") (pin "2") (pinfunction "VCCA_2") (pintype "input"))
      (node (ref "U301") (pin "4") (pinfunction "VCC_4") (pintype "passive"))
      (node (ref "U401") (pin "3") (pinfunction "VCC_3") (pintype "input"))
      (node (ref "U603") (pin "7") (pinfunction "VOUT2_7") (pintype "bidirectional"))
      (node (ref "U701") (pin "1") (pinfunction "~{SHDN}_1") (pintype "input"))
      (node (ref "U701") (pin "10") (pinfunction "VIN_10") (pintype "power_in"))
      (node (ref "U901") (pin "10") (pinfunction "OE_10") (pintype "input"))
      (node (ref "U901") (pin "19") (pinfunction "VCCB_19") (pintype "input"))
      (node (ref "U901") (pin "2") (pinfunction "VCCA_2") (pintype "input"))
      (node (ref "VDD_3V1101") (pin "P$1") (pinfunction "P$1_P$1") (pintype "passive"))
    )
    (net (code "40") (name "FMU-~{RESET}") (class "Default")
      (node (ref "C609") (pin "P$2") (pinfunction "2_P$2") (pintype "passive"))
      (node (ref "R635") (pin "P$1") (pinfunction "1_P$1") (pintype "passive"))
      (node (ref "S601") (pin "A1") (pinfunction "1_A1") (pintype "passive"))
      (node (ref "U101") (pin "14") (pinfunction "NRST_14") (pintype "input"))
      (node (ref "U603") (pin "3") (pinfunction "POR2_3") (pintype "bidirectional"))
      (node (ref "U701") (pin "4") (pinfunction "~{RESET}_4") (pintype "input"))
    )
    (net (code "41") (name "FMU_AUX_ADC1") (class "Default")
      (node (ref "R408") (pin "P$1") (pinfunction "1_P$1") (pintype "passive"))
      (node (ref "U101") (pin "18") (pinfunction "PC3_18") (pintype "bidirectional"))
    )
    (net (code "42") (name "FMU_AUX_ADC2") (class "Default")
      (node (ref "R407") (pin "P$1") (pinfunction "1_P$1") (pintype "passive"))
      (node (ref "U101") (pin "33") (pinfunction "PC4_33") (pintype "bidirectional"))
    )
    (net (code "43") (name "FRAM_MISO") (class "Default")
      (node (ref "U101") (pin "53") (pinfunction "PB14_53") (pintype "bidirectional"))
      (node (ref "U102") (pin "2") (pinfunction "Q_2") (pintype "bidirectional"))
    )
    (net (code "44") (name "FRAM_MOSI") (class "Default")
      (node (ref "U101") (pin "54") (pinfunction "PB15_54") (pintype "bidirectional"))
      (node (ref "U102") (pin "5") (pinfunction "D_5") (pintype "bidirectional"))
    )
    (net (code "45") (name "FRAM_SCK") (class "Default")
      (node (ref "U101") (pin "52") (pinfunction "PB13_52") (pintype "bidirectional"))
      (node (ref "U102") (pin "6") (pinfunction "C_6") (pintype "bidirectional"))
    )
    (net (code "46") (name "GND") (class "Default")
      (node (ref "B601") (pin "2") (pinfunction "NEG_2") (pintype "bidirectional"))
      (node (ref "C1001") (pin "P$2") (pinfunction "2_P$2") (pintype "passive"))
      (node (ref "C1002") (pin "P$2") (pinfunction "2_P$2") (pintype "passive"))
      (node (ref "C1003") (pin "P$2") (pinfunction "2_P$2") (pintype "passive"))
      (node (ref "C1004") (pin "P$2") (pinfunction "2_P$2") (pintype "passive"))
      (node (ref "C1005") (pin "P$2") (pinfunction "2_P$2") (pintype "passive"))
      (node (ref "C1008") (pin "P$2") (pinfunction "2_P$2") (pintype "passive"))
      (node (ref "C101") (pin "P$2") (pinfunction "2_P$2") (pintype "passive"))
      (node (ref "C102") (pin "P$2") (pinfunction "2_P$2") (pintype "passive"))
      (node (ref "C103") (pin "P$1") (pinfunction "1_P$1") (pintype "passive"))
      (node (ref "C1101") (pin "P$2") (pinfunction "2_P$2") (pintype "passive"))
      (node (ref "C1102") (pin "P$2") (pinfunction "2_P$2") (pintype "passive"))
      (node (ref "C1103") (pin "P$2") (pinfunction "2_P$2") (pintype "passive"))
      (node (ref "C1104") (pin "P$2") (pinfunction "2_P$2") (pintype "passive"))
      (node (ref "C1105") (pin "P$2") (pinfunction "2_P$2") (pintype "passive"))
      (node (ref "C1106") (pin "P$2") (pinfunction "2_P$2") (pintype "passive"))
      (node (ref "C1107") (pin "P$2") (pinfunction "2_P$2") (pintype "passive"))
      (node (ref "C1108") (pin "P$2") (pinfunction "2_P$2") (pintype "passive"))
      (node (ref "C1109") (pin "P$2") (pinfunction "2_P$2") (pintype "passive"))
      (node (ref "C1110") (pin "P$2") (pinfunction "2_P$2") (pintype "passive"))
      (node (ref "C201") (pin "P$2") (pinfunction "2_P$2") (pintype "passive"))
      (node (ref "C202") (pin "P$2") (pinfunction "2_P$2") (pintype "passive"))
      (node (ref "C401") (pin "P$2") (pinfunction "2_P$2") (pintype "passive"))
      (node (ref "C402") (pin "P$2") (pinfunction "2_P$2") (pintype "passive"))
      (node (ref "C501") (pin "P$2") (pinfunction "2_P$2") (pintype "passive"))
      (node (ref "C502") (pin "P$2") (pinfunction "2_P$2") (pintype "passive"))
      (node (ref "C503") (pin "P$2") (pinfunction "2_P$2") (pintype "passive"))
      (node (ref "C504") (pin "P$2") (pinfunction "2_P$2") (pintype "passive"))
      (node (ref "C505") (pin "P$2") (pinfunction "2_P$2") (pintype "passive"))
      (node (ref "C506") (pin "P$2") (pinfunction "2_P$2") (pintype "passive"))
      (node (ref "C507") (pin "P$2") (pinfunction "2_P$2") (pintype "passive"))
      (node (ref "C508") (pin "P$2") (pinfunction "2_P$2") (pintype "passive"))
      (node (ref "C509") (pin "P$2") (pinfunction "2_P$2") (pintype "passive"))
      (node (ref "C511") (pin "P$2") (pinfunction "2_P$2") (pintype "passive"))
      (node (ref "C512") (pin "P$2") (pinfunction "2_P$2") (pintype "passive"))
      (node (ref "C513") (pin "P$2") (pinfunction "2_P$2") (pintype "passive"))
      (node (ref "C514") (pin "P$2") (pinfunction "2_P$2") (pintype "passive"))
      (node (ref "C515") (pin "P$2") (pinfunction "2_P$2") (pintype "passive"))
      (node (ref "C601") (pin "P$2") (pinfunction "2_P$2") (pintype "passive"))
      (node (ref "C602") (pin "P$1") (pinfunction "1_P$1") (pintype "passive"))
      (node (ref "C603") (pin "P$2") (pinfunction "2_P$2") (pintype "passive"))
      (node (ref "C604") (pin "P$2") (pinfunction "2_P$2") (pintype "passive"))
      (node (ref "C605") (pin "P$2") (pinfunction "2_P$2") (pintype "passive"))
      (node (ref "C606") (pin "P$2") (pinfunction "2_P$2") (pintype "passive"))
      (node (ref "C607") (pin "P$2") (pinfunction "2_P$2") (pintype "passive"))
      (node (ref "C608") (pin "P$2") (pinfunction "2_P$2") (pintype "passive"))
      (node (ref "C609") (pin "P$1") (pinfunction "1_P$1") (pintype "passive"))
      (node (ref "C610") (pin "P$2") (pinfunction "2_P$2") (pintype "passive"))
      (node (ref "C611") (pin "P$2") (pinfunction "2_P$2") (pintype "passive"))
      (node (ref "C612") (pin "P$2") (pinfunction "2_P$2") (pintype "passive"))
      (node (ref "C613") (pin "P$2") (pinfunction "2_P$2") (pintype "passive"))
      (node (ref "C614") (pin "P$2") (pinfunction "2_P$2") (pintype "passive"))
      (node (ref "C615") (pin "P$2") (pinfunction "2_P$2") (pintype "passive"))
      (node (ref "C616") (pin "P$2") (pinfunction "2_P$2") (pintype "passive"))
      (node (ref "C617") (pin "P$2") (pinfunction "2_P$2") (pintype "passive"))
      (node (ref "C618") (pin "P$2") (pinfunction "2_P$2") (pintype "passive"))
      (node (ref "C701") (pin "P$2") (pinfunction "2_P$2") (pintype "passive"))
      (node (ref "C702") (pin "P$2") (pinfunction "2_P$2") (pintype "passive"))
      (node (ref "C703") (pin "P$2") (pinfunction "2_P$2") (pintype "passive"))
      (node (ref "C704") (pin "P$2") (pinfunction "2_P$2") (pintype "passive"))
      (node (ref "C801") (pin "P$1") (pinfunction "1_P$1") (pintype "passive"))
      (node (ref "C802") (pin "P$2") (pinfunction "2_P$2") (pintype "passive"))
      (node (ref "C803") (pin "P$2") (pinfunction "2_P$2") (pintype "passive"))
      (node (ref "C804") (pin "P$2") (pinfunction "2_P$2") (pintype "passive"))
      (node (ref "C805") (pin "P$2") (pinfunction "2_P$2") (pintype "passive"))
      (node (ref "C806") (pin "P$1") (pinfunction "1_P$1") (pintype "passive"))
      (node (ref "C901") (pin "P$2") (pinfunction "2_P$2") (pintype "passive"))
      (node (ref "C902") (pin "P$2") (pinfunction "2_P$2") (pintype "passive"))
      (node (ref "C903") (pin "P$2") (pinfunction "2_P$2") (pintype "passive"))
      (node (ref "D201") (pin "A") (pinfunction "A_A") (pintype "passive"))
      (node (ref "D202") (pin "A") (pinfunction "A_A") (pintype "passive"))
      (node (ref "D203") (pin "A") (pinfunction "A_A") (pintype "passive"))
      (node (ref "D401") (pin "A") (pinfunction "A_A") (pintype "passive"))
      (node (ref "D402") (pin "A") (pinfunction "A_A") (pintype "passive"))
      (node (ref "D403") (pin "A") (pinfunction "A_A") (pintype "passive"))
      (node (ref "D404") (pin "A") (pinfunction "A_A") (pintype "passive"))
      (node (ref "D701") (pin "A") (pinfunction "A_A") (pintype "passive"))
      (node (ref "D801") (pin "A") (pinfunction "A_A") (pintype "passive"))
      (node (ref "D901") (pin "A") (pinfunction "A_A") (pintype "passive"))
      (node (ref "D902") (pin "A") (pinfunction "A_A") (pintype "passive"))
      (node (ref "D903") (pin "A") (pinfunction "A_A") (pintype "passive"))
      (node (ref "GND.1116") (pin "P$1") (pinfunction "P$1_P$1") (pintype "passive"))
      (node (ref "GND1116") (pin "P$1") (pinfunction "P$1_P$1") (pintype "passive"))
      (node (ref "J201") (pin "6") (pinfunction "6_6") (pintype "passive"))
      (node (ref "J202") (pin "6") (pinfunction "6_6") (pintype "passive"))
      (node (ref "J203") (pin "6") (pinfunction "6_6") (pintype "passive"))
      (node (ref "J204") (pin "6") (pinfunction "6_6") (pintype "passive"))
      (node (ref "J301") (pin "GND") (pinfunction "5_GND") (pintype "power_in"))
      (node (ref "J301") (pin "GND1") (pinfunction "GND1_GND1") (pintype "bidirectional"))
      (node (ref "J301") (pin "GND2") (pinfunction "GND2_GND2") (pintype "bidirectional"))
      (node (ref "J301") (pin "GND3") (pinfunction "GND3_GND3") (pintype "bidirectional"))
      (node (ref "J301") (pin "GND4") (pinfunction "GND4_GND4") (pintype "bidirectional"))
      (node (ref "J302") (pin "4") (pinfunction "4_4") (pintype "passive"))
      (node (ref "J401") (pin "4") (pinfunction "4_4") (pintype "passive"))
      (node (ref "J402") (pin "3") (pinfunction "3_3") (pintype "passive"))
      (node (ref "J403") (pin "7") (pinfunction "7_7") (pintype "passive"))
      (node (ref "J404") (pin "3") (pinfunction "3_3") (pintype "passive"))
      (node (ref "J404") (pin "5") (pinfunction "5_5") (pintype "passive"))
      (node (ref "J405") (pin "4") (pinfunction "4_4") (pintype "passive"))
      (node (ref "J601") (pin "5") (pinfunction "5_5") (pintype "passive"))
      (node (ref "J601") (pin "6") (pinfunction "6_6") (pintype "passive"))
      (node (ref "J701") (pin "2") (pinfunction "2_2") (pintype "passive"))
      (node (ref "J801") (pin "P$2") (pinfunction "P$2_P$2") (pintype "bidirectional"))
      (node (ref "J901") (pin "12") (pinfunction "S_12") (pintype "passive"))
      (node (ref "J901") (pin "15") (pinfunction "S_15") (pintype "passive"))
      (node (ref "J901") (pin "18") (pinfunction "S_18") (pintype "passive"))
      (node (ref "J901") (pin "21") (pinfunction "S_21") (pintype "passive"))
      (node (ref "J901") (pin "24") (pinfunction "S_24") (pintype "passive"))
      (node (ref "J901") (pin "27") (pinfunction "S_27") (pintype "passive"))
      (node (ref "J901") (pin "3") (pinfunction "S_3") (pintype "passive"))
      (node (ref "J901") (pin "30") (pinfunction "S_30") (pintype "passive"))
      (node (ref "J901") (pin "33") (pinfunction "S_33") (pintype "passive"))
      (node (ref "J901") (pin "36") (pinfunction "S_36") (pintype "passive"))
      (node (ref "J901") (pin "39") (pinfunction "S_39") (pintype "passive"))
      (node (ref "J901") (pin "42") (pinfunction "S_42") (pintype "passive"))
      (node (ref "J901") (pin "45") (pinfunction "S_45") (pintype "passive"))
      (node (ref "J901") (pin "48") (pinfunction "S_48") (pintype "passive"))
      (node (ref "J901") (pin "6") (pinfunction "S_6") (pintype "passive"))
      (node (ref "J901") (pin "9") (pinfunction "S_9") (pintype "passive"))
      (node (ref "JX301") (pin "3") (pinfunction "S_3") (pintype "passive"))
      (node (ref "JX301") (pin "5") (pinfunction "S_5") (pintype "passive"))
      (node (ref "JX301") (pin "9") (pinfunction "S_9") (pintype "passive"))
      (node (ref "JX801") (pin "3") (pinfunction "GND_3") (pintype "bidirectional"))
      (node (ref "JX802") (pin "3") (pinfunction "S_3") (pintype "passive"))
      (node (ref "JX802") (pin "5") (pinfunction "S_5") (pintype "passive"))
      (node (ref "JX802") (pin "9") (pinfunction "S_9") (pintype "passive"))
      (node (ref "L1101") (pin "P$3") (pinfunction "P$3_P$3") (pintype "bidirectional"))
      (node (ref "L1101") (pin "P$4") (pinfunction "P$3_P$4") (pintype "bidirectional"))
      (node (ref "L1101") (pin "P$5") (pinfunction "P$3_P$5") (pintype "bidirectional"))
      (node (ref "L1102") (pin "P$3") (pinfunction "P$3_P$3") (pintype "bidirectional"))
      (node (ref "L1102") (pin "P$4") (pinfunction "P$3_P$4") (pintype "bidirectional"))
      (node (ref "L1102") (pin "P$5") (pinfunction "P$3_P$5") (pintype "bidirectional"))
      (node (ref "L201") (pin "P$3") (pinfunction "P$3_P$3") (pintype "bidirectional"))
      (node (ref "L201") (pin "P$4") (pinfunction "P$3_P$4") (pintype "bidirectional"))
      (node (ref "L201") (pin "P$5") (pinfunction "P$3_P$5") (pintype "bidirectional"))
      (node (ref "L202") (pin "P$3") (pinfunction "P$3_P$3") (pintype "bidirectional"))
      (node (ref "L202") (pin "P$4") (pinfunction "P$3_P$4") (pintype "bidirectional"))
      (node (ref "L202") (pin "P$5") (pinfunction "P$3_P$5") (pintype "bidirectional"))
      (node (ref "L203") (pin "P$3") (pinfunction "P$3_P$3") (pintype "bidirectional"))
      (node (ref "L203") (pin "P$4") (pinfunction "P$3_P$4") (pintype "bidirectional"))
      (node (ref "L203") (pin "P$5") (pinfunction "P$3_P$5") (pintype "bidirectional"))
      (node (ref "L401") (pin "P$3") (pinfunction "P$3_P$3") (pintype "bidirectional"))
      (node (ref "L401") (pin "P$4") (pinfunction "P$3_P$4") (pintype "bidirectional"))
      (node (ref "L401") (pin "P$5") (pinfunction "P$3_P$5") (pintype "bidirectional"))
      (node (ref "L402") (pin "P$3") (pinfunction "P$3_P$3") (pintype "bidirectional"))
      (node (ref "L402") (pin "P$4") (pinfunction "P$3_P$4") (pintype "bidirectional"))
      (node (ref "L402") (pin "P$5") (pinfunction "P$3_P$5") (pintype "bidirectional"))
      (node (ref "L403") (pin "P$3") (pinfunction "P$3_P$3") (pintype "bidirectional"))
      (node (ref "L403") (pin "P$4") (pinfunction "P$3_P$4") (pintype "bidirectional"))
      (node (ref "L403") (pin "P$5") (pinfunction "P$3_P$5") (pintype "bidirectional"))
      (node (ref "L404") (pin "P$3") (pinfunction "P$3_P$3") (pintype "bidirectional"))
      (node (ref "L404") (pin "P$4") (pinfunction "P$3_P$4") (pintype "bidirectional"))
      (node (ref "L404") (pin "P$5") (pinfunction "P$3_P$5") (pintype "bidirectional"))
      (node (ref "L603") (pin "P$3") (pinfunction "P$3_P$3") (pintype "bidirectional"))
      (node (ref "L603") (pin "P$4") (pinfunction "P$3_P$4") (pintype "bidirectional"))
      (node (ref "L603") (pin "P$5") (pinfunction "P$3_P$5") (pintype "bidirectional"))
      (node (ref "L901") (pin "P$3") (pinfunction "P$3_P$3") (pintype "bidirectional"))
      (node (ref "L901") (pin "P$4") (pinfunction "P$3_P$4") (pintype "bidirectional"))
      (node (ref "L901") (pin "P$5") (pinfunction "P$3_P$5") (pintype "bidirectional"))
      (node (ref "R1001") (pin "P$1") (pinfunction "1_P$1") (pintype "passive"))
      (node (ref "R1002") (pin "P$1") (pinfunction "1_P$1") (pintype "passive"))
      (node (ref "R102") (pin "P$2") (pinfunction "2_P$2") (pintype "passive"))
      (node (ref "R1103") (pin "P$2") (pinfunction "2_P$2") (pintype "passive"))
      (node (ref "R1104") (pin "P$2") (pinfunction "2_P$2") (pintype "passive"))
      (node (ref "R1107") (pin "P$2") (pinfunction "2_P$2") (pintype "passive"))
      (node (ref "R1111") (pin "P$2") (pinfunction "2_P$2") (pintype "passive"))
      (node (ref "R1114") (pin "P$2") (pinfunction "2_P$2") (pintype "passive"))
      (node (ref "R1115") (pin "P$1") (pinfunction "1_P$1") (pintype "passive"))
      (node (ref "R403") (pin "P$1") (pinfunction "1_P$1") (pintype "passive"))
      (node (ref "R610") (pin "P$2") (pinfunction "2_P$2") (pintype "passive"))
      (node (ref "R611") (pin "P$1") (pinfunction "1_P$1") (pintype "passive"))
      (node (ref "R615") (pin "P$2") (pinfunction "2_P$2") (pintype "passive"))
      (node (ref "R616") (pin "P$2") (pinfunction "2_P$2") (pintype "passive"))
      (node (ref "R617") (pin "P$2") (pinfunction "2_P$2") (pintype "passive"))
      (node (ref "R621") (pin "1") (pinfunction "1_1") (pintype "passive"))
      (node (ref "R702") (pin "P$2") (pinfunction "2_P$2") (pintype "passive"))
      (node (ref "R704") (pin "P$1") (pinfunction "1_P$1") (pintype "passive"))
      (node (ref "R706") (pin "P$2") (pinfunction "2_P$2") (pintype "passive"))
      (node (ref "R708") (pin "P$1") (pinfunction "1_P$1") (pintype "passive"))
      (node (ref "R711") (pin "P$1") (pinfunction "1_P$1") (pintype "passive"))
      (node (ref "R713") (pin "P$2") (pinfunction "2_P$2") (pintype "passive"))
      (node (ref "R801") (pin "P$2") (pinfunction "2_P$2") (pintype "passive"))
      (node (ref "R802") (pin "P$2") (pinfunction "2_P$2") (pintype "passive"))
      (node (ref "R919") (pin "P$1") (pinfunction "1_P$1") (pintype "passive"))
      (node (ref "S601") (pin "B3") (pinfunction "2_B3") (pintype "passive"))
      (node (ref "S801") (pin "B3") (pinfunction "2_B3") (pintype "passive"))
      (node (ref "U1001") (pin "2") (pinfunction "VSS_2") (pintype "bidirectional"))
      (node (ref "U1001") (pin "5") (pinfunction "~{CE}_5") (pintype "bidirectional"))
      (node (ref "U1001") (pin "6") (pinfunction "VBAT_6") (pintype "bidirectional"))
      (node (ref "U1001") (pin "GND") (pinfunction "VSS_GND") (pintype "bidirectional"))
      (node (ref "U1001") (pin "P$2") (pinfunction "VSS_P$2") (pintype "bidirectional"))
      (node (ref "U1001") (pin "P$3") (pinfunction "VSS_P$3") (pintype "bidirectional"))
      (node (ref "U1002") (pin "2") (pinfunction "GND_2") (pintype "bidirectional"))
      (node (ref "U1002") (pin "GND") (pinfunction "GND_GND") (pintype "bidirectional"))
      (node (ref "U101") (pin "10") (pinfunction "VSS_10") (pintype "power_in"))
      (node (ref "U101") (pin "20") (pinfunction "VSSA_20") (pintype "power_in"))
      (node (ref "U101") (pin "27") (pinfunction "VSS_27") (pintype "power_in"))
      (node (ref "U101") (pin "74") (pinfunction "VSS_74") (pintype "power_in"))
      (node (ref "U101") (pin "99") (pinfunction "VSS_99") (pintype "power_in"))
      (node (ref "U102") (pin "4") (pinfunction "VSS_4") (pintype "bidirectional"))
      (node (ref "U1101") (pin "P$10") (pinfunction "GND_P$10") (pintype "bidirectional"))
      (node (ref "U1101") (pin "P$25") (pinfunction "GND_P$25") (pintype "bidirectional"))
      (node (ref "U201") (pin "11") (pinfunction "GND_11") (pintype "power_in"))
      (node (ref "U202") (pin "11") (pinfunction "GND_11") (pintype "power_in"))
      (node (ref "U301") (pin "6") (pinfunction "GND_6") (pintype "power_in"))
      (node (ref "U302") (pin "2") (pinfunction "GND_2") (pintype "bidirectional"))
      (node (ref "U401") (pin "2") (pinfunction "GND_2") (pintype "power_in"))
      (node (ref "U401") (pin "5") (pinfunction "SHDN_5") (pintype "input"))
      (node (ref "U401") (pin "8") (pinfunction "RS_8") (pintype "input"))
      (node (ref "U501") (pin "10") (pinfunction "RES_P10_GND_10") (pintype "bidirectional"))
      (node (ref "U501") (pin "11") (pinfunction "RES_P11_GND_11") (pintype "bidirectional"))
      (node (ref "U501") (pin "12") (pinfunction "RES_P12_GND_12") (pintype "bidirectional"))
      (node (ref "U501") (pin "13") (pinfunction "GND_13") (pintype "bidirectional"))
      (node (ref "U501") (pin "8") (pinfunction "RES_P8_GND_8") (pintype "bidirectional"))
      (node (ref "U501") (pin "9") (pinfunction "RES_P9_GND_9") (pintype "bidirectional"))
      (node (ref "U502") (pin "10") (pinfunction "GND_10") (pintype "bidirectional"))
      (node (ref "U502") (pin "11") (pinfunction "GND_11") (pintype "bidirectional"))
      (node (ref "U502") (pin "12") (pinfunction "GND_12") (pintype "bidirectional"))
      (node (ref "U502") (pin "13") (pinfunction "GND_13") (pintype "bidirectional"))
      (node (ref "U502") (pin "9") (pinfunction "GND_9") (pintype "bidirectional"))
      (node (ref "U504") (pin "10") (pinfunction "RSRV_10") (pintype "bidirectional"))
      (node (ref "U504") (pin "12") (pinfunction "GND_12") (pintype "bidirectional"))
      (node (ref "U504") (pin "13") (pinfunction "GND_13") (pintype "bidirectional"))
      (node (ref "U504") (pin "16") (pinfunction "GND_16") (pintype "bidirectional"))
      (node (ref "U504") (pin "5") (pinfunction "GND_5") (pintype "bidirectional"))
      (node (ref "U505") (pin "1") (pinfunction "CLKIN_1") (pintype "bidirectional"))
      (node (ref "U505") (pin "18") (pinfunction "GND_18") (pintype "bidirectional"))
      (node (ref "U506") (pin "2") (pinfunction "PS_2") (pintype "bidirectional"))
      (node (ref "U506") (pin "3") (pinfunction "GND_3") (pintype "bidirectional"))
      (node (ref "U601") (pin "2") (pinfunction "VSS_2") (pintype "bidirectional"))
      (node (ref "U601") (pin "6") (pinfunction "VBAT_6") (pintype "bidirectional"))
      (node (ref "U601") (pin "GND") (pinfunction "VSS_GND") (pintype "bidirectional"))
      (node (ref "U601") (pin "P$2") (pinfunction "VSS_P$2") (pintype "bidirectional"))
      (node (ref "U601") (pin "P$3") (pinfunction "VSS_P$3") (pintype "bidirectional"))
      (node (ref "U602") (pin "2") (pinfunction "VSS_2") (pintype "bidirectional"))
      (node (ref "U602") (pin "6") (pinfunction "VBAT_6") (pintype "bidirectional"))
      (node (ref "U602") (pin "GND") (pinfunction "VSS_GND") (pintype "bidirectional"))
      (node (ref "U602") (pin "P$2") (pinfunction "VSS_P$2") (pintype "bidirectional"))
      (node (ref "U602") (pin "P$3") (pinfunction "VSS_P$3") (pintype "bidirectional"))
      (node (ref "U603") (pin "2") (pinfunction "GND_2") (pintype "bidirectional"))
      (node (ref "U603") (pin "GND") (pinfunction "GND_GND") (pintype "bidirectional"))
      (node (ref "U701") (pin "5") (pinfunction "GND_5") (pintype "power_in"))
      (node (ref "U702") (pin "4") (pinfunction "GND_4") (pintype "power_in"))
      (node (ref "U801") (pin "23") (pinfunction "VSS_1_23") (pintype "power_in"))
      (node (ref "U801") (pin "35") (pinfunction "VSS_2_35") (pintype "power_in"))
      (node (ref "U801") (pin "47") (pinfunction "VSS_3_47") (pintype "power_in"))
      (node (ref "U801") (pin "8") (pinfunction "VSSA_8") (pintype "power_in"))
      (node (ref "U901") (pin "11") (pinfunction "GND_11") (pintype "power_in"))
      (node (ref "U902") (pin "11") (pinfunction "GND_11") (pintype "power_in"))
      (node (ref "U903") (pin "1") (pinfunction "~{1OE}_1") (pintype "input"))
      (node (ref "U903") (pin "4") (pinfunction "GND_4") (pintype "power_in"))
      (node (ref "VP_0") (pin "VP") (pinfunction "VP_VP") (pintype "passive"))
      (node (ref "VP_1") (pin "VP") (pinfunction "VP_VP") (pintype "passive"))
      (node (ref "VP_10") (pin "VP") (pinfunction "VP_VP") (pintype "passive"))
      (node (ref "VP_11") (pin "VP") (pinfunction "VP_VP") (pintype "passive"))
      (node (ref "VP_12") (pin "VP") (pinfunction "VP_VP") (pintype "passive"))
      (node (ref "VP_13") (pin "VP") (pinfunction "VP_VP") (pintype "passive"))
      (node (ref "VP_14") (pin "VP") (pinfunction "VP_VP") (pintype "passive"))
      (node (ref "VP_15") (pin "VP") (pinfunction "VP_VP") (pintype "passive"))
      (node (ref "VP_16") (pin "VP") (pinfunction "VP_VP") (pintype "passive"))
      (node (ref "VP_17") (pin "VP") (pinfunction "VP_VP") (pintype "passive"))
      (node (ref "VP_18") (pin "VP") (pinfunction "VP_VP") (pintype "passive"))
      (node (ref "VP_19") (pin "VP") (pinfunction "VP_VP") (pintype "passive"))
      (node (ref "VP_2") (pin "VP") (pinfunction "VP_VP") (pintype "passive"))
      (node (ref "VP_20") (pin "VP") (pinfunction "VP_VP") (pintype "passive"))
      (node (ref "VP_21") (pin "VP") (pinfunction "VP_VP") (pintype "passive"))
      (node (ref "VP_22") (pin "VP") (pinfunction "VP_VP") (pintype "passive"))
      (node (ref "VP_23") (pin "VP") (pinfunction "VP_VP") (pintype "passive"))
      (node (ref "VP_24") (pin "VP") (pinfunction "VP_VP") (pintype "passive"))
      (node (ref "VP_25") (pin "VP") (pinfunction "VP_VP") (pintype "passive"))
      (node (ref "VP_26") (pin "VP") (pinfunction "VP_VP") (pintype "passive"))
      (node (ref "VP_27") (pin "VP") (pinfunction "VP_VP") (pintype "passive"))
      (node (ref "VP_28") (pin "VP") (pinfunction "VP_VP") (pintype "passive"))
      (node (ref "VP_29") (pin "VP") (pinfunction "VP_VP") (pintype "passive"))
      (node (ref "VP_3") (pin "VP") (pinfunction "VP_VP") (pintype "passive"))
      (node (ref "VP_30") (pin "VP") (pinfunction "VP_VP") (pintype "passive"))
      (node (ref "VP_4") (pin "VP") (pinfunction "VP_VP") (pintype "passive"))
      (node (ref "VP_5") (pin "VP") (pinfunction "VP_VP") (pintype "passive"))
      (node (ref "VP_6") (pin "VP") (pinfunction "VP_VP") (pintype "passive"))
      (node (ref "VP_7") (pin "VP") (pinfunction "VP_VP") (pintype "passive"))
      (node (ref "VP_8") (pin "VP") (pinfunction "VP_VP") (pintype "passive"))
      (node (ref "VP_9") (pin "VP") (pinfunction "VP_VP") (pintype "passive"))
      (node (ref "X101") (pin "2") (pinfunction "NC_2_2") (pintype "power_in"))
      (node (ref "X101") (pin "4") (pinfunction "NC_4_4") (pintype "power_in"))
      (node (ref "X503") (pin "2") (pinfunction "S_2") (pintype "passive"))
      (node (ref "X801") (pin "2") (pinfunction "NC_2_2") (pintype "power_in"))
      (node (ref "X801") (pin "4") (pinfunction "NC_4_4") (pintype "power_in"))
    )
    (net (code "47") (name "GPIO_EXT_1") (class "Default")
      (node (ref "J403") (pin "6") (pinfunction "6_6") (pintype "passive"))
      (node (ref "U101") (pin "8") (pinfunction "PC14_8") (pintype "bidirectional"))
    )
    (net (code "48") (name "GYRO_DRDY") (class "Default")
      (node (ref "U101") (pin "35") (pinfunction "PB0_35") (pintype "bidirectional"))
      (node (ref "U501") (pin "6") (pinfunction "DRDY/INT2_6") (pintype "output"))
      (node (ref "U502") (pin "6") (pinfunction "DRDY/INT2_6") (pintype "bidirectional"))
      (node (ref "X503") (pin "5") (pinfunction "S_5") (pintype "passive"))
    )
    (net (code "49") (name "IO-BOOT0") (class "Default")
      (node (ref "IO-BOOT1101") (pin "P$1") (pinfunction "P$1_P$1") (pintype "passive"))
      (node (ref "R801") (pin "P$1") (pinfunction "1_P$1") (pintype "passive"))
      (node (ref "U801") (pin "44") (pinfunction "BOOT0_44") (pintype "input"))
    )
    (net (code "50") (name "IO-CH1") (class "Default")
      (node (ref "U801") (pin "10") (pinfunction "PA0_10") (pintype "bidirectional"))
      (node (ref "U902") (pin "9") (pinfunction "A8_9") (pintype "bidirectional"))
    )
    (net (code "51") (name "IO-CH2") (class "Default")
      (node (ref "U801") (pin "11") (pinfunction "PA1_11") (pintype "bidirectional"))
      (node (ref "U902") (pin "8") (pinfunction "A7_8") (pintype "bidirectional"))
    )
    (net (code "52") (name "IO-CH3") (class "Default")
      (node (ref "U801") (pin "45") (pinfunction "PB8_45") (pintype "bidirectional"))
      (node (ref "U902") (pin "7") (pinfunction "A6_7") (pintype "bidirectional"))
    )
    (net (code "53") (name "IO-CH4") (class "Default")
      (node (ref "U801") (pin "46") (pinfunction "PB9_46") (pintype "bidirectional"))
      (node (ref "U902") (pin "6") (pinfunction "A5_6") (pintype "bidirectional"))
    )
    (net (code "54") (name "IO-CH5") (class "Default")
      (node (ref "U801") (pin "16") (pinfunction "PA6_16") (pintype "bidirectional"))
      (node (ref "U902") (pin "5") (pinfunction "A4_5") (pintype "bidirectional"))
    )
    (net (code "55") (name "IO-CH6") (class "Default")
      (node (ref "U801") (pin "17") (pinfunction "PA7_17") (pintype "bidirectional"))
      (node (ref "U902") (pin "4") (pinfunction "A3_4") (pintype "bidirectional"))
    )
    (net (code "56") (name "IO-CH7") (class "Default")
      (node (ref "U801") (pin "18") (pinfunction "PB0_18") (pintype "bidirectional"))
      (node (ref "U902") (pin "3") (pinfunction "A2_3") (pintype "bidirectional"))
    )
    (net (code "57") (name "IO-CH8") (class "Default")
      (node (ref "U801") (pin "19") (pinfunction "PB1_19") (pintype "bidirectional"))
      (node (ref "U902") (pin "1") (pinfunction "A1_1") (pintype "bidirectional"))
    )
    (net (code "58") (name "IO-SWCLK") (class "Default")
      (node (ref "JX802") (pin "4") (pinfunction "S_4") (pintype "passive"))
      (node (ref "U801") (pin "37") (pinfunction "PA14_37") (pintype "bidirectional"))
    )
    (net (code "59") (name "IO-SWDIO") (class "Default")
      (node (ref "JX802") (pin "2") (pinfunction "S_2") (pintype "passive"))
      (node (ref "U801") (pin "34") (pinfunction "PA13_34") (pintype "bidirectional"))
    )
    (net (code "60") (name "IO-SWO") (class "Default")
      (node (ref "JX802") (pin "6") (pinfunction "S_6") (pintype "passive"))
      (node (ref "U801") (pin "39") (pinfunction "PB3_39") (pintype "bidirectional"))
    )
    (net (code "61") (name "IO-USART1_RX") (class "Default")
      (node (ref "J801") (pin "P$3") (pinfunction "P$3_P$3") (pintype "bidirectional"))
      (node (ref "JX801") (pin "2") (pinfunction "+5V_2") (pintype "bidirectional"))
      (node (ref "U801") (pin "31") (pinfunction "PA10_31") (pintype "bidirectional"))
    )
    (net (code "62") (name "IO-USART1_TX") (class "Default")
      (node (ref "JX801") (pin "1") (pinfunction "PPM_1") (pintype "bidirectional"))
      (node (ref "R101") (pin "P$2") (pinfunction "2_P$2") (pintype "passive"))
      (node (ref "U801") (pin "30") (pinfunction "PA9_30") (pintype "bidirectional"))
    )
    (net (code "63") (name "IO-VDD_3V3") (class "Default")
      (node (ref "C1003") (pin "P$1") (pinfunction "1_P$1") (pintype "passive"))
      (node (ref "C1004") (pin "P$1") (pinfunction "1_P$1") (pintype "passive"))
      (node (ref "C802") (pin "P$1") (pinfunction "1_P$1") (pintype "passive"))
      (node (ref "C803") (pin "P$1") (pinfunction "1_P$1") (pintype "passive"))
      (node (ref "C804") (pin "P$1") (pinfunction "1_P$1") (pintype "passive"))
      (node (ref "C901") (pin "P$1") (pinfunction "1_P$1") (pintype "passive"))
      (node (ref "C903") (pin "P$1") (pinfunction "1_P$1") (pintype "passive"))
      (node (ref "D701") (pin "C") (pinfunction "C_C") (pintype "passive"))
      (node (ref "J702") (pin "1") (pinfunction "1_1") (pintype "passive"))
      (node (ref "JX802") (pin "1") (pinfunction "S_1") (pintype "passive"))
      (node (ref "U1002") (pin "7") (pinfunction "VOUT2_7") (pintype "bidirectional"))
      (node (ref "U801") (pin "24") (pinfunction "VDD_1_24") (pintype "power_in"))
      (node (ref "U801") (pin "36") (pinfunction "VDD_2_36") (pintype "power_in"))
      (node (ref "U801") (pin "48") (pinfunction "VDD_3_48") (pintype "power_in"))
      (node (ref "U801") (pin "9") (pinfunction "VDDA_9") (pintype "power_in"))
      (node (ref "U902") (pin "10") (pinfunction "OE_10") (pintype "input"))
      (node (ref "U902") (pin "19") (pinfunction "VCCB_19") (pintype "input"))
      (node (ref "U902") (pin "2") (pinfunction "VCCA_2") (pintype "input"))
      (node (ref "U903") (pin "8") (pinfunction "VCC_8") (pintype "power_in"))
      (node (ref "VP_31") (pin "VP") (pinfunction "VP_VP") (pintype "passive"))
      (node (ref "VP_32") (pin "VP") (pinfunction "VP_VP") (pintype "passive"))
    )
    (net (code "64") (name "IO-VDD_5V5") (class "Default")
      (node (ref "C1001") (pin "P$1") (pinfunction "1_P$1") (pintype "passive"))
      (node (ref "C1005") (pin "P$1") (pinfunction "1_P$1") (pintype "passive"))
      (node (ref "D1001") (pin "3") (pinfunction "CC_3") (pintype "passive"))
      (node (ref "J901") (pin "2") (pinfunction "S_2") (pintype "passive"))
      (node (ref "LED702") (pin "A") (pinfunction "A_A") (pintype "passive"))
      (node (ref "LED703") (pin "A") (pinfunction "A_A") (pintype "passive"))
      (node (ref "LED705") (pin "A") (pinfunction "A_A") (pintype "passive"))
      (node (ref "U1002") (pin "1") (pinfunction "VIN_1") (pintype "bidirectional"))
      (node (ref "U1002") (pin "4") (pinfunction "EN2_4") (pintype "bidirectional"))
    )
    (net (code "65") (name "IO-~{RESET}") (class "Default")
      (node (ref "C801") (pin "P$2") (pinfunction "2_P$2") (pintype "passive"))
      (node (ref "S801") (pin "A1") (pinfunction "1_A1") (pintype "passive"))
      (node (ref "U1002") (pin "3") (pinfunction "POR2_3") (pintype "bidirectional"))
      (node (ref "U801") (pin "7") (pinfunction "NRST_7") (pintype "input"))
    )
    (net (code "66") (name "IO-~{VDD_SERVO_IN_FAULT}") (class "Default")
      (node (ref "U1001") (pin "4") (pinfunction "~{FAULT}_4") (pintype "bidirectional"))
      (node (ref "U801") (pin "38") (pinfunction "PA15_38") (pintype "bidirectional"))
    )
    (net (code "67") (name "MAG_DRDY") (class "Default")
      (node (ref "U101") (pin "36") (pinfunction "PB1_36") (pintype "bidirectional"))
      (node (ref "U504") (pin "9") (pinfunction "INT2_9") (pintype "bidirectional"))
      (node (ref "X503") (pin "4") (pinfunction "S_4") (pintype "passive"))
    )
    (net (code "68") (name "MPU_DRDY") (class "Default")
      (node (ref "U101") (pin "62") (pinfunction "PD15_62") (pintype "bidirectional"))
      (node (ref "U505") (pin "12") (pinfunction "INT_12") (pintype "bidirectional"))
    )
    (net (code "69") (name "Net-(C102-1)") (class "Default")
      (node (ref "C102") (pin "P$1") (pinfunction "1_P$1") (pintype "passive"))
      (node (ref "U101") (pin "12") (pinfunction "OSC_IN_12") (pintype "input"))
      (node (ref "X101") (pin "3") (pinfunction "3_3") (pintype "bidirectional"))
    )
    (net (code "70") (name "Net-(C103-2)") (class "Default")
      (node (ref "C103") (pin "P$2") (pinfunction "2_P$2") (pintype "passive"))
      (node (ref "U101") (pin "13") (pinfunction "OSC_OUT_13") (pintype "output"))
      (node (ref "X101") (pin "1") (pinfunction "1_1") (pintype "bidirectional"))
    )
    (net (code "71") (name "Net-(C504-1)") (class "Default")
      (node (ref "C504") (pin "P$1") (pinfunction "1_P$1") (pintype "passive"))
      (node (ref "U501") (pin "14") (pinfunction "PLLFILT_14") (pintype "bidirectional"))
    )
    (net (code "72") (name "Net-(C505-1)") (class "Default")
      (node (ref "C505") (pin "P$1") (pinfunction "1_P$1") (pintype "passive"))
      (node (ref "U502") (pin "14") (pinfunction "CAP_14") (pintype "bidirectional"))
    )
    (net (code "73") (name "Net-(C509-1)") (class "Default")
      (node (ref "C509") (pin "P$1") (pinfunction "1_P$1") (pintype "passive"))
      (node (ref "U504") (pin "15") (pinfunction "C1_15") (pintype "bidirectional"))
    )
    (net (code "74") (name "Net-(C510-1)") (class "Default")
      (node (ref "C510") (pin "P$1") (pinfunction "1_P$1") (pintype "passive"))
      (node (ref "U504") (pin "2") (pinfunction "SETC_2") (pintype "bidirectional"))
    )
    (net (code "75") (name "Net-(C510-2)") (class "Default")
      (node (ref "C510") (pin "P$2") (pinfunction "2_P$2") (pintype "passive"))
      (node (ref "U504") (pin "3") (pinfunction "SETP_3") (pintype "bidirectional"))
    )
    (net (code "76") (name "Net-(C512-1)") (class "Default")
      (node (ref "C512") (pin "P$1") (pinfunction "1_P$1") (pintype "passive"))
      (node (ref "U505") (pin "10") (pinfunction "REGOUT_10") (pintype "bidirectional"))
    )
    (net (code "77") (name "Net-(C515-1)") (class "Default")
      (node (ref "C515") (pin "P$1") (pinfunction "1_P$1") (pintype "passive"))
      (node (ref "U505") (pin "20") (pinfunction "CPOUT_20") (pintype "bidirectional"))
    )
    (net (code "78") (name "Net-(C601-1)") (class "Default")
      (node (ref "C601") (pin "P$1") (pinfunction "1_P$1") (pintype "passive"))
      (node (ref "C615") (pin "P$1") (pinfunction "1_P$1") (pintype "passive"))
      (node (ref "L603") (pin "P$2") (pinfunction "P$2_P$2") (pintype "bidirectional"))
      (node (ref "R603") (pin "P$1") (pinfunction "1_P$1") (pintype "passive"))
      (node (ref "U603") (pin "1") (pinfunction "VIN_1") (pintype "bidirectional"))
      (node (ref "U603") (pin "4") (pinfunction "EN2_4") (pintype "bidirectional"))
    )
    (net (code "79") (name "Net-(C602-2)") (class "Default")
      (node (ref "C602") (pin "P$2") (pinfunction "2_P$2") (pintype "passive"))
      (node (ref "U603") (pin "6") (pinfunction "CSET_6") (pintype "bidirectional"))
    )
    (net (code "80") (name "Net-(C611-1)") (class "Default")
      (node (ref "C611") (pin "P$1") (pinfunction "1_P$1") (pintype "passive"))
      (node (ref "U101") (pin "49") (pinfunction "VCAP_1_49") (pintype "power_in"))
    )
    (net (code "81") (name "Net-(C613-1)") (class "Default")
      (node (ref "C613") (pin "P$1") (pinfunction "1_P$1") (pintype "passive"))
      (node (ref "U101") (pin "73") (pinfunction "VCAP_2_73") (pintype "power_in"))
    )
    (net (code "82") (name "Net-(C703-1)") (class "Default")
      (node (ref "C703") (pin "P$1") (pinfunction "1_P$1") (pintype "passive"))
      (node (ref "J701") (pin "1") (pinfunction "1_1") (pintype "passive"))
      (node (ref "R703") (pin "P$1") (pinfunction "1_P$1") (pintype "passive"))
      (node (ref "U702") (pin "1") (pinfunction "OUT_1") (pintype "output"))
    )
    (net (code "83") (name "Net-(C704-1)") (class "Default")
      (node (ref "C704") (pin "P$1") (pinfunction "1_P$1") (pintype "passive"))
      (node (ref "R705") (pin "P$1") (pinfunction "1_P$1") (pintype "passive"))
      (node (ref "U702") (pin "6") (pinfunction "VCC_6") (pintype "bidirectional"))
    )
    (net (code "84") (name "Net-(C805-1)") (class "Default")
      (node (ref "C805") (pin "P$1") (pinfunction "1_P$1") (pintype "passive"))
      (node (ref "U801") (pin "5") (pinfunction "PD0/OSC<=_5") (pintype "bidirectional"))
      (node (ref "X801") (pin "3") (pinfunction "3_3") (pintype "bidirectional"))
    )
    (net (code "85") (name "Net-(C806-2)") (class "Default")
      (node (ref "C806") (pin "P$2") (pinfunction "2_P$2") (pintype "passive"))
      (node (ref "U801") (pin "6") (pinfunction "PD1/OSC=>_6") (pintype "bidirectional"))
      (node (ref "X801") (pin "1") (pinfunction "1_1") (pintype "bidirectional"))
    )
    (net (code "86") (name "Net-(C1002-1)") (class "Default")
      (node (ref "C1002") (pin "P$1") (pinfunction "1_P$1") (pintype "passive"))
      (node (ref "U1002") (pin "6") (pinfunction "CSET_6") (pintype "bidirectional"))
    )
    (net (code "87") (name "Net-(C1105-1)") (class "Default")
      (node (ref "C1105") (pin "P$1") (pinfunction "1_P$1") (pintype "passive"))
      (node (ref "U1101") (pin "P$18") (pinfunction "VS1_P$18") (pintype "bidirectional"))
      (node (ref "U1102") (pin "P$1") (pinfunction "S_P$1") (pintype "passive"))
      (node (ref "U1102") (pin "P$3") (pinfunction "S_P$3") (pintype "passive"))
    )
    (net (code "88") (name "Net-(C1106-1)") (class "Default")
      (node (ref "C1106") (pin "P$1") (pinfunction "1_P$1") (pintype "passive"))
      (node (ref "U1101") (pin "P$16") (pinfunction "VS2_P$16") (pintype "bidirectional"))
      (node (ref "U1103") (pin "P$1") (pinfunction "S_P$1") (pintype "passive"))
      (node (ref "U1103") (pin "P$3") (pinfunction "S_P$3") (pintype "passive"))
    )
    (net (code "89") (name "Net-(C1107-1)") (class "Default")
      (node (ref "C1107") (pin "P$1") (pinfunction "1_P$1") (pintype "passive"))
      (node (ref "U1101") (pin "P$14") (pinfunction "VS3_P$14") (pintype "bidirectional"))
      (node (ref "U1104") (pin "P$1") (pinfunction "S_P$1") (pintype "passive"))
      (node (ref "U1104") (pin "P$3") (pinfunction "S_P$3") (pintype "passive"))
    )
    (net (code "90") (name "Net-(C1108-1)") (class "Default")
      (node (ref "C1108") (pin "P$1") (pinfunction "1_P$1") (pintype "passive"))
      (node (ref "R1105") (pin "P$2") (pinfunction "2_P$2") (pintype "passive"))
      (node (ref "R1106") (pin "P$1") (pinfunction "1_P$1") (pintype "passive"))
      (node (ref "U1101") (pin "P$1") (pinfunction "UV1_P$1") (pintype "bidirectional"))
    )
    (net (code "91") (name "Net-(C1109-1)") (class "Default")
      (node (ref "C1109") (pin "P$1") (pinfunction "1_P$1") (pintype "passive"))
      (node (ref "R1109") (pin "P$2") (pinfunction "2_P$2") (pintype "passive"))
      (node (ref "R1110") (pin "P$1") (pinfunction "1_P$1") (pintype "passive"))
      (node (ref "U1101") (pin "P$3") (pinfunction "UV2_P$3") (pintype "bidirectional"))
    )
    (net (code "92") (name "Net-(C1110-1)") (class "Default")
      (node (ref "C1110") (pin "P$1") (pinfunction "1_P$1") (pintype "passive"))
      (node (ref "R1112") (pin "P$2") (pinfunction "2_P$2") (pintype "passive"))
      (node (ref "R1113") (pin "P$1") (pinfunction "1_P$1") (pintype "passive"))
      (node (ref "U1101") (pin "P$5") (pinfunction "UV3_P$5") (pintype "bidirectional"))
    )
    (net (code "93") (name "Net-(D1-C)") (class "Default")
      (node (ref "D1") (pin "CATHODE") (pinfunction "C_CATHODE") (pintype "passive"))
      (node (ref "D903") (pin "C") (pinfunction "C_C") (pintype "passive"))
      (node (ref "L901") (pin "P$1") (pinfunction "P$1_P$1") (pintype "bidirectional"))
    )
    (net (code "94") (name "Net-(D201-PadC)") (class "Default")
      (node (ref "D201") (pin "C") (pinfunction "C_C") (pintype "passive"))
      (node (ref "J201") (pin "1") (pinfunction "1_1") (pintype "passive"))
      (node (ref "L201") (pin "P$2") (pinfunction "P$2_P$2") (pintype "bidirectional"))
    )
    (net (code "95") (name "Net-(D202-PadC)") (class "Default")
      (node (ref "D202") (pin "C") (pinfunction "C_C") (pintype "passive"))
      (node (ref "J202") (pin "1") (pinfunction "1_1") (pintype "passive"))
      (node (ref "L202") (pin "P$2") (pinfunction "P$2_P$2") (pintype "bidirectional"))
    )
    (net (code "96") (name "Net-(D203-PadC)") (class "Default")
      (node (ref "D203") (pin "C") (pinfunction "C_C") (pintype "passive"))
      (node (ref "J203") (pin "1") (pinfunction "1_1") (pintype "passive"))
      (node (ref "J204") (pin "1") (pinfunction "1_1") (pintype "passive"))
      (node (ref "L203") (pin "P$2") (pinfunction "P$2_P$2") (pintype "bidirectional"))
    )
    (net (code "97") (name "Net-(D401-PadC)") (class "Default")
      (node (ref "D401") (pin "C") (pinfunction "C_C") (pintype "passive"))
      (node (ref "J401") (pin "1") (pinfunction "1_1") (pintype "passive"))
      (node (ref "J402") (pin "1") (pinfunction "1_1") (pintype "passive"))
      (node (ref "L401") (pin "P$2") (pinfunction "P$2_P$2") (pintype "bidirectional"))
    )
    (net (code "98") (name "Net-(D402-PadC)") (class "Default")
      (node (ref "D402") (pin "C") (pinfunction "C_C") (pintype "passive"))
      (node (ref "J403") (pin "1") (pinfunction "1_1") (pintype "passive"))
      (node (ref "L402") (pin "P$2") (pinfunction "P$2_P$2") (pintype "bidirectional"))
    )
    (net (code "99") (name "Net-(D403-PadC)") (class "Default")
      (node (ref "D403") (pin "C") (pinfunction "C_C") (pintype "passive"))
      (node (ref "J404") (pin "1") (pinfunction "1_1") (pintype "passive"))
      (node (ref "L404") (pin "P$2") (pinfunction "P$2_P$2") (pintype "bidirectional"))
    )
    (net (code "100") (name "Net-(D404-PadC)") (class "Default")
      (node (ref "D404") (pin "C") (pinfunction "C_C") (pintype "passive"))
      (node (ref "J405") (pin "1") (pinfunction "1_1") (pintype "passive"))
      (node (ref "L403") (pin "P$2") (pinfunction "P$2_P$2") (pintype "bidirectional"))
    )
    (net (code "101") (name "Net-(D1001-A1)") (class "Default")
      (node (ref "D1001") (pin "1") (pinfunction "A1_1") (pintype "passive"))
      (node (ref "F1001") (pin "2") (pinfunction "2_2") (pintype "bidirectional"))
    )
    (net (code "102") (name "Net-(D1001-A2)") (class "Default")
      (node (ref "D1001") (pin "2") (pinfunction "A2_2") (pintype "passive"))
      (node (ref "U1001") (pin "8") (pinfunction "OUT_8") (pintype "bidirectional"))
    )
    (net (code "103") (name "Net-(J301-2)") (class "Default")
      (node (ref "J301") (pin "D-") (pinfunction "2_D-") (pintype "bidirectional"))
      (node (ref "J302") (pin "3") (pinfunction "3_3") (pintype "passive"))
      (node (ref "U302") (pin "1") (pinfunction "D1I_1") (pintype "bidirectional"))
    )
    (net (code "104") (name "Net-(J301-3)") (class "Default")
      (node (ref "J301") (pin "D+") (pinfunction "3_D+") (pintype "bidirectional"))
      (node (ref "J302") (pin "2") (pinfunction "2_2") (pintype "passive"))
      (node (ref "U302") (pin "3") (pinfunction "D2I_3") (pintype "bidirectional"))
    )
    (net (code "105") (name "Net-(J901A-S)") (class "Default")
      (node (ref "J901") (pin "1") (pinfunction "S_1") (pintype "passive"))
      (node (ref "R909") (pin "P$2") (pinfunction "2_P$2") (pintype "passive"))
    )
    (net (code "106") (name "Net-(J901B-S)") (class "Default")
      (node (ref "J901") (pin "10") (pinfunction "S_10") (pintype "passive"))
      (node (ref "R914") (pin "P$2") (pinfunction "2_P$2") (pintype "passive"))
    )
    (net (code "107") (name "Net-(J901C-S)") (class "Default")
      (node (ref "J901") (pin "13") (pinfunction "S_13") (pintype "passive"))
      (node (ref "R906") (pin "P$2") (pinfunction "2_P$2") (pintype "passive"))
    )
    (net (code "108") (name "Net-(J901D-S)") (class "Default")
      (node (ref "J901") (pin "16") (pinfunction "S_16") (pintype "passive"))
      (node (ref "R915") (pin "P$2") (pinfunction "2_P$2") (pintype "passive"))
    )
    (net (code "109") (name "Net-(J901E-S)") (class "Default")
      (node (ref "J901") (pin "19") (pinfunction "S_19") (pintype "passive"))
      (node (ref "R907") (pin "P$2") (pinfunction "2_P$2") (pintype "passive"))
    )
    (net (code "110") (name "Net-(J901G-S)") (class "Default")
      (node (ref "J901") (pin "22") (pinfunction "S_22") (pintype "passive"))
      (node (ref "R916") (pin "P$2") (pinfunction "2_P$2") (pintype "passive"))
    )
    (net (code "111") (name "Net-(J901H-S)") (class "Default")
      (node (ref "J901") (pin "25") (pinfunction "S_25") (pintype "passive"))
      (node (ref "R908") (pin "P$2") (pinfunction "2_P$2") (pintype "passive"))
    )
    (net (code "112") (name "Net-(J901I-S)") (class "Default")
      (node (ref "J901") (pin "28") (pinfunction "S_28") (pintype "passive"))
      (node (ref "R917") (pin "P$2") (pinfunction "2_P$2") (pintype "passive"))
    )
    (net (code "113") (name "Net-(J901J-S)") (class "Default")
      (node (ref "J901") (pin "31") (pinfunction "S_31") (pintype "passive"))
      (node (ref "R902") (pin "P$2") (pinfunction "2_P$2") (pintype "passive"))
    )
    (net (code "114") (name "Net-(J901K-S)") (class "Default")
      (node (ref "J901") (pin "34") (pinfunction "S_34") (pintype "passive"))
      (node (ref "R911") (pin "P$2") (pinfunction "2_P$2") (pintype "passive"))
    )
    (net (code "115") (name "Net-(J901L-S)") (class "Default")
      (node (ref "J901") (pin "37") (pinfunction "S_37") (pintype "passive"))
      (node (ref "R903") (pin "P$2") (pinfunction "2_P$2") (pintype "passive"))
    )
    (net (code "116") (name "Net-(J901M-S)") (class "Default")
      (node (ref "J901") (pin "4") (pinfunction "S_4") (pintype "passive"))
      (node (ref "R910") (pin "P$2") (pinfunction "2_P$2") (pintype "passive"))
    )
    (net (code "117") (name "Net-(J901N-S)") (class "Default")
      (node (ref "J901") (pin "40") (pinfunction "S_40") (pintype "passive"))
      (node (ref "R912") (pin "P$2") (pinfunction "2_P$2") (pintype "passive"))
    )
    (net (code "118") (name "Net-(J901O-S)") (class "Default")
      (node (ref "J901") (pin "43") (pinfunction "S_43") (pintype "passive"))
      (node (ref "R904") (pin "P$2") (pinfunction "2_P$2") (pintype "passive"))
    )
    (net (code "119") (name "Net-(J901P-S)") (class "Default")
      (node (ref "J901") (pin "46") (pinfunction "S_46") (pintype "passive"))
      (node (ref "R913") (pin "P$2") (pinfunction "2_P$2") (pintype "passive"))
    )
    (net (code "120") (name "Net-(J901Q-S)") (class "Default")
      (node (ref "J901") (pin "7") (pinfunction "S_7") (pintype "passive"))
      (node (ref "R905") (pin "P$2") (pinfunction "2_P$2") (pintype "passive"))
    )
    (net (code "121") (name "Net-(L701-2)") (class "Default")
      (node (ref "L701") (pin "P$2") (pinfunction "2_P$2") (pintype "passive"))
      (node (ref "U702") (pin "5") (pinfunction "SW_5") (pintype "passive"))
    )
    (net (code "122") (name "Net-(Q601-PadC)") (class "Default")
      (node (ref "Q601") (pin "C") (pinfunction "C_C") (pintype "passive"))
      (node (ref "R621") (pin "2") (pinfunction "2_2") (pintype "passive"))
    )
    (net (code "123") (name "Net-(R3-1)") (class "Default")
      (node (ref "R3") (pin "P$1") (pinfunction "1_P$1") (pintype "passive"))
      (node (ref "R707") (pin "P$2") (pinfunction "2_P$2") (pintype "passive"))
    )
    (net (code "124") (name "Net-(R3-2)") (class "Default")
      (node (ref "LED701") (pin "C") (pinfunction "C_C") (pintype "passive"))
      (node (ref "R3") (pin "P$2") (pinfunction "2_P$2") (pintype "passive"))
    )
    (net (code "125") (name "Net-(R4-1)") (class "Default")
      (node (ref "R4") (pin "P$1") (pinfunction "1_P$1") (pintype "passive"))
      (node (ref "R709") (pin "P$2") (pinfunction "2_P$2") (pintype "passive"))
    )
    (net (code "126") (name "Net-(R4-2)") (class "Default")
      (node (ref "LED703") (pin "C") (pinfunction "C_C") (pintype "passive"))
      (node (ref "R4") (pin "P$2") (pinfunction "2_P$2") (pintype "passive"))
    )
    (net (code "127") (name "Net-(R101-1)") (class "Default")
      (node (ref "R101") (pin "P$1") (pinfunction "1_P$1") (pintype "passive"))
      (node (ref "U101") (pin "69") (pinfunction "PA10_69") (pintype "bidirectional"))
    )
    (net (code "128") (name "Net-(R102-1)") (class "Default")
      (node (ref "R102") (pin "P$1") (pinfunction "1_P$1") (pintype "passive"))
      (node (ref "U101") (pin "37") (pinfunction "PB2_37") (pintype "bidirectional"))
    )
    (net (code "129") (name "Net-(R201-1)") (class "Default")
      (node (ref "R201") (pin "P$1") (pinfunction "1_P$1") (pintype "passive"))
      (node (ref "U201") (pin "20") (pinfunction "B1_20") (pintype "bidirectional"))
    )
    (net (code "130") (name "Net-(R202-1)") (class "Default")
      (node (ref "R202") (pin "P$1") (pinfunction "1_P$1") (pintype "passive"))
      (node (ref "U201") (pin "17") (pinfunction "B3_17") (pintype "bidirectional"))
    )
    (net (code "131") (name "Net-(R203-1)") (class "Default")
      (node (ref "R203") (pin "P$1") (pinfunction "1_P$1") (pintype "passive"))
      (node (ref "U201") (pin "15") (pinfunction "B5_15") (pintype "bidirectional"))
    )
    (net (code "132") (name "Net-(R204-1)") (class "Default")
      (node (ref "R204") (pin "P$1") (pinfunction "1_P$1") (pintype "passive"))
      (node (ref "U201") (pin "13") (pinfunction "B7_13") (pintype "bidirectional"))
    )
    (net (code "133") (name "Net-(R205-1)") (class "Default")
      (node (ref "R205") (pin "P$1") (pinfunction "1_P$1") (pintype "passive"))
      (node (ref "U202") (pin "17") (pinfunction "B3_17") (pintype "bidirectional"))
    )
    (net (code "134") (name "Net-(R206-1)") (class "Default")
      (node (ref "R206") (pin "P$1") (pinfunction "1_P$1") (pintype "passive"))
      (node (ref "U202") (pin "15") (pinfunction "B5_15") (pintype "bidirectional"))
    )
    (net (code "135") (name "Net-(R207-1)") (class "Default")
      (node (ref "R207") (pin "P$1") (pinfunction "1_P$1") (pintype "passive"))
      (node (ref "U202") (pin "13") (pinfunction "B7_13") (pintype "bidirectional"))
    )
    (net (code "136") (name "Net-(R208-1)") (class "Default")
      (node (ref "R208") (pin "P$1") (pinfunction "1_P$1") (pintype "passive"))
      (node (ref "U201") (pin "18") (pinfunction "B2_18") (pintype "bidirectional"))
    )
    (net (code "137") (name "Net-(R209-1)") (class "Default")
      (node (ref "R209") (pin "P$1") (pinfunction "1_P$1") (pintype "passive"))
      (node (ref "U201") (pin "16") (pinfunction "B4_16") (pintype "bidirectional"))
    )
    (net (code "138") (name "Net-(R210-1)") (class "Default")
      (node (ref "R210") (pin "P$1") (pinfunction "1_P$1") (pintype "passive"))
      (node (ref "U201") (pin "14") (pinfunction "B6_14") (pintype "bidirectional"))
    )
    (net (code "139") (name "Net-(R211-1)") (class "Default")
      (node (ref "R211") (pin "P$1") (pinfunction "1_P$1") (pintype "passive"))
      (node (ref "U201") (pin "12") (pinfunction "B8_12") (pintype "bidirectional"))
    )
    (net (code "140") (name "Net-(R212-1)") (class "Default")
      (node (ref "R212") (pin "P$1") (pinfunction "1_P$1") (pintype "passive"))
      (node (ref "U202") (pin "16") (pinfunction "B4_16") (pintype "bidirectional"))
    )
    (net (code "141") (name "Net-(R213-1)") (class "Default")
      (node (ref "R213") (pin "P$1") (pinfunction "1_P$1") (pintype "passive"))
      (node (ref "U202") (pin "14") (pinfunction "B6_14") (pintype "bidirectional"))
    )
    (net (code "142") (name "Net-(R214-1)") (class "Default")
      (node (ref "R214") (pin "P$1") (pinfunction "1_P$1") (pintype "passive"))
      (node (ref "U202") (pin "12") (pinfunction "B8_12") (pintype "bidirectional"))
    )
    (net (code "143") (name "Net-(R215-2)") (class "Default")
      (node (ref "J203") (pin "4") (pinfunction "4_4") (pintype "passive"))
      (node (ref "R215") (pin "P$2") (pinfunction "2_P$2") (pintype "passive"))
    )
    (net (code "144") (name "Net-(R216-2)") (class "Default")
      (node (ref "J203") (pin "5") (pinfunction "5_5") (pintype "passive"))
      (node (ref "R216") (pin "P$2") (pinfunction "2_P$2") (pintype "passive"))
    )
    (net (code "145") (name "Net-(R404-2)") (class "Default")
      (node (ref "J401") (pin "2") (pinfunction "2_2") (pintype "passive"))
      (node (ref "R404") (pin "P$2") (pinfunction "2_P$2") (pintype "passive"))
    )
    (net (code "146") (name "Net-(R405-2)") (class "Default")
      (node (ref "J401") (pin "3") (pinfunction "3_3") (pintype "passive"))
      (node (ref "R405") (pin "P$2") (pinfunction "2_P$2") (pintype "passive"))
    )
    (net (code "147") (name "Net-(R407-2)") (class "Default")
      (node (ref "J404") (pin "2") (pinfunction "2_2") (pintype "passive"))
      (node (ref "R407") (pin "P$2") (pinfunction "2_P$2") (pintype "passive"))
    )
    (net (code "148") (name "Net-(R408-2)") (class "Default")
      (node (ref "J404") (pin "4") (pinfunction "4_4") (pintype "passive"))
      (node (ref "R408") (pin "P$2") (pinfunction "2_P$2") (pintype "passive"))
    )
    (net (code "149") (name "Net-(R608-2)") (class "Default")
      (node (ref "D2") (pin "C") (pinfunction "C_C") (pintype "passive"))
      (node (ref "R608") (pin "P$2") (pinfunction "2_P$2") (pintype "passive"))
    )
    (net (code "150") (name "Net-(R616-1)") (class "Default")
      (node (ref "R616") (pin "P$1") (pinfunction "1_P$1") (pintype "passive"))
      (node (ref "U602") (pin "7") (pinfunction "ILIM_7") (pintype "bidirectional"))
    )
    (net (code "151") (name "Net-(R617-1)") (class "Default")
      (node (ref "R617") (pin "P$1") (pinfunction "1_P$1") (pintype "passive"))
      (node (ref "U601") (pin "7") (pinfunction "ILIM_7") (pintype "bidirectional"))
    )
    (net (code "152") (name "Net-(R620-1)") (class "Default")
      (node (ref "Q601") (pin "B") (pinfunction "B_B") (pintype "passive"))
      (node (ref "R620") (pin "P$1") (pinfunction "1_P$1") (pintype "passive"))
    )
    (net (code "153") (name "Net-(R701-1)") (class "Default")
      (node (ref "R701") (pin "P$1") (pinfunction "1_P$1") (pintype "passive"))
      (node (ref "U702") (pin "7") (pinfunction "+IN_7") (pintype "input"))
    )
    (net (code "154") (name "Net-(R702-1)") (class "Default")
      (node (ref "R702") (pin "P$1") (pinfunction "1_P$1") (pintype "passive"))
      (node (ref "R703") (pin "P$2") (pinfunction "2_P$2") (pintype "passive"))
      (node (ref "U702") (pin "8") (pinfunction "-IN_8") (pintype "input"))
    )
    (net (code "155") (name "Net-(R704-2)") (class "Default")
      (node (ref "R704") (pin "P$2") (pinfunction "2_P$2") (pintype "passive"))
      (node (ref "U701") (pin "6") (pinfunction "REXT_6") (pintype "bidirectional"))
    )
    (net (code "156") (name "Net-(R705-2)") (class "Default")
      (node (ref "R705") (pin "P$2") (pinfunction "2_P$2") (pintype "passive"))
      (node (ref "R706") (pin "P$1") (pinfunction "1_P$1") (pintype "passive"))
      (node (ref "U702") (pin "2") (pinfunction "FB_2") (pintype "bidirectional"))
    )
    (net (code "157") (name "Net-(R708-2)") (class "Default")
      (node (ref "LED702") (pin "C") (pinfunction "C_C") (pintype "passive"))
      (node (ref "R708") (pin "P$2") (pinfunction "2_P$2") (pintype "passive"))
    )
    (net (code "158") (name "Net-(R710-1)") (class "Default")
      (node (ref "J702") (pin "2") (pinfunction "2_2") (pintype "passive"))
      (node (ref "R710") (pin "P$1") (pinfunction "1_P$1") (pintype "passive"))
    )
    (net (code "159") (name "Net-(R711-2)") (class "Default")
      (node (ref "LED704") (pin "C") (pinfunction "C_C") (pintype "passive"))
      (node (ref "R711") (pin "P$2") (pinfunction "2_P$2") (pintype "passive"))
    )
    (net (code "160") (name "Net-(R712-2)") (class "Default")
      (node (ref "LED705") (pin "C") (pinfunction "C_C") (pintype "passive"))
      (node (ref "R712") (pin "P$2") (pinfunction "2_P$2") (pintype "passive"))
    )
    (net (code "161") (name "Net-(R802-1)") (class "Default")
      (node (ref "R802") (pin "P$1") (pinfunction "1_P$1") (pintype "passive"))
      (node (ref "U801") (pin "20") (pinfunction "PB2_20") (pintype "bidirectional"))
    )
    (net (code "162") (name "Net-(R803-1)") (class "Default")
      (node (ref "R803") (pin "P$1") (pinfunction "1_P$1") (pintype "passive"))
      (node (ref "U801") (pin "12") (pinfunction "PA2_12") (pintype "bidirectional"))
    )
    (net (code "163") (name "Net-(R804-1)") (class "Default")
      (node (ref "R804") (pin "P$1") (pinfunction "1_P$1") (pintype "passive"))
      (node (ref "U801") (pin "13") (pinfunction "PA3_13") (pintype "bidirectional"))
    )
    (net (code "164") (name "Net-(R901-2)") (class "Default")
      (node (ref "D902") (pin "C") (pinfunction "C_C") (pintype "passive"))
      (node (ref "R901") (pin "P$2") (pinfunction "2_P$2") (pintype "passive"))
      (node (ref "R910") (pin "P$1") (pinfunction "1_P$1") (pintype "passive"))
      (node (ref "U903") (pin "3") (pinfunction "2Y_3") (pintype "bidirectional"))
    )
    (net (code "165") (name "Net-(R902-1)") (class "Default")
      (node (ref "R902") (pin "P$1") (pinfunction "1_P$1") (pintype "passive"))
      (node (ref "U901") (pin "20") (pinfunction "B1_20") (pintype "bidirectional"))
    )
    (net (code "166") (name "Net-(R903-1)") (class "Default")
      (node (ref "R903") (pin "P$1") (pinfunction "1_P$1") (pintype "passive"))
      (node (ref "U901") (pin "17") (pinfunction "B3_17") (pintype "bidirectional"))
    )
    (net (code "167") (name "Net-(R904-1)") (class "Default")
      (node (ref "R904") (pin "P$1") (pinfunction "1_P$1") (pintype "passive"))
      (node (ref "U901") (pin "15") (pinfunction "B5_15") (pintype "bidirectional"))
    )
    (net (code "168") (name "Net-(R905-1)") (class "Default")
      (node (ref "R905") (pin "P$1") (pinfunction "1_P$1") (pintype "passive"))
      (node (ref "U902") (pin "20") (pinfunction "B1_20") (pintype "bidirectional"))
    )
    (net (code "169") (name "Net-(R906-1)") (class "Default")
      (node (ref "R906") (pin "P$1") (pinfunction "1_P$1") (pintype "passive"))
      (node (ref "U902") (pin "17") (pinfunction "B3_17") (pintype "bidirectional"))
    )
    (net (code "170") (name "Net-(R907-1)") (class "Default")
      (node (ref "R907") (pin "P$1") (pinfunction "1_P$1") (pintype "passive"))
      (node (ref "U902") (pin "15") (pinfunction "B5_15") (pintype "bidirectional"))
    )
    (net (code "171") (name "Net-(R908-1)") (class "Default")
      (node (ref "R908") (pin "P$1") (pinfunction "1_P$1") (pintype "passive"))
      (node (ref "U902") (pin "13") (pinfunction "B7_13") (pintype "bidirectional"))
    )
    (net (code "172") (name "Net-(R911-1)") (class "Default")
      (node (ref "R911") (pin "P$1") (pinfunction "1_P$1") (pintype "passive"))
      (node (ref "U901") (pin "18") (pinfunction "B2_18") (pintype "bidirectional"))
    )
    (net (code "173") (name "Net-(R912-1)") (class "Default")
      (node (ref "R912") (pin "P$1") (pinfunction "1_P$1") (pintype "passive"))
      (node (ref "U901") (pin "16") (pinfunction "B4_16") (pintype "bidirectional"))
    )
    (net (code "174") (name "Net-(R913-1)") (class "Default")
      (node (ref "R913") (pin "P$1") (pinfunction "1_P$1") (pintype "passive"))
      (node (ref "U901") (pin "14") (pinfunction "B6_14") (pintype "bidirectional"))
    )
    (net (code "175") (name "Net-(R914-1)") (class "Default")
      (node (ref "R914") (pin "P$1") (pinfunction "1_P$1") (pintype "passive"))
      (node (ref "U902") (pin "18") (pinfunction "B2_18") (pintype "bidirectional"))
    )
    (net (code "176") (name "Net-(R915-1)") (class "Default")
      (node (ref "R915") (pin "P$1") (pinfunction "1_P$1") (pintype "passive"))
      (node (ref "U902") (pin "16") (pinfunction "B4_16") (pintype "bidirectional"))
    )
    (net (code "177") (name "Net-(R916-1)") (class "Default")
      (node (ref "R916") (pin "P$1") (pinfunction "1_P$1") (pintype "passive"))
      (node (ref "U902") (pin "14") (pinfunction "B6_14") (pintype "bidirectional"))
    )
    (net (code "178") (name "Net-(R917-1)") (class "Default")
      (node (ref "R917") (pin "P$1") (pinfunction "1_P$1") (pintype "passive"))
      (node (ref "U902") (pin "12") (pinfunction "B8_12") (pintype "bidirectional"))
    )
    (net (code "179") (name "Net-(R918-2)") (class "Default")
      (node (ref "R918") (pin "P$2") (pinfunction "2_P$2") (pintype "passive"))
      (node (ref "R922") (pin "P$1") (pinfunction "1_P$1") (pintype "passive"))
    )
    (net (code "180") (name "Net-(R1001-2)") (class "Default")
      (node (ref "R1001") (pin "P$2") (pinfunction "2_P$2") (pintype "passive"))
      (node (ref "U1001") (pin "7") (pinfunction "ILIM_7") (pintype "bidirectional"))
    )
    (net (code "181") (name "Net-(R1101-2)") (class "Default")
      (node (ref "L1101") (pin "P$2") (pinfunction "P$2_P$2") (pintype "bidirectional"))
      (node (ref "R1101") (pin "P$2") (pinfunction "2_P$2") (pintype "passive"))
    )
    (net (code "182") (name "Net-(R1102-2)") (class "Default")
      (node (ref "L1102") (pin "P$2") (pinfunction "P$2_P$2") (pintype "bidirectional"))
      (node (ref "R1102") (pin "P$2") (pinfunction "2_P$2") (pintype "passive"))
    )
    (net (code "183") (name "Net-(R1103-1)") (class "Default")
      (node (ref "J601") (pin "4") (pinfunction "4_4") (pintype "passive"))
      (node (ref "L1102") (pin "P$1") (pinfunction "P$1_P$1") (pintype "bidirectional"))
      (node (ref "R1103") (pin "P$1") (pinfunction "1_P$1") (pintype "passive"))
    )
    (net (code "184") (name "Net-(R1104-1)") (class "Default")
      (node (ref "J601") (pin "3") (pinfunction "3_3") (pintype "passive"))
      (node (ref "L1101") (pin "P$1") (pinfunction "P$1_P$1") (pintype "bidirectional"))
      (node (ref "R1104") (pin "P$1") (pinfunction "1_P$1") (pintype "passive"))
    )
    (net (code "185") (name "Net-(R1106-2)") (class "Default")
      (node (ref "R1106") (pin "P$2") (pinfunction "2_P$2") (pintype "passive"))
      (node (ref "R1107") (pin "P$1") (pinfunction "1_P$1") (pintype "passive"))
      (node (ref "U1101") (pin "P$2") (pinfunction "OV1_P$2") (pintype "bidirectional"))
    )
    (net (code "186") (name "Net-(R1110-2)") (class "Default")
      (node (ref "R1110") (pin "P$2") (pinfunction "2_P$2") (pintype "passive"))
      (node (ref "R1111") (pin "P$1") (pinfunction "1_P$1") (pintype "passive"))
      (node (ref "U1101") (pin "P$4") (pinfunction "OV2_P$4") (pintype "bidirectional"))
    )
    (net (code "187") (name "Net-(R1113-2)") (class "Default")
      (node (ref "R1113") (pin "P$2") (pinfunction "2_P$2") (pintype "passive"))
      (node (ref "R1114") (pin "P$1") (pinfunction "1_P$1") (pintype "passive"))
      (node (ref "U1101") (pin "P$6") (pinfunction "OV3_P$6") (pintype "bidirectional"))
    )
    (net (code "188") (name "Net-(R1115-2)") (class "Default")
      (node (ref "R1115") (pin "P$2") (pinfunction "2_P$2") (pintype "passive"))
      (node (ref "U1101") (pin "P$24") (pinfunction "HYS_P$24") (pintype "bidirectional"))
    )
    (net (code "189") (name "Net-(U701-OUT0)") (class "Default")
      (node (ref "U701") (pin "9") (pinfunction "OUT0_9") (pintype "open_collector"))
      (node (ref "U703") (pin "C1") (pinfunction "C_C1") (pintype "passive"))
    )
    (net (code "190") (name "Net-(U701-OUT1)") (class "Default")
      (node (ref "U701") (pin "8") (pinfunction "OUT1_8") (pintype "open_collector"))
      (node (ref "U703") (pin "C2") (pinfunction "C_C2") (pintype "passive"))
    )
    (net (code "191") (name "Net-(U701-OUT2)") (class "Default")
      (node (ref "U701") (pin "7") (pinfunction "OUT2_7") (pintype "open_collector"))
      (node (ref "U703") (pin "C3") (pinfunction "C_C3") (pintype "passive"))
    )
    (net (code "192") (name "Net-(U1101-G1)") (class "Default")
      (node (ref "U1101") (pin "P$17") (pinfunction "G1_P$17") (pintype "bidirectional"))
      (node (ref "U1102") (pin "P$2") (pinfunction "G_P$2") (pintype "passive"))
      (node (ref "U1102") (pin "P$4") (pinfunction "G_P$4") (pintype "passive"))
    )
    (net (code "193") (name "Net-(U1101-G2)") (class "Default")
      (node (ref "U1101") (pin "P$15") (pinfunction "G2_P$15") (pintype "bidirectional"))
      (node (ref "U1103") (pin "P$2") (pinfunction "G_P$2") (pintype "passive"))
      (node (ref "U1103") (pin "P$4") (pinfunction "G_P$4") (pintype "passive"))
    )
    (net (code "194") (name "Net-(U1101-G3)") (class "Default")
      (node (ref "U1101") (pin "P$13") (pinfunction "G3_P$13") (pintype "bidirectional"))
      (node (ref "U1104") (pin "P$2") (pinfunction "G_P$2") (pintype "passive"))
      (node (ref "U1104") (pin "P$4") (pinfunction "G_P$4") (pintype "passive"))
    )
    (net (code "195") (name "OTG_FS_DM") (class "Default")
      (node (ref "U101") (pin "70") (pinfunction "PA11_70") (pintype "bidirectional"))
      (node (ref "U302") (pin "6") (pinfunction "D1O_6") (pintype "bidirectional"))
    )
    (net (code "196") (name "OTG_FS_DP") (class "Default")
      (node (ref "U101") (pin "71") (pinfunction "PA12_71") (pintype "bidirectional"))
      (node (ref "U302") (pin "4") (pinfunction "D2O_4") (pintype "bidirectional"))
    )
    (net (code "197") (name "PPM_INPUT") (class "Default")
      (node (ref "D901") (pin "C") (pinfunction "C_C") (pintype "passive"))
      (node (ref "R909") (pin "P$1") (pinfunction "1_P$1") (pintype "passive"))
      (node (ref "U801") (pin "29") (pinfunction "PA8_29") (pintype "bidirectional"))
      (node (ref "U903") (pin "2") (pinfunction "1A_2") (pintype "bidirectional"))
    )
    (net (code "198") (name "PRESSURE_SENS") (class "Default")
      (node (ref "C401") (pin "P$1") (pinfunction "1_P$1") (pintype "passive"))
      (node (ref "R403") (pin "P$2") (pinfunction "2_P$2") (pintype "passive"))
      (node (ref "R406") (pin "P$1") (pinfunction "1_P$1") (pintype "passive"))
      (node (ref "U101") (pin "34") (pinfunction "PC5_34") (pintype "bidirectional"))
    )
    (net (code "199") (name "PRESSURE_SENS_IN") (class "Default")
      (node (ref "ADC_PR1116") (pin "P$1") (pinfunction "P$1_P$1") (pintype "passive"))
      (node (ref "J402") (pin "2") (pinfunction "2_2") (pintype "passive"))
      (node (ref "R406") (pin "P$2") (pinfunction "2_P$2") (pintype "passive"))
    )
    (net (code "200") (name "RSSI_IN") (class "Default")
      (node (ref "R901") (pin "P$1") (pinfunction "1_P$1") (pintype "passive"))
      (node (ref "U801") (pin "15") (pinfunction "PA5_15") (pintype "bidirectional"))
      (node (ref "U801") (pin "33") (pinfunction "PA12_33") (pintype "bidirectional"))
    )
    (net (code "201") (name "SAFETY") (class "Default")
      (node (ref "J702") (pin "3") (pinfunction "3_3") (pintype "passive"))
      (node (ref "R713") (pin "P$1") (pinfunction "1_P$1") (pintype "passive"))
      (node (ref "U801") (pin "41") (pinfunction "PB5_41") (pintype "bidirectional"))
    )
    (net (code "202") (name "SBUS_INPUT") (class "Default")
      (node (ref "U801") (pin "22") (pinfunction "PB11_22") (pintype "bidirectional"))
      (node (ref "U903") (pin "6") (pinfunction "1Y_6") (pintype "bidirectional"))
    )
    (net (code "203") (name "SBUS_OUTPUT") (class "Default")
      (node (ref "U801") (pin "21") (pinfunction "PB10_21") (pintype "bidirectional"))
      (node (ref "U903") (pin "5") (pinfunction "2A_5") (pintype "bidirectional"))
    )
    (net (code "204") (name "SDIO_CK") (class "Default")
      (node (ref "U101") (pin "80") (pinfunction "PC12_80") (pintype "bidirectional"))
      (node (ref "U301") (pin "5") (pinfunction "CLK_5") (pintype "bidirectional"))
    )
    (net (code "205") (name "SDIO_CMD") (class "Default")
      (node (ref "R303") (pin "P$1") (pinfunction "1_P$1") (pintype "passive"))
      (node (ref "U101") (pin "83") (pinfunction "PD2_83") (pintype "bidirectional"))
      (node (ref "U301") (pin "3") (pinfunction "CMD_3") (pintype "bidirectional"))
    )
    (net (code "206") (name "SDIO_D0") (class "Default")
      (node (ref "R304") (pin "P$1") (pinfunction "1_P$1") (pintype "passive"))
      (node (ref "U101") (pin "65") (pinfunction "PC8_65") (pintype "bidirectional"))
      (node (ref "U301") (pin "7") (pinfunction "D0_7") (pintype "bidirectional"))
    )
    (net (code "207") (name "SDIO_D1") (class "Default")
      (node (ref "R305") (pin "P$1") (pinfunction "1_P$1") (pintype "passive"))
      (node (ref "U101") (pin "66") (pinfunction "PC9_66") (pintype "bidirectional"))
      (node (ref "U301") (pin "8") (pinfunction "D1_8") (pintype "bidirectional"))
    )
    (net (code "208") (name "SDIO_D2") (class "Default")
      (node (ref "R301") (pin "P$1") (pinfunction "1_P$1") (pintype "passive"))
      (node (ref "U101") (pin "78") (pinfunction "PC10_78") (pintype "bidirectional"))
      (node (ref "U301") (pin "1") (pinfunction "D2_1") (pintype "bidirectional"))
    )
    (net (code "209") (name "SDIO_D3") (class "Default")
      (node (ref "R302") (pin "P$1") (pinfunction "1_P$1") (pintype "passive"))
      (node (ref "U101") (pin "79") (pinfunction "PC11_79") (pintype "bidirectional"))
      (node (ref "U301") (pin "2") (pinfunction "D3_2") (pintype "bidirectional"))
    )
    (net (code "210") (name "SERIAL1_CTS") (class "Default")
      (node (ref "J201") (pin "4") (pinfunction "4_4") (pintype "passive"))
      (node (ref "R211") (pin "P$2") (pinfunction "2_P$2") (pintype "passive"))
    )
    (net (code "211") (name "SERIAL1_RTS") (class "Default")
      (node (ref "J201") (pin "5") (pinfunction "5_5") (pintype "passive"))
      (node (ref "R204") (pin "P$2") (pinfunction "2_P$2") (pintype "passive"))
    )
    (net (code "212") (name "SERIAL1_RX") (class "Default")
      (node (ref "J201") (pin "3") (pinfunction "3_3") (pintype "passive"))
      (node (ref "R203") (pin "P$2") (pinfunction "2_P$2") (pintype "passive"))
      (node (ref "S1RX1116") (pin "P$1") (pinfunction "P$1_P$1") (pintype "passive"))
    )
    (net (code "213") (name "SERIAL1_TX") (class "Default")
      (node (ref "J201") (pin "2") (pinfunction "2_2") (pintype "passive"))
      (node (ref "R210") (pin "P$2") (pinfunction "2_P$2") (pintype "passive"))
      (node (ref "S1TX1116") (pin "P$1") (pinfunction "P$1_P$1") (pintype "passive"))
    )
    (net (code "214") (name "SERIAL2_CTS") (class "Default")
      (node (ref "J202") (pin "4") (pinfunction "4_4") (pintype "passive"))
      (node (ref "R208") (pin "P$2") (pinfunction "2_P$2") (pintype "passive"))
    )
    (net (code "215") (name "SERIAL2_RTS") (class "Default")
      (node (ref "J202") (pin "5") (pinfunction "5_5") (pintype "passive"))
      (node (ref "R201") (pin "P$2") (pinfunction "2_P$2") (pintype "passive"))
    )
    (net (code "216") (name "SERIAL2_RX") (class "Default")
      (node (ref "J202") (pin "3") (pinfunction "3_3") (pintype "passive"))
      (node (ref "R202") (pin "P$2") (pinfunction "2_P$2") (pintype "passive"))
      (node (ref "S2RX1116") (pin "P$1") (pinfunction "P$1_P$1") (pintype "passive"))
    )
    (net (code "217") (name "SERIAL2_TX") (class "Default")
      (node (ref "J202") (pin "2") (pinfunction "2_2") (pintype "passive"))
      (node (ref "R209") (pin "P$2") (pinfunction "2_P$2") (pintype "passive"))
      (node (ref "S2TX1116") (pin "P$1") (pinfunction "P$1_P$1") (pintype "passive"))
    )
    (net (code "218") (name "SERIAL3_RX") (class "Default")
      (node (ref "J203") (pin "3") (pinfunction "3_3") (pintype "passive"))
      (node (ref "R207") (pin "P$2") (pinfunction "2_P$2") (pintype "passive"))
      (node (ref "S3RX1116") (pin "P$1") (pinfunction "P$1_P$1") (pintype "passive"))
    )
    (net (code "219") (name "SERIAL3_TX") (class "Default")
      (node (ref "J203") (pin "2") (pinfunction "2_2") (pintype "passive"))
      (node (ref "R214") (pin "P$2") (pinfunction "2_P$2") (pintype "passive"))
      (node (ref "S3TX1116") (pin "P$1") (pinfunction "P$1_P$1") (pintype "passive"))
    )
    (net (code "220") (name "SERIAL4_RX") (class "Default")
      (node (ref "J204") (pin "3") (pinfunction "3_3") (pintype "passive"))
      (node (ref "R206") (pin "P$2") (pinfunction "2_P$2") (pintype "passive"))
      (node (ref "S4RX1116") (pin "P$1") (pinfunction "P$1_P$1") (pintype "passive"))
    )
    (net (code "221") (name "SERIAL4_TX") (class "Default")
      (node (ref "J204") (pin "2") (pinfunction "2_2") (pintype "passive"))
      (node (ref "R213") (pin "P$2") (pinfunction "2_P$2") (pintype "passive"))
      (node (ref "S4TX1116") (pin "P$1") (pinfunction "P$1_P$1") (pintype "passive"))
    )
    (net (code "222") (name "SERIAL5_RX") (class "Default")
      (node (ref "J204") (pin "5") (pinfunction "5_5") (pintype "passive"))
      (node (ref "R205") (pin "P$2") (pinfunction "2_P$2") (pintype "passive"))
      (node (ref "S5_RX1116") (pin "P$1") (pinfunction "P$1_P$1") (pintype "passive"))
    )
    (net (code "223") (name "SERIAL5_TX") (class "Default")
      (node (ref "J204") (pin "4") (pinfunction "4_4") (pintype "passive"))
      (node (ref "R212") (pin "P$2") (pinfunction "2_P$2") (pintype "passive"))
      (node (ref "S5_TX1116") (pin "P$1") (pinfunction "P$1_P$1") (pintype "passive"))
    )
    (net (code "224") (name "SERIAL_FMU_TO_IO") (class "Default")
      (node (ref "R804") (pin "P$2") (pinfunction "2_P$2") (pintype "passive"))
      (node (ref "U101") (pin "63") (pinfunction "PC6_63") (pintype "bidirectional"))
    )
    (net (code "225") (name "SERIAL_IO_TO_FMU") (class "Default")
      (node (ref "R803") (pin "P$2") (pinfunction "2_P$2") (pintype "passive"))
      (node (ref "U101") (pin "64") (pinfunction "PC7_64") (pintype "bidirectional"))
    )
    (net (code "226") (name "SPI_EXT_MISO") (class "Default")
      (node (ref "J403") (pin "3") (pinfunction "3_3") (pintype "passive"))
      (node (ref "U101") (pin "4") (pinfunction "PE5_4") (pintype "bidirectional"))
    )
    (net (code "227") (name "SPI_EXT_MOSI") (class "Default")
      (node (ref "J403") (pin "4") (pinfunction "4_4") (pintype "passive"))
      (node (ref "U101") (pin "5") (pinfunction "PE6_5") (pintype "bidirectional"))
    )
    (net (code "228") (name "SPI_EXT_SCK") (class "Default")
      (node (ref "J403") (pin "2") (pinfunction "2_2") (pintype "passive"))
      (node (ref "U101") (pin "1") (pinfunction "PE2_1") (pintype "bidirectional"))
    )
    (net (code "229") (name "SPI_INT_MISO") (class "Default")
      (node (ref "U101") (pin "31") (pinfunction "PA6_31") (pintype "bidirectional"))
      (node (ref "U501") (pin "4") (pinfunction "SDO/SA0_4") (pintype "bidirectional"))
      (node (ref "U502") (pin "4") (pinfunction "SDO/SA0_4") (pintype "bidirectional"))
      (node (ref "U504") (pin "7") (pinfunction "SDO/SA0_7") (pintype "bidirectional"))
      (node (ref "U505") (pin "9") (pinfunction "AD0/SDO_9") (pintype "bidirectional"))
      (node (ref "U506") (pin "6") (pinfunction "SDO_6") (pintype "bidirectional"))
      (node (ref "X503") (pin "9") (pinfunction "S_9") (pintype "passive"))
    )
    (net (code "230") (name "SPI_INT_MOSI") (class "Default")
      (node (ref "U101") (pin "32") (pinfunction "PA7_32") (pintype "bidirectional"))
      (node (ref "U501") (pin "3") (pinfunction "SDA/SDI/SDO_3") (pintype "bidirectional"))
      (node (ref "U502") (pin "3") (pinfunction "SDA/SDI/SDO_3") (pintype "bidirectional"))
      (node (ref "U504") (pin "6") (pinfunction "SDA/SDI/SDO_6") (pintype "bidirectional"))
      (node (ref "U505") (pin "24") (pinfunction "SDA/SDI_24") (pintype "bidirectional"))
      (node (ref "U506") (pin "7") (pinfunction "SDI/SDA_7") (pintype "bidirectional"))
      (node (ref "X503") (pin "8") (pinfunction "S_8") (pintype "passive"))
    )
    (net (code "231") (name "SPI_INT_SCK") (class "Default")
      (node (ref "U101") (pin "30") (pinfunction "PA5_30") (pintype "bidirectional"))
      (node (ref "U501") (pin "2") (pinfunction "SCL/SPC_2") (pintype "input"))
      (node (ref "U502") (pin "2") (pinfunction "SCL/SPC_2") (pintype "bidirectional"))
      (node (ref "U504") (pin "4") (pinfunction "SCL/SPC_4") (pintype "bidirectional"))
      (node (ref "U505") (pin "23") (pinfunction "SCL/SCLK_23") (pintype "bidirectional"))
      (node (ref "U506") (pin "8") (pinfunction "SCLK_8") (pintype "bidirectional"))
      (node (ref "X503") (pin "10") (pinfunction "S_10") (pintype "passive"))
    )
    (net (code "232") (name "VBAT") (class "Default")
      (node (ref "B601") (pin "1") (pinfunction "POS_1") (pintype "bidirectional"))
      (node (ref "R608") (pin "P$1") (pinfunction "1_P$1") (pintype "passive"))
      (node (ref "U101") (pin "6") (pinfunction "VBAT_6") (pintype "power_in"))
      (node (ref "U801") (pin "1") (pinfunction "VBAT_1") (pintype "power_in"))
    )
    (net (code "233") (name "VBUS") (class "Default")
      (node (ref "C1103") (pin "P$1") (pinfunction "1_P$1") (pintype "passive"))
      (node (ref "J301") (pin "VBUS") (pinfunction "1_VBUS") (pintype "power_in"))
      (node (ref "J302") (pin "1") (pinfunction "1_1") (pintype "passive"))
      (node (ref "R1112") (pin "P$1") (pinfunction "1_P$1") (pintype "passive"))
      (node (ref "U101") (pin "68") (pinfunction "PA9_68") (pintype "bidirectional"))
      (node (ref "U1101") (pin "P$19") (pinfunction "V3_P$19") (pintype "bidirectional"))
      (node (ref "U1104") (pin "P$7") (pinfunction "D_P$7") (pintype "passive"))
      (node (ref "U1104") (pin "P$8") (pinfunction "D_P$8") (pintype "passive"))
      (node (ref "U302") (pin "5") (pinfunction "VBUS_5") (pintype "bidirectional"))
      (node (ref "VBUS1116") (pin "P$1") (pinfunction "P$1_P$1") (pintype "passive"))
      (node (ref "VP_33") (pin "VP") (pinfunction "VP_VP") (pintype "passive"))
      (node (ref "VP_34") (pin "VP") (pinfunction "VP_VP") (pintype "passive"))
      (node (ref "VP_35") (pin "VP") (pinfunction "VP_VP") (pintype "passive"))
    )
    (net (code "234") (name "VDD_3V3_SENSORS") (class "Default")
      (node (ref "C501") (pin "P$1") (pinfunction "1_P$1") (pintype "passive"))
      (node (ref "C502") (pin "P$1") (pinfunction "1_P$1") (pintype "passive"))
      (node (ref "C503") (pin "P$1") (pinfunction "1_P$1") (pintype "passive"))
      (node (ref "C506") (pin "P$1") (pinfunction "1_P$1") (pintype "passive"))
      (node (ref "C507") (pin "P$1") (pinfunction "1_P$1") (pintype "passive"))
      (node (ref "C508") (pin "P$1") (pinfunction "1_P$1") (pintype "passive"))
      (node (ref "C511") (pin "P$1") (pinfunction "1_P$1") (pintype "passive"))
      (node (ref "C513") (pin "P$1") (pinfunction "1_P$1") (pintype "passive"))
      (node (ref "C514") (pin "P$1") (pinfunction "1_P$1") (pintype "passive"))
      (node (ref "C605") (pin "P$1") (pinfunction "1_P$1") (pintype "passive"))
      (node (ref "C617") (pin "P$1") (pinfunction "1_P$1") (pintype "passive"))
      (node (ref "Q601") (pin "E") (pinfunction "E_E") (pintype "passive"))
      (node (ref "U501") (pin "1") (pinfunction "VDD_IO_1") (pintype "bidirectional"))
      (node (ref "U501") (pin "15") (pinfunction "RES_P15_VDD_15") (pintype "bidirectional"))
      (node (ref "U501") (pin "16") (pinfunction "VDD_16") (pintype "bidirectional"))
      (node (ref "U502") (pin "1") (pinfunction "VDD_IO_1") (pintype "bidirectional"))
      (node (ref "U502") (pin "15") (pinfunction "VDD_15") (pintype "bidirectional"))
      (node (ref "U502") (pin "16") (pinfunction "VDD_16") (pintype "bidirectional"))
      (node (ref "U504") (pin "1") (pinfunction "VDD_IO_1") (pintype "bidirectional"))
      (node (ref "U504") (pin "14") (pinfunction "VDD_14") (pintype "bidirectional"))
      (node (ref "U505") (pin "13") (pinfunction "VDD_13") (pintype "bidirectional"))
      (node (ref "U506") (pin "1") (pinfunction "VDD_1") (pintype "bidirectional"))
      (node (ref "U603") (pin "8") (pinfunction "VOUT1_8") (pintype "bidirectional"))
      (node (ref "VDDA_3V1101") (pin "P$1") (pinfunction "P$1_P$1") (pintype "passive"))
      (node (ref "VP_36") (pin "VP") (pinfunction "VP_VP") (pintype "passive"))
      (node (ref "VP_37") (pin "VP") (pinfunction "VP_VP") (pintype "passive"))
      (node (ref "X503") (pin "1") (pinfunction "S_1") (pintype "passive"))
    )
    (net (code "235") (name "VDD_3V3_SENSORS_EN") (class "Default")
      (node (ref "R603") (pin "P$2") (pinfunction "2_P$2") (pintype "passive"))
      (node (ref "R620") (pin "P$2") (pinfunction "2_P$2") (pintype "passive"))
      (node (ref "R635") (pin "P$2") (pinfunction "2_P$2") (pintype "passive"))
      (node (ref "U101") (pin "2") (pinfunction "PE3_2") (pintype "bidirectional"))
      (node (ref "U603") (pin "5") (pinfunction "EN1_5") (pintype "bidirectional"))
    )
    (net (code "236") (name "VDD_3V3_SPEKTRUM") (class "Default")
      (node (ref "C1008") (pin "P$1") (pinfunction "1_P$1") (pintype "passive"))
      (node (ref "D801") (pin "C") (pinfunction "C_C") (pintype "passive"))
      (node (ref "J801") (pin "P$1") (pinfunction "P$1_P$1") (pintype "bidirectional"))
      (node (ref "U1002") (pin "8") (pinfunction "VOUT1_8") (pintype "bidirectional"))
    )
    (net (code "237") (name "VDD_3V3_SPEKTRUM_EN") (class "Default")
      (node (ref "R1002") (pin "P$2") (pinfunction "2_P$2") (pintype "passive"))
      (node (ref "U1002") (pin "5") (pinfunction "EN1_5") (pintype "bidirectional"))
      (node (ref "U801") (pin "2") (pinfunction "PC13_2") (pintype "bidirectional"))
    )
    (net (code "238") (name "VDD_5V_BRICK") (class "Default")
      (node (ref "C1101") (pin "P$1") (pinfunction "1_P$1") (pintype "passive"))
      (node (ref "J601") (pin "1") (pinfunction "1_1") (pintype "passive"))
      (node (ref "J601") (pin "2") (pinfunction "2_2") (pintype "passive"))
      (node (ref "R1105") (pin "P$1") (pinfunction "1_P$1") (pintype "passive"))
      (node (ref "U1101") (pin "P$21") (pinfunction "V1_P$21") (pintype "bidirectional"))
      (node (ref "U1102") (pin "P$7") (pinfunction "D_P$7") (pintype "passive"))
      (node (ref "U1102") (pin "P$8") (pinfunction "D_P$8") (pintype "passive"))
      (node (ref "VDD_5V_BRICK1116") (pin "P$1") (pinfunction "P$1_P$1") (pintype "passive"))
      (node (ref "VP_38") (pin "VP") (pinfunction "VP_VP") (pintype "passive"))
      (node (ref "VP_39") (pin "VP") (pinfunction "VP_VP") (pintype "passive"))
      (node (ref "VP_40") (pin "VP") (pinfunction "VP_VP") (pintype "passive"))
    )
    (net (code "239") (name "VDD_5V_HIPOWER") (class "Default")
      (node (ref "C614") (pin "P$1") (pinfunction "1_P$1") (pintype "passive"))
      (node (ref "L201") (pin "P$1") (pinfunction "P$1_P$1") (pintype "bidirectional"))
      (node (ref "U601") (pin "8") (pinfunction "OUT_8") (pintype "bidirectional"))
    )
    (net (code "240") (name "VDD_5V_IN") (class "Default")
      (node (ref "C1104") (pin "P$1") (pinfunction "1_P$1") (pintype "passive"))
      (node (ref "C702") (pin "P$1") (pinfunction "1_P$1") (pintype "passive"))
      (node (ref "F1001") (pin "1") (pinfunction "1_1") (pintype "bidirectional"))
      (node (ref "L603") (pin "P$1") (pinfunction "P$1_P$1") (pintype "bidirectional"))
      (node (ref "L701") (pin "P$1") (pinfunction "1_P$1") (pintype "passive"))
      (node (ref "LED701") (pin "A") (pinfunction "A_A") (pintype "passive"))
      (node (ref "LED704") (pin "A") (pinfunction "A_A") (pintype "passive"))
      (node (ref "R609") (pin "P$2") (pinfunction "2_P$2") (pintype "passive"))
      (node (ref "RN1101") (pin "5") (pinfunction "2_5") (pintype "passive"))
      (node (ref "RN1101") (pin "6") (pinfunction "2_6") (pintype "passive"))
      (node (ref "RN1101") (pin "7") (pinfunction "2_7") (pintype "passive"))
      (node (ref "U1101") (pin "P$12") (pinfunction "VOUT_P$12") (pintype "bidirectional"))
      (node (ref "U1102") (pin "P$5") (pinfunction "D_P$5") (pintype "passive"))
      (node (ref "U1102") (pin "P$6") (pinfunction "D_P$6") (pintype "passive"))
      (node (ref "U1103") (pin "P$5") (pinfunction "D_P$5") (pintype "passive"))
      (node (ref "U1103") (pin "P$6") (pinfunction "D_P$6") (pintype "passive"))
      (node (ref "U1104") (pin "P$5") (pinfunction "D_P$5") (pintype "passive"))
      (node (ref "U1104") (pin "P$6") (pinfunction "D_P$6") (pintype "passive"))
      (node (ref "U601") (pin "1") (pinfunction "IN_1") (pintype "bidirectional"))
      (node (ref "U602") (pin "1") (pinfunction "IN_1") (pintype "bidirectional"))
      (node (ref "U702") (pin "3") (pinfunction "VIN_3") (pintype "power_in"))
      (node (ref "U703") (pin "A1") (pinfunction "A_A1") (pintype "passive"))
      (node (ref "U703") (pin "A2") (pinfunction "A_A2") (pintype "passive"))
      (node (ref "U703") (pin "A3") (pinfunction "A_A3") (pintype "passive"))
      (node (ref "VDD_5V_IN1116") (pin "P$1") (pinfunction "P$1_P$1") (pintype "passive"))
      (node (ref "VP_41") (pin "VP") (pinfunction "VP_VP") (pintype "passive"))
      (node (ref "VP_42") (pin "VP") (pinfunction "VP_VP") (pintype "passive"))
      (node (ref "VP_43") (pin "VP") (pinfunction "VP_VP") (pintype "passive"))
      (node (ref "VP_44") (pin "VP") (pinfunction "VP_VP") (pintype "passive"))
      (node (ref "VP_45") (pin "VP") (pinfunction "VP_VP") (pintype "passive"))
      (node (ref "VP_46") (pin "VP") (pinfunction "VP_VP") (pintype "passive"))
      (node (ref "VP_47") (pin "VP") (pinfunction "VP_VP") (pintype "passive"))
      (node (ref "VP_48") (pin "VP") (pinfunction "VP_VP") (pintype "passive"))
      (node (ref "VP_49") (pin "VP") (pinfunction "VP_VP") (pintype "passive"))
      (node (ref "VP_50") (pin "VP") (pinfunction "VP_VP") (pintype "passive"))
      (node (ref "VP_51") (pin "VP") (pinfunction "VP_VP") (pintype "passive"))
      (node (ref "VP_52") (pin "VP") (pinfunction "VP_VP") (pintype "passive"))
      (node (ref "VP_53") (pin "VP") (pinfunction "VP_VP") (pintype "passive"))
    )
    (net (code "241") (name "VDD_5V_PERIPH") (class "Default")
      (node (ref "C618") (pin "P$1") (pinfunction "1_P$1") (pintype "passive"))
      (node (ref "L202") (pin "P$1") (pinfunction "P$1_P$1") (pintype "bidirectional"))
      (node (ref "L203") (pin "P$1") (pinfunction "P$1_P$1") (pintype "bidirectional"))
      (node (ref "L401") (pin "P$1") (pinfunction "P$1_P$1") (pintype "bidirectional"))
      (node (ref "L402") (pin "P$1") (pinfunction "P$1_P$1") (pintype "bidirectional"))
      (node (ref "L403") (pin "P$1") (pinfunction "P$1_P$1") (pintype "bidirectional"))
      (node (ref "L404") (pin "P$1") (pinfunction "P$1_P$1") (pintype "bidirectional"))
      (node (ref "U602") (pin "8") (pinfunction "OUT_8") (pintype "bidirectional"))
      (node (ref "VP_54") (pin "VP") (pinfunction "VP_VP") (pintype "passive"))
      (node (ref "VP_55") (pin "VP") (pinfunction "VP_VP") (pintype "passive"))
      (node (ref "VP_56") (pin "VP") (pinfunction "VP_VP") (pintype "passive"))
      (node (ref "VP_57") (pin "VP") (pinfunction "VP_VP") (pintype "passive"))
      (node (ref "VP_58") (pin "VP") (pinfunction "VP_VP") (pintype "passive"))
    )
    (net (code "242") (name "VDD_5V_SENS") (class "Default")
      (node (ref "R609") (pin "P$1") (pinfunction "1_P$1") (pintype "passive"))
      (node (ref "R610") (pin "P$1") (pinfunction "1_P$1") (pintype "passive"))
      (node (ref "U101") (pin "29") (pinfunction "PA4_29") (pintype "bidirectional"))
    )
    (net (code "243") (name "VDD_SERVO") (class "Default")
      (node (ref "C1102") (pin "P$1") (pinfunction "1_P$1") (pintype "passive"))
      (node (ref "D1") (pin "ANODE") (pinfunction "A_ANODE") (pintype "passive"))
      (node (ref "J901") (pin "11") (pinfunction "S_11") (pintype "passive"))
      (node (ref "J901") (pin "14") (pinfunction "S_14") (pintype "passive"))
      (node (ref "J901") (pin "17") (pinfunction "S_17") (pintype "passive"))
      (node (ref "J901") (pin "20") (pinfunction "S_20") (pintype "passive"))
      (node (ref "J901") (pin "23") (pinfunction "S_23") (pintype "passive"))
      (node (ref "J901") (pin "26") (pinfunction "S_26") (pintype "passive"))
      (node (ref "J901") (pin "29") (pinfunction "S_29") (pintype "passive"))
      (node (ref "J901") (pin "32") (pinfunction "S_32") (pintype "passive"))
      (node (ref "J901") (pin "35") (pinfunction "S_35") (pintype "passive"))
      (node (ref "J901") (pin "38") (pinfunction "S_38") (pintype "passive"))
      (node (ref "J901") (pin "41") (pinfunction "S_41") (pintype "passive"))
      (node (ref "J901") (pin "44") (pinfunction "S_44") (pintype "passive"))
      (node (ref "J901") (pin "47") (pinfunction "S_47") (pintype "passive"))
      (node (ref "J901") (pin "5") (pinfunction "S_5") (pintype "passive"))
      (node (ref "J901") (pin "8") (pinfunction "S_8") (pintype "passive"))
      (node (ref "R1109") (pin "P$1") (pinfunction "1_P$1") (pintype "passive"))
      (node (ref "R922") (pin "P$2") (pinfunction "2_P$2") (pintype "passive"))
      (node (ref "U1101") (pin "P$20") (pinfunction "V2_P$20") (pintype "bidirectional"))
      (node (ref "U1103") (pin "P$7") (pinfunction "D_P$7") (pintype "passive"))
      (node (ref "U1103") (pin "P$8") (pinfunction "D_P$8") (pintype "passive"))
      (node (ref "VDD_SERVO1116") (pin "P$1") (pinfunction "P$1_P$1") (pintype "passive"))
      (node (ref "VP_59") (pin "VP") (pinfunction "VP_VP") (pintype "passive"))
      (node (ref "VP_60") (pin "VP") (pinfunction "VP_VP") (pintype "passive"))
      (node (ref "VP_61") (pin "VP") (pinfunction "VP_VP") (pintype "passive"))
    )
    (net (code "244") (name "VDD_SERVO_IN") (class "Default")
      (node (ref "L901") (pin "P$2") (pinfunction "P$2_P$2") (pintype "bidirectional"))
      (node (ref "U1001") (pin "1") (pinfunction "IN_1") (pintype "bidirectional"))
    )
    (net (code "245") (name "VDD_SERVO_SENS") (class "Default")
      (node (ref "R918") (pin "P$1") (pinfunction "1_P$1") (pintype "passive"))
      (node (ref "R919") (pin "P$2") (pinfunction "2_P$2") (pintype "passive"))
      (node (ref "U801") (pin "14") (pinfunction "PA4_14") (pintype "bidirectional"))
    )
    (net (code "246") (name "unconnected-(J301-4-PadID)") (class "Default")
      (node (ref "J301") (pin "ID") (pinfunction "4_ID") (pintype "passive"))
    )
    (net (code "247") (name "unconnected-(JX301A-S-Pad10)") (class "Default")
      (node (ref "JX301") (pin "10") (pinfunction "S_10") (pintype "passive"))
    )
    (net (code "248") (name "unconnected-(JX301F-S-Pad8)") (class "Default")
      (node (ref "JX301") (pin "8") (pinfunction "S_8") (pintype "passive"))
    )
    (net (code "249") (name "unconnected-(JX802A-S-Pad10)") (class "Default")
      (node (ref "JX802") (pin "10") (pinfunction "S_10") (pintype "passive"))
    )
    (net (code "250") (name "unconnected-(JX802F-S-Pad8)") (class "Default")
      (node (ref "JX802") (pin "8") (pinfunction "S_8") (pintype "passive"))
    )
    (net (code "251") (name "unconnected-(U101I-PC1-Pad16)") (class "Default")
      (node (ref "U101") (pin "16") (pinfunction "PC1_16") (pintype "bidirectional"))
    )
    (net (code "252") (name "unconnected-(U202-A1-Pad1)") (class "Default")
      (node (ref "U202") (pin "1") (pinfunction "A1_1") (pintype "bidirectional"))
    )
    (net (code "253") (name "unconnected-(U202-A2-Pad3)") (class "Default")
      (node (ref "U202") (pin "3") (pinfunction "A2_3") (pintype "bidirectional"))
    )
    (net (code "254") (name "unconnected-(U202-B1-Pad20)") (class "Default")
      (node (ref "U202") (pin "20") (pinfunction "B1_20") (pintype "bidirectional"))
    )
    (net (code "255") (name "unconnected-(U202-B2-Pad18)") (class "Default")
      (node (ref "U202") (pin "18") (pinfunction "B2_18") (pintype "bidirectional"))
    )
    (net (code "256") (name "unconnected-(U501-INT1-Pad7)") (class "Default")
      (node (ref "U501") (pin "7") (pinfunction "INT1_7") (pintype "output"))
    )
    (net (code "257") (name "unconnected-(U502-DEN-Pad8)") (class "Default")
      (node (ref "U502") (pin "8") (pinfunction "DEN_8") (pintype "bidirectional"))
    )
    (net (code "258") (name "unconnected-(U502-INT1-Pad7)") (class "Default")
      (node (ref "U502") (pin "7") (pinfunction "INT1_7") (pintype "bidirectional"))
    )
    (net (code "259") (name "unconnected-(U505-AUX_CL-Pad7)") (class "Default")
      (node (ref "U505") (pin "7") (pinfunction "AUX_CL_7") (pintype "bidirectional"))
    )
    (net (code "260") (name "unconnected-(U505-AUX_DA-Pad6)") (class "Default")
      (node (ref "U505") (pin "6") (pinfunction "AUX_DA_6") (pintype "bidirectional"))
    )
    (net (code "261") (name "unconnected-(U505-CLKOUT-Pad22)") (class "Default")
      (node (ref "U505") (pin "22") (pinfunction "CLKOUT_22") (pintype "bidirectional"))
    )
    (net (code "262") (name "unconnected-(U505-FSYNC-Pad11)") (class "Default")
      (node (ref "U505") (pin "11") (pinfunction "FSYNC_11") (pintype "bidirectional"))
    )
    (net (code "263") (name "unconnected-(U505-NC1-Pad2)") (class "Default")
      (node (ref "U505") (pin "2") (pinfunction "NC1_2") (pintype "bidirectional"))
    )
    (net (code "264") (name "unconnected-(U505-NC2-Pad3)") (class "Default")
      (node (ref "U505") (pin "3") (pinfunction "NC2_3") (pintype "bidirectional"))
    )
    (net (code "265") (name "unconnected-(U505-NC3-Pad4)") (class "Default")
      (node (ref "U505") (pin "4") (pinfunction "NC3_4") (pintype "bidirectional"))
    )
    (net (code "266") (name "unconnected-(U505-NC4-Pad5)") (class "Default")
      (node (ref "U505") (pin "5") (pinfunction "NC4_5") (pintype "bidirectional"))
    )
    (net (code "267") (name "unconnected-(U505-NC5-Pad14)") (class "Default")
      (node (ref "U505") (pin "14") (pinfunction "NC5_14") (pintype "bidirectional"))
    )
    (net (code "268") (name "unconnected-(U505-NC6-Pad15)") (class "Default")
      (node (ref "U505") (pin "15") (pinfunction "NC6_15") (pintype "bidirectional"))
    )
    (net (code "269") (name "unconnected-(U505-NC7-Pad16)") (class "Default")
      (node (ref "U505") (pin "16") (pinfunction "NC7_16") (pintype "bidirectional"))
    )
    (net (code "270") (name "unconnected-(U505-NC8-Pad17)") (class "Default")
      (node (ref "U505") (pin "17") (pinfunction "NC8_17") (pintype "bidirectional"))
    )
    (net (code "271") (name "unconnected-(U505-RESV1-Pad19)") (class "Default")
      (node (ref "U505") (pin "19") (pinfunction "RESV1_19") (pintype "bidirectional"))
    )
    (net (code "272") (name "unconnected-(U505-RESV2-Pad21)") (class "Default")
      (node (ref "U505") (pin "21") (pinfunction "RESV2_21") (pintype "bidirectional"))
    )
    (net (code "273") (name "unconnected-(U506-CSB1-Pad4)") (class "Default")
      (node (ref "U506") (pin "4") (pinfunction "CSB1_4") (pintype "bidirectional"))
    )
    (net (code "274") (name "unconnected-(U801B-PA11-Pad32)") (class "Default")
      (node (ref "U801") (pin "32") (pinfunction "PA11_32") (pintype "bidirectional"))
    )
    (net (code "275") (name "unconnected-(U801D-PB12-Pad25)") (class "Default")
      (node (ref "U801") (pin "25") (pinfunction "PB12_25") (pintype "bidirectional"))
    )
    (net (code "276") (name "unconnected-(U801E-PB6-Pad42)") (class "Default")
      (node (ref "U801") (pin "42") (pinfunction "PB6_42") (pintype "bidirectional"))
    )
    (net (code "277") (name "unconnected-(U801E-PB7-Pad43)") (class "Default")
      (node (ref "U801") (pin "43") (pinfunction "PB7_43") (pintype "bidirectional"))
    )
    (net (code "278") (name "unconnected-(U801F-PC14-Pad3)") (class "Default")
      (node (ref "U801") (pin "3") (pinfunction "PC14_3") (pintype "bidirectional"))
    )
    (net (code "279") (name "unconnected-(U801F-PC15-Pad4)") (class "Default")
      (node (ref "U801") (pin "4") (pinfunction "PC15_4") (pintype "bidirectional"))
    )
    (net (code "280") (name "unconnected-(U901-A7-Pad8)") (class "Default")
      (node (ref "U901") (pin "8") (pinfunction "A7_8") (pintype "bidirectional"))
    )
    (net (code "281") (name "unconnected-(U901-A8-Pad9)") (class "Default")
      (node (ref "U901") (pin "9") (pinfunction "A8_9") (pintype "bidirectional"))
    )
    (net (code "282") (name "unconnected-(U901-B7-Pad13)") (class "Default")
      (node (ref "U901") (pin "13") (pinfunction "B7_13") (pintype "bidirectional"))
    )
    (net (code "283") (name "unconnected-(U901-B8-Pad12)") (class "Default")
      (node (ref "U901") (pin "12") (pinfunction "B8_12") (pintype "bidirectional"))
    )
    (net (code "284") (name "unconnected-(U1101-CAS-PadP$11)") (class "Default")
      (node (ref "U1101") (pin "P$11") (pinfunction "CAS_P$11") (pintype "bidirectional"))
    )
    (net (code "285") (name "unconnected-(U1101-EN-PadP$22)") (class "Default")
      (node (ref "U1101") (pin "P$22") (pinfunction "EN_P$22") (pintype "bidirectional"))
    )
    (net (code "286") (name "unconnected-(U1101-~{SHDN}-PadP$23)") (class "Default")
      (node (ref "U1101") (pin "P$23") (pinfunction "~{SHDN}_P$23") (pintype "bidirectional"))
    )
    (net (code "287") (name "~{ACCEL_MAG_CS}") (class "Default")
      (node (ref "U101") (pin "9") (pinfunction "PC15_9") (pintype "bidirectional"))
      (node (ref "U504") (pin "8") (pinfunction "CS_8") (pintype "bidirectional"))
      (node (ref "X503") (pin "6") (pinfunction "S_6") (pintype "passive"))
    )
    (net (code "288") (name "~{BARO_CS}") (class "Default")
      (node (ref "U101") (pin "88") (pinfunction "PD7_88") (pintype "bidirectional"))
      (node (ref "U506") (pin "5") (pinfunction "CSB2_5") (pintype "bidirectional"))
    )
    (net (code "289") (name "~{FMU-LED_AMBER}") (class "Default")
      (node (ref "R707") (pin "P$1") (pinfunction "1_P$1") (pintype "passive"))
      (node (ref "U101") (pin "43") (pinfunction "PE12_43") (pintype "bidirectional"))
    )
    (net (code "290") (name "~{FRAM_CS}") (class "Default")
      (node (ref "U101") (pin "57") (pinfunction "PD10_57") (pintype "bidirectional"))
      (node (ref "U102") (pin "1") (pinfunction "~{S}_1") (pintype "bidirectional"))
    )
    (net (code "291") (name "~{GYRO_CS}") (class "Default")
      (node (ref "U101") (pin "7") (pinfunction "PC13_7") (pintype "bidirectional"))
      (node (ref "U501") (pin "5") (pinfunction "CS_5") (pintype "input"))
      (node (ref "U502") (pin "5") (pinfunction "CS_5") (pintype "bidirectional"))
      (node (ref "X503") (pin "7") (pinfunction "S_7") (pintype "passive"))
    )
    (net (code "292") (name "~{IO-LED_AMBER}") (class "Default")
      (node (ref "R709") (pin "P$1") (pinfunction "1_P$1") (pintype "passive"))
      (node (ref "U801") (pin "28") (pinfunction "PB15_28") (pintype "bidirectional"))
    )
    (net (code "293") (name "~{IO-LED_BLUE}") (class "Default")
      (node (ref "R712") (pin "P$1") (pinfunction "1_P$1") (pintype "passive"))
      (node (ref "U801") (pin "27") (pinfunction "PB14_27") (pintype "bidirectional"))
    )
    (net (code "294") (name "~{IO-LED_SAFETY}") (class "Default")
      (node (ref "R710") (pin "P$2") (pinfunction "2_P$2") (pintype "passive"))
      (node (ref "U801") (pin "26") (pinfunction "PB13_26") (pintype "bidirectional"))
    )
    (net (code "295") (name "~{MPU_CS}") (class "Default")
      (node (ref "U101") (pin "17") (pinfunction "PC2_17") (pintype "bidirectional"))
      (node (ref "U505") (pin "8") (pinfunction "/CS_8") (pintype "bidirectional"))
    )
    (net (code "296") (name "~{SBUS_OUTPUT_EN}") (class "Default")
      (node (ref "U801") (pin "40") (pinfunction "PB4_40") (pintype "bidirectional"))
      (node (ref "U903") (pin "7") (pinfunction "~{2OE}_7") (pintype "input"))
    )
    (net (code "297") (name "~{SPI_EXT_NSS}") (class "Default")
      (node (ref "J403") (pin "5") (pinfunction "5_5") (pintype "passive"))
      (node (ref "U101") (pin "3") (pinfunction "PE4_3") (pintype "bidirectional"))
    )
    (net (code "298") (name "~{VBUS_VALID}") (class "Default")
      (node (ref "!VBUS_VALID1116") (pin "P$1") (pinfunction "P$1_P$1") (pintype "passive"))
      (node (ref "RN1101") (pin "2") (pinfunction "1_2") (pintype "passive"))
      (node (ref "U101") (pin "15") (pinfunction "PC0_15") (pintype "bidirectional"))
      (node (ref "U1101") (pin "P$9") (pinfunction "~{VALID3}_P$9") (pintype "bidirectional"))
    )
    (net (code "299") (name "~{VDD_5V_HIPOWER_OC}") (class "Default")
      (node (ref "R602") (pin "P$1") (pinfunction "1_P$1") (pintype "passive"))
      (node (ref "U101") (pin "41") (pinfunction "PE10_41") (pintype "bidirectional"))
      (node (ref "U601") (pin "4") (pinfunction "~{FAULT}_4") (pintype "bidirectional"))
    )
    (net (code "300") (name "~{VDD_5V_PERIPH_EN}") (class "Default")
      (node (ref "R615") (pin "P$1") (pinfunction "1_P$1") (pintype "passive"))
      (node (ref "U101") (pin "67") (pinfunction "PA8_67") (pintype "bidirectional"))
      (node (ref "U601") (pin "5") (pinfunction "~{CE}_5") (pintype "bidirectional"))
      (node (ref "U602") (pin "5") (pinfunction "~{CE}_5") (pintype "bidirectional"))
    )
    (net (code "301") (name "~{VDD_5V_PERIPH_OC}") (class "Default")
      (node (ref "R604") (pin "P$1") (pinfunction "1_P$1") (pintype "passive"))
      (node (ref "U101") (pin "46") (pinfunction "PE15_46") (pintype "bidirectional"))
      (node (ref "U602") (pin "4") (pinfunction "~{FAULT}_4") (pintype "bidirectional"))
    )
    (net (code "302") (name "~{VDD_BRICK_VALID}") (class "Default")
      (node (ref "!VDD_BRICK_VALID1116") (pin "P$1") (pinfunction "P$1_P$1") (pintype "passive"))
      (node (ref "RN1101") (pin "4") (pinfunction "1_4") (pintype "passive"))
      (node (ref "U101") (pin "91") (pinfunction "PB5_91") (pintype "bidirectional"))
      (node (ref "U1101") (pin "P$7") (pinfunction "~{VALID1}_P$7") (pintype "bidirectional"))
    )
    (net (code "303") (name "~{VDD_SERVO_VALID}") (class "Default")
      (node (ref "!VDD_SERVO_VALID1116") (pin "P$1") (pinfunction "P$1_P$1") (pintype "passive"))
      (node (ref "RN1101") (pin "3") (pinfunction "1_3") (pintype "passive"))
      (node (ref "U101") (pin "93") (pinfunction "PB7_93") (pintype "bidirectional"))
      (node (ref "U1101") (pin "P$8") (pinfunction "~{VALID2}_P$8") (pintype "bidirectional"))
    )
  )
)
